# M_G_T.net
KiCad netlist of a schematic drawn in Altium Designer
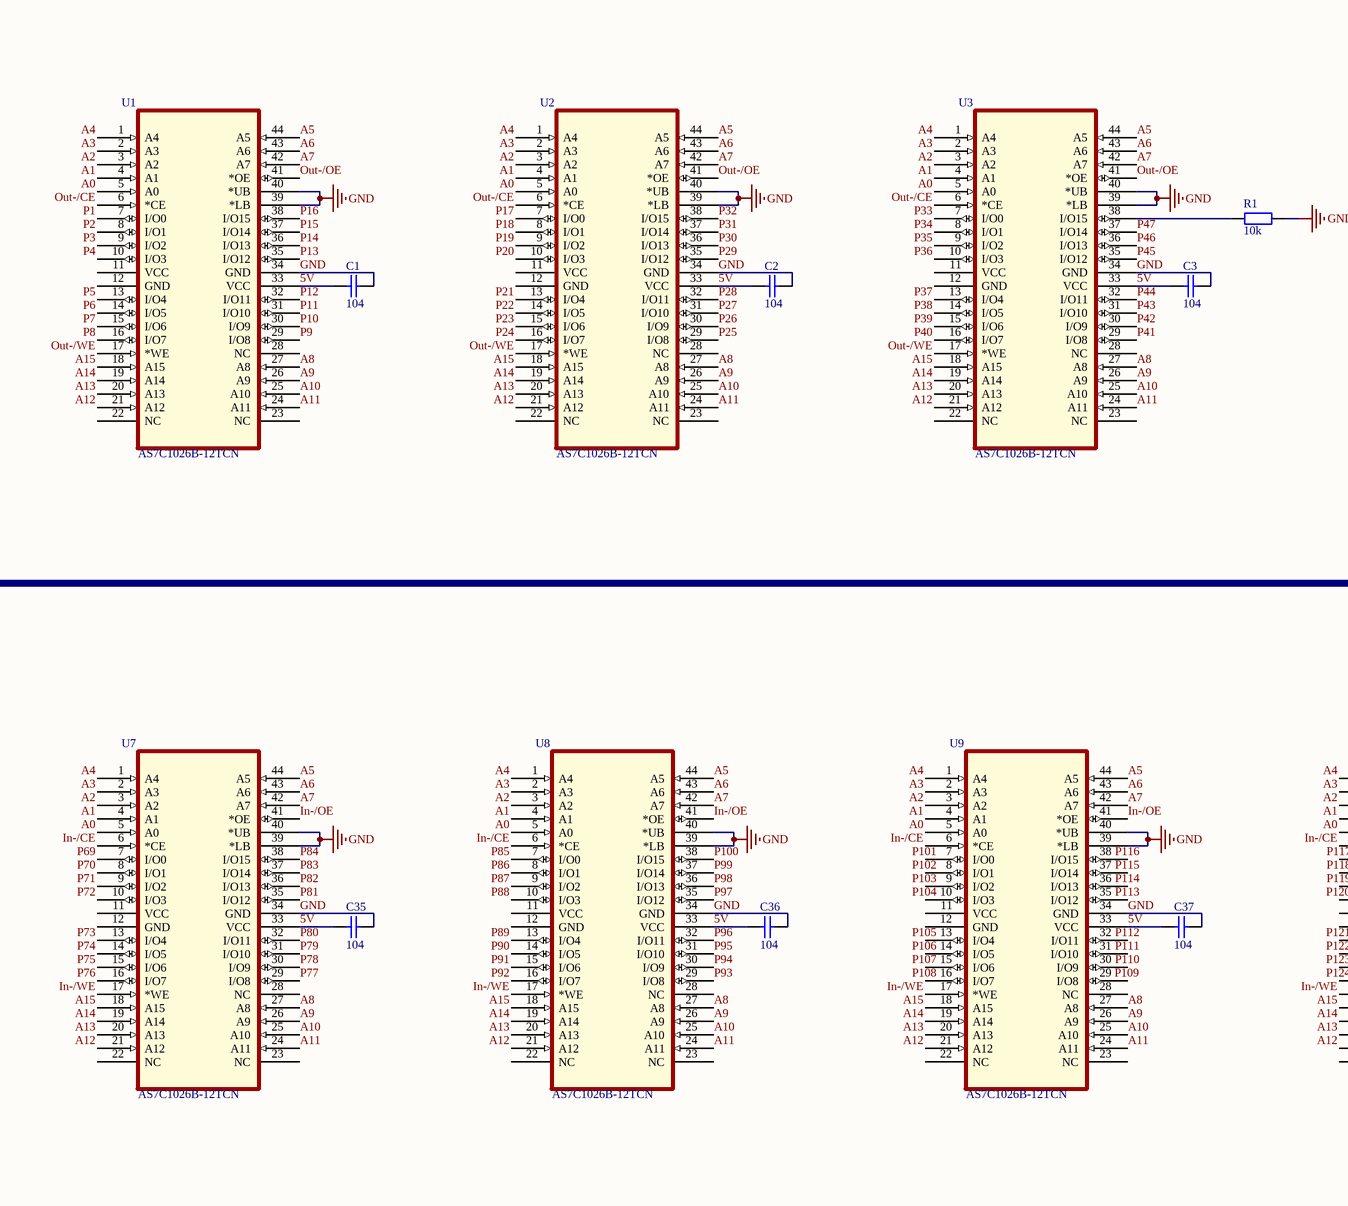
[diagram p0: M_G_T.SchDoc, top left]
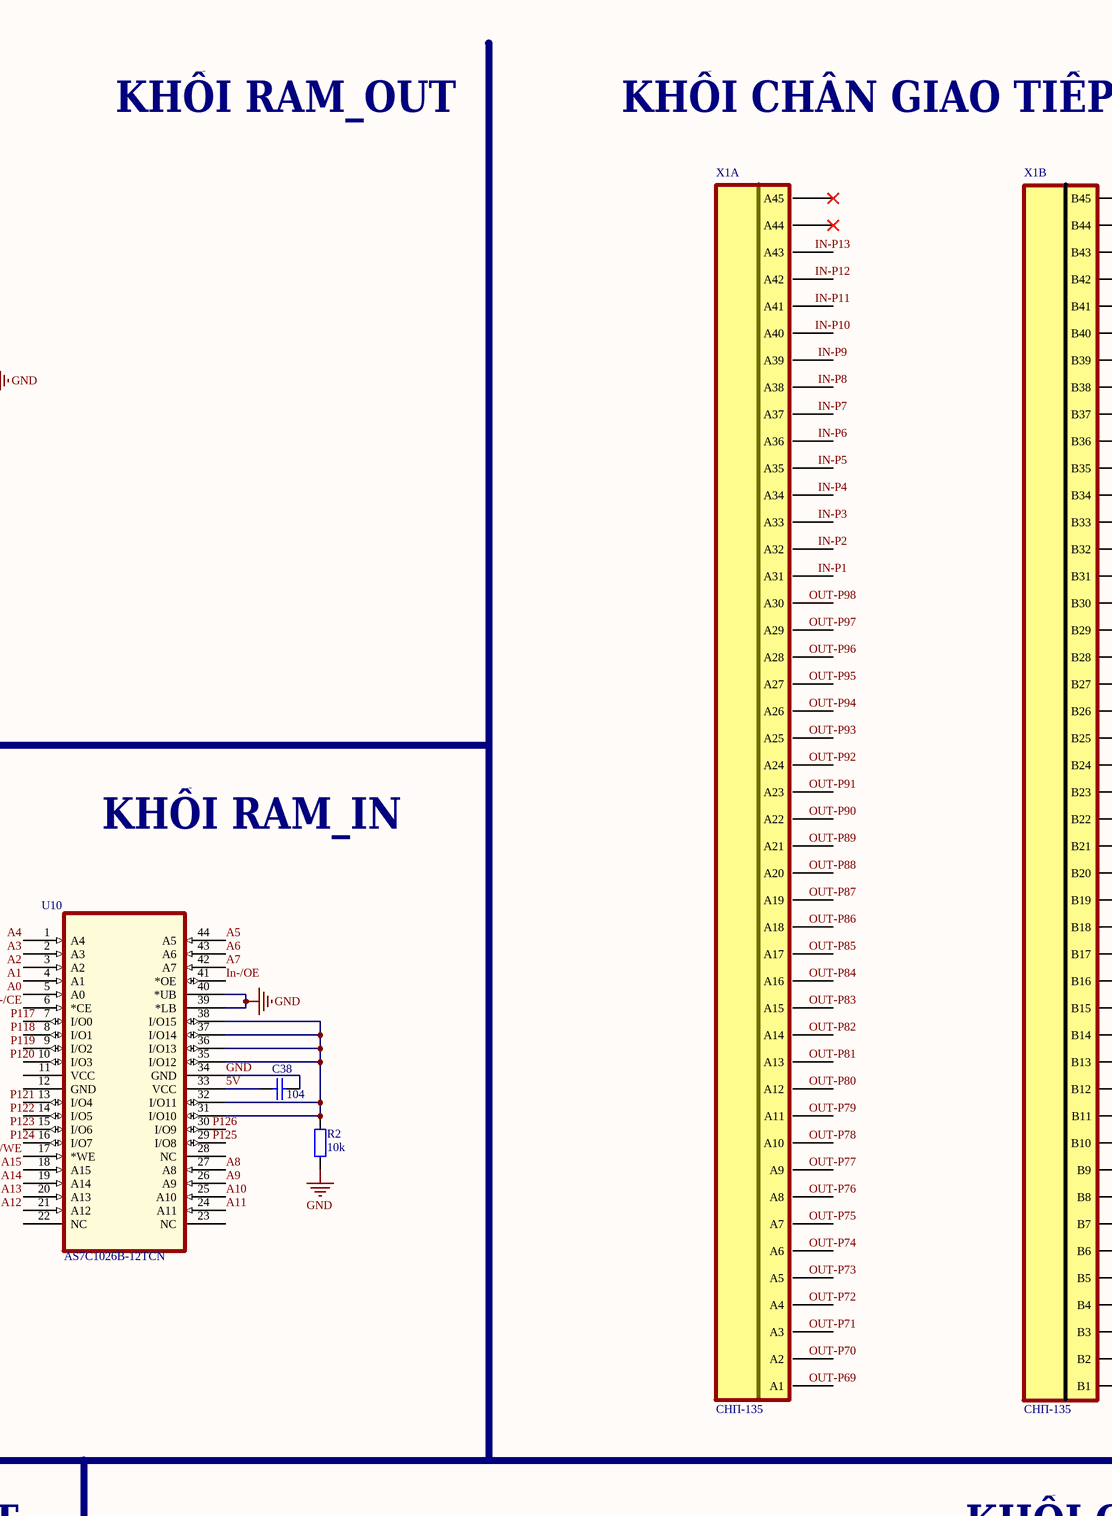
[diagram p1: M_G_T.SchDoc, top middle]
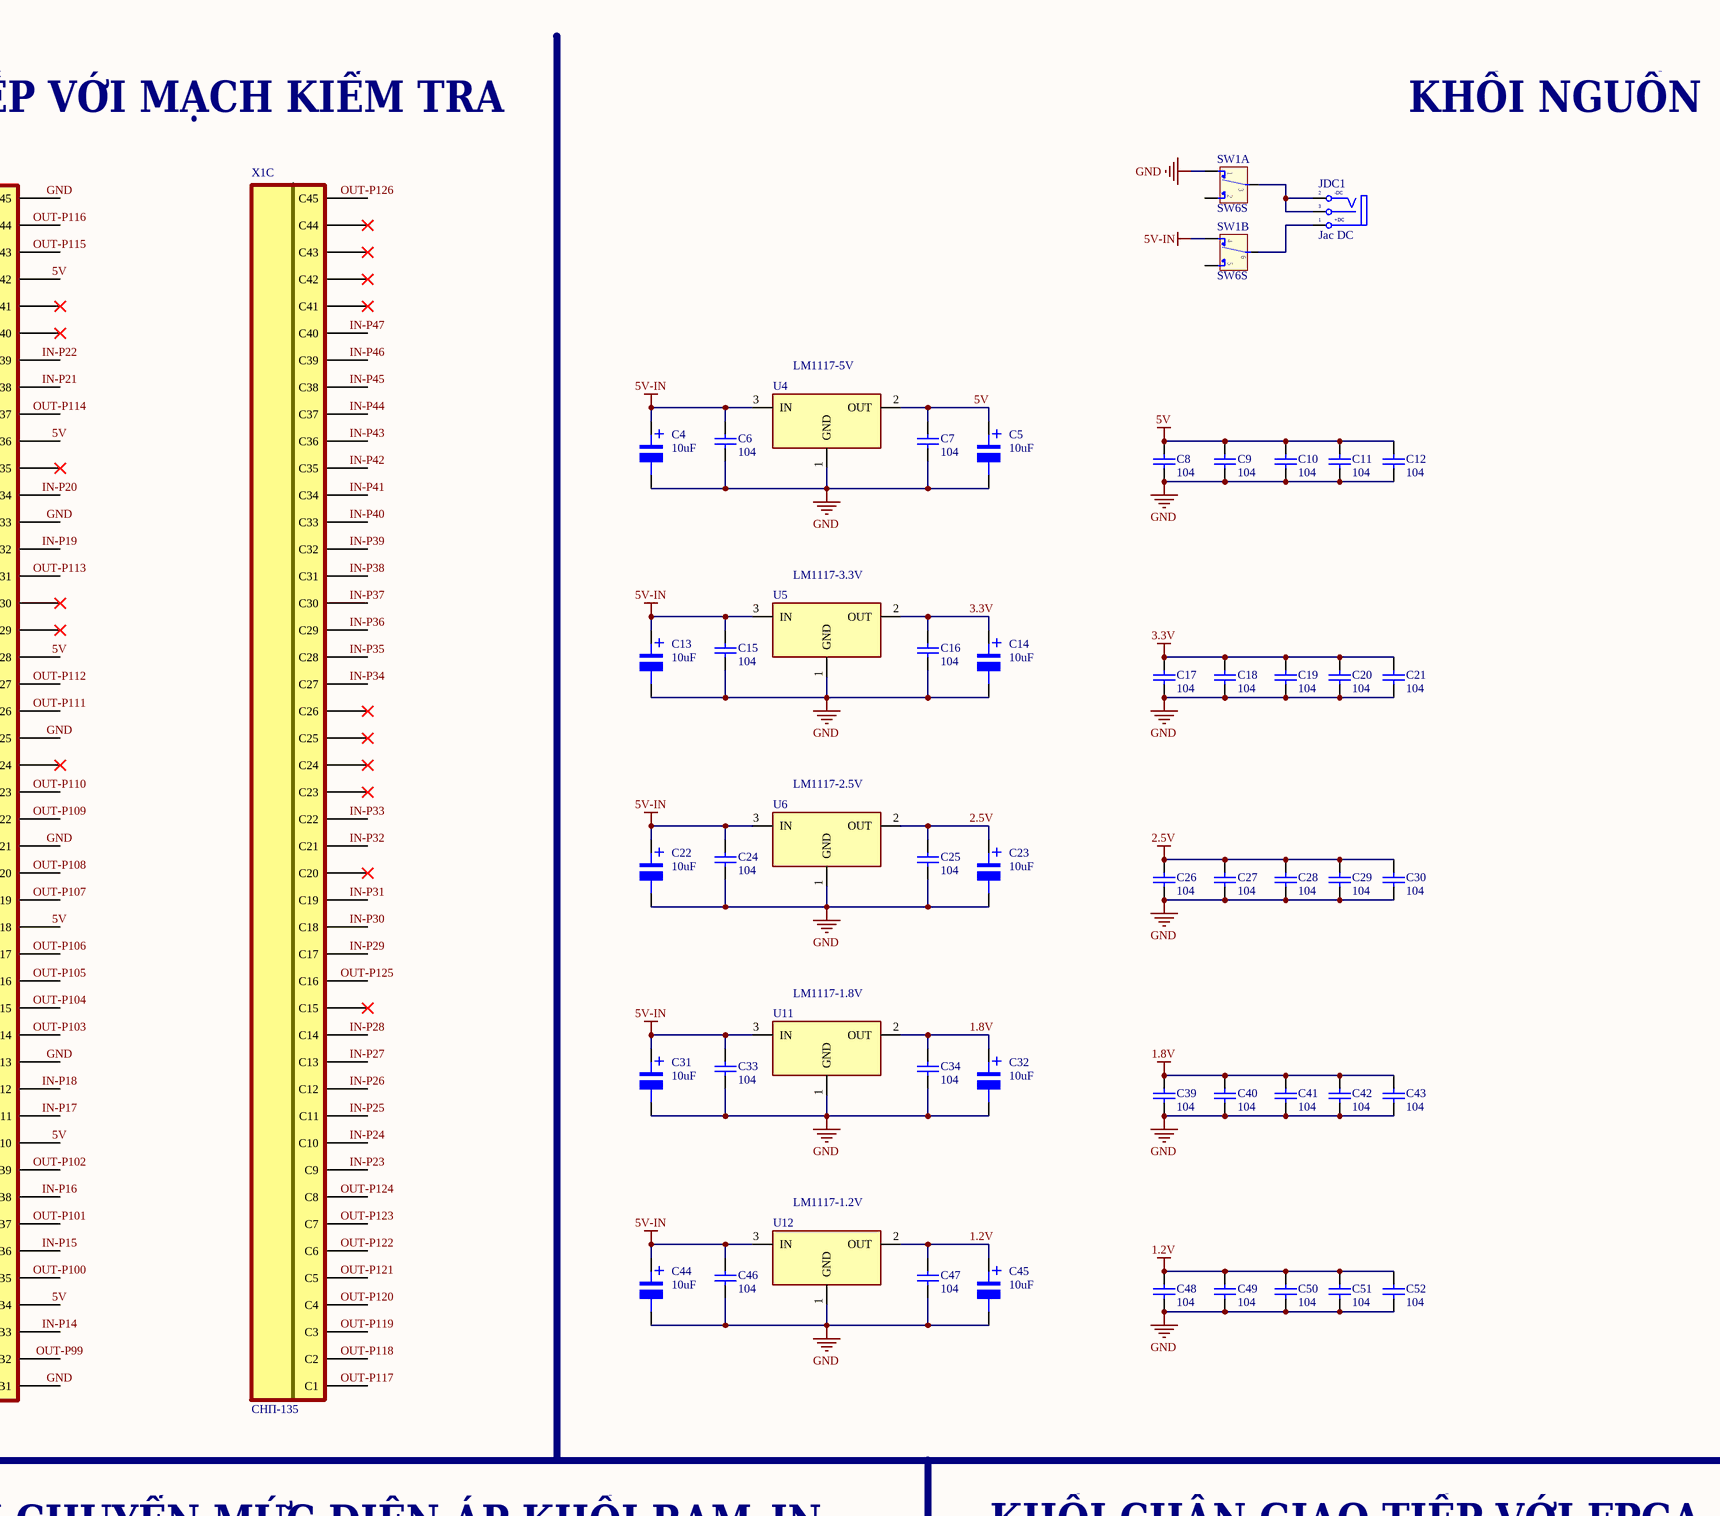
[diagram p2: M_G_T.SchDoc, top right]
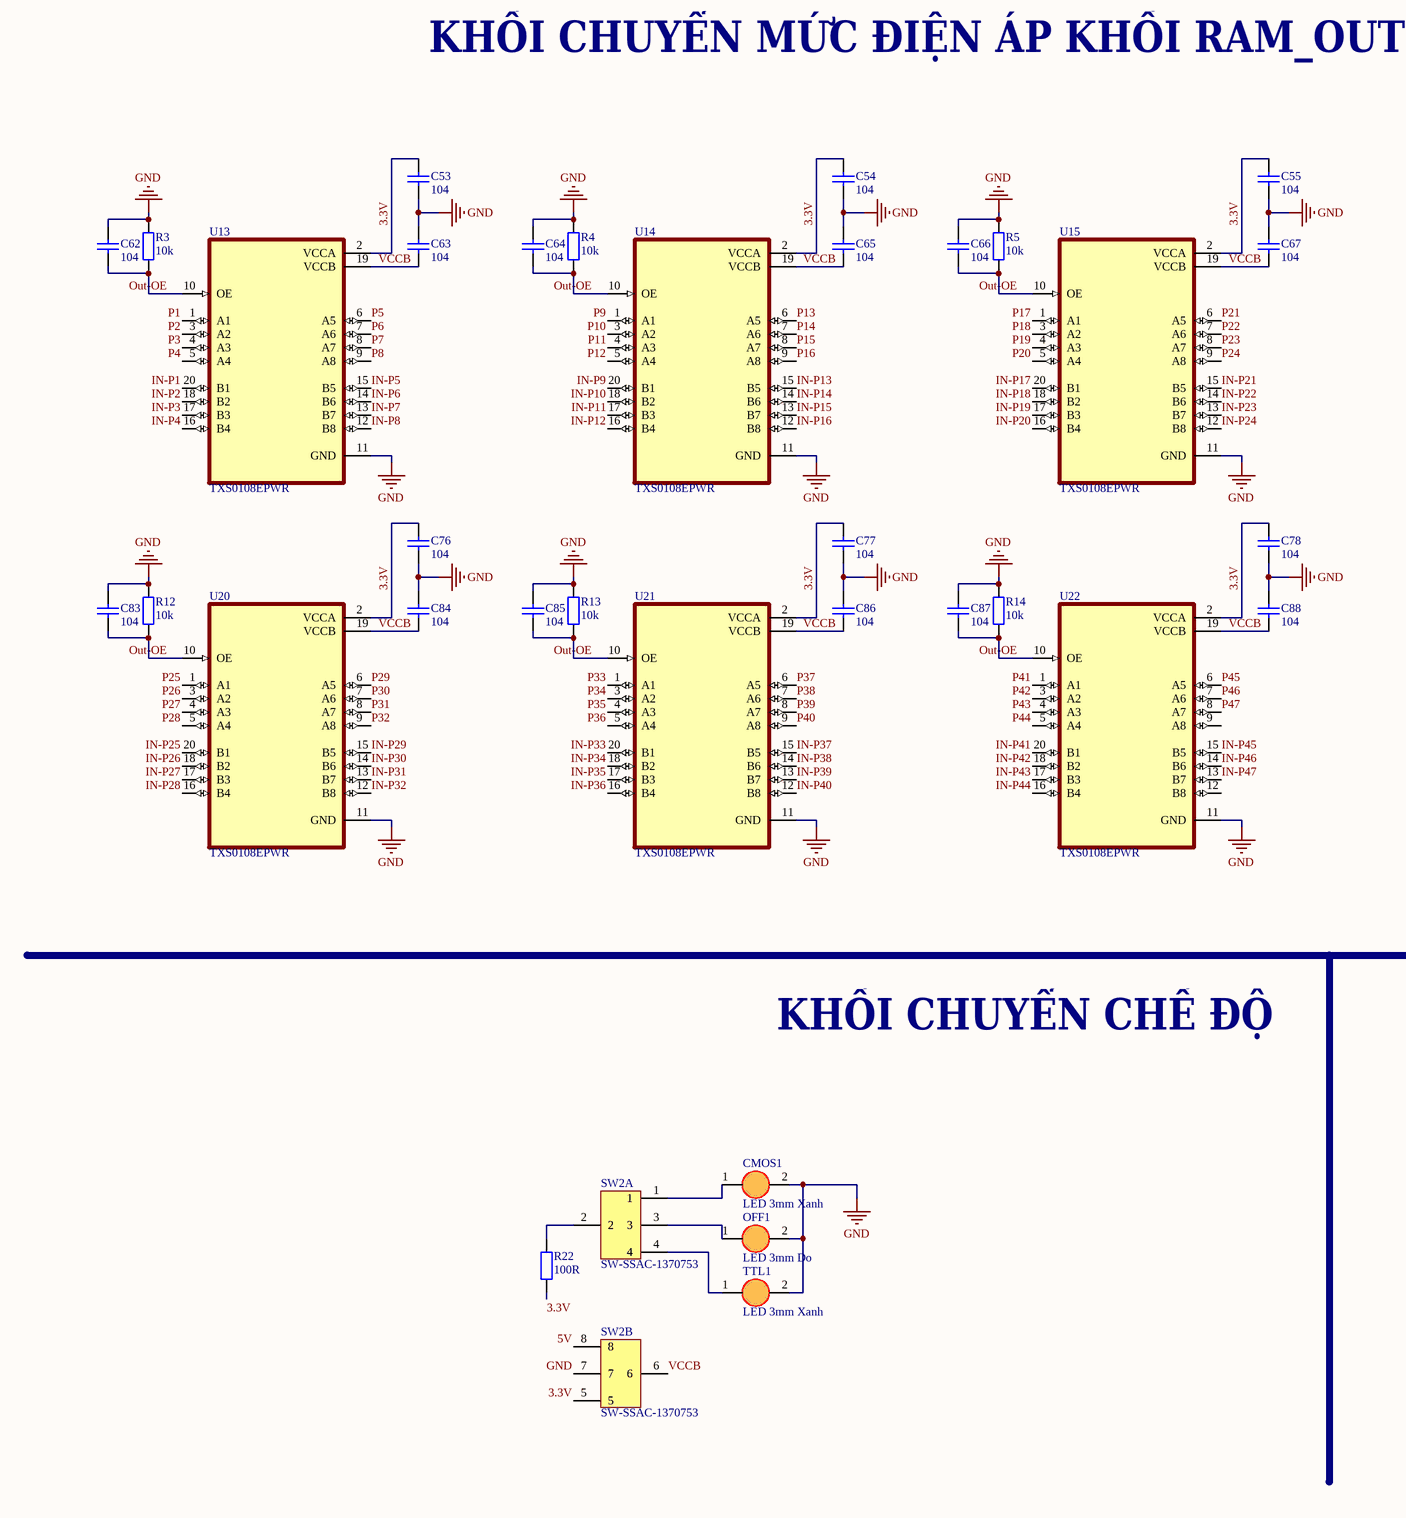
[diagram p3: M_G_T.SchDoc, bottom left]
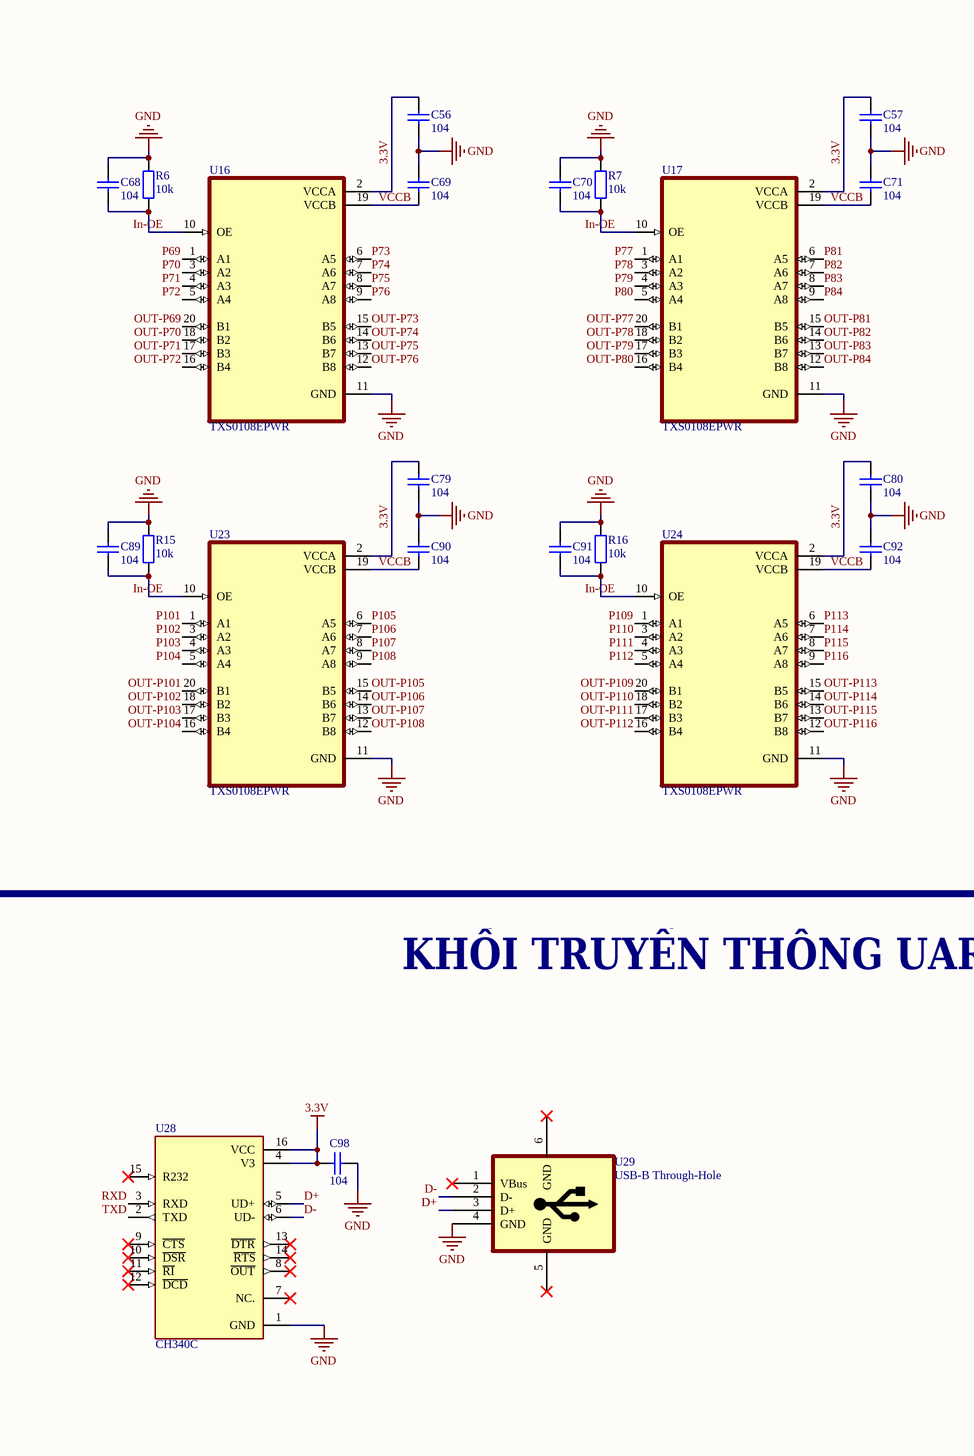
[diagram p4: M_G_T.SchDoc, bottom middle]
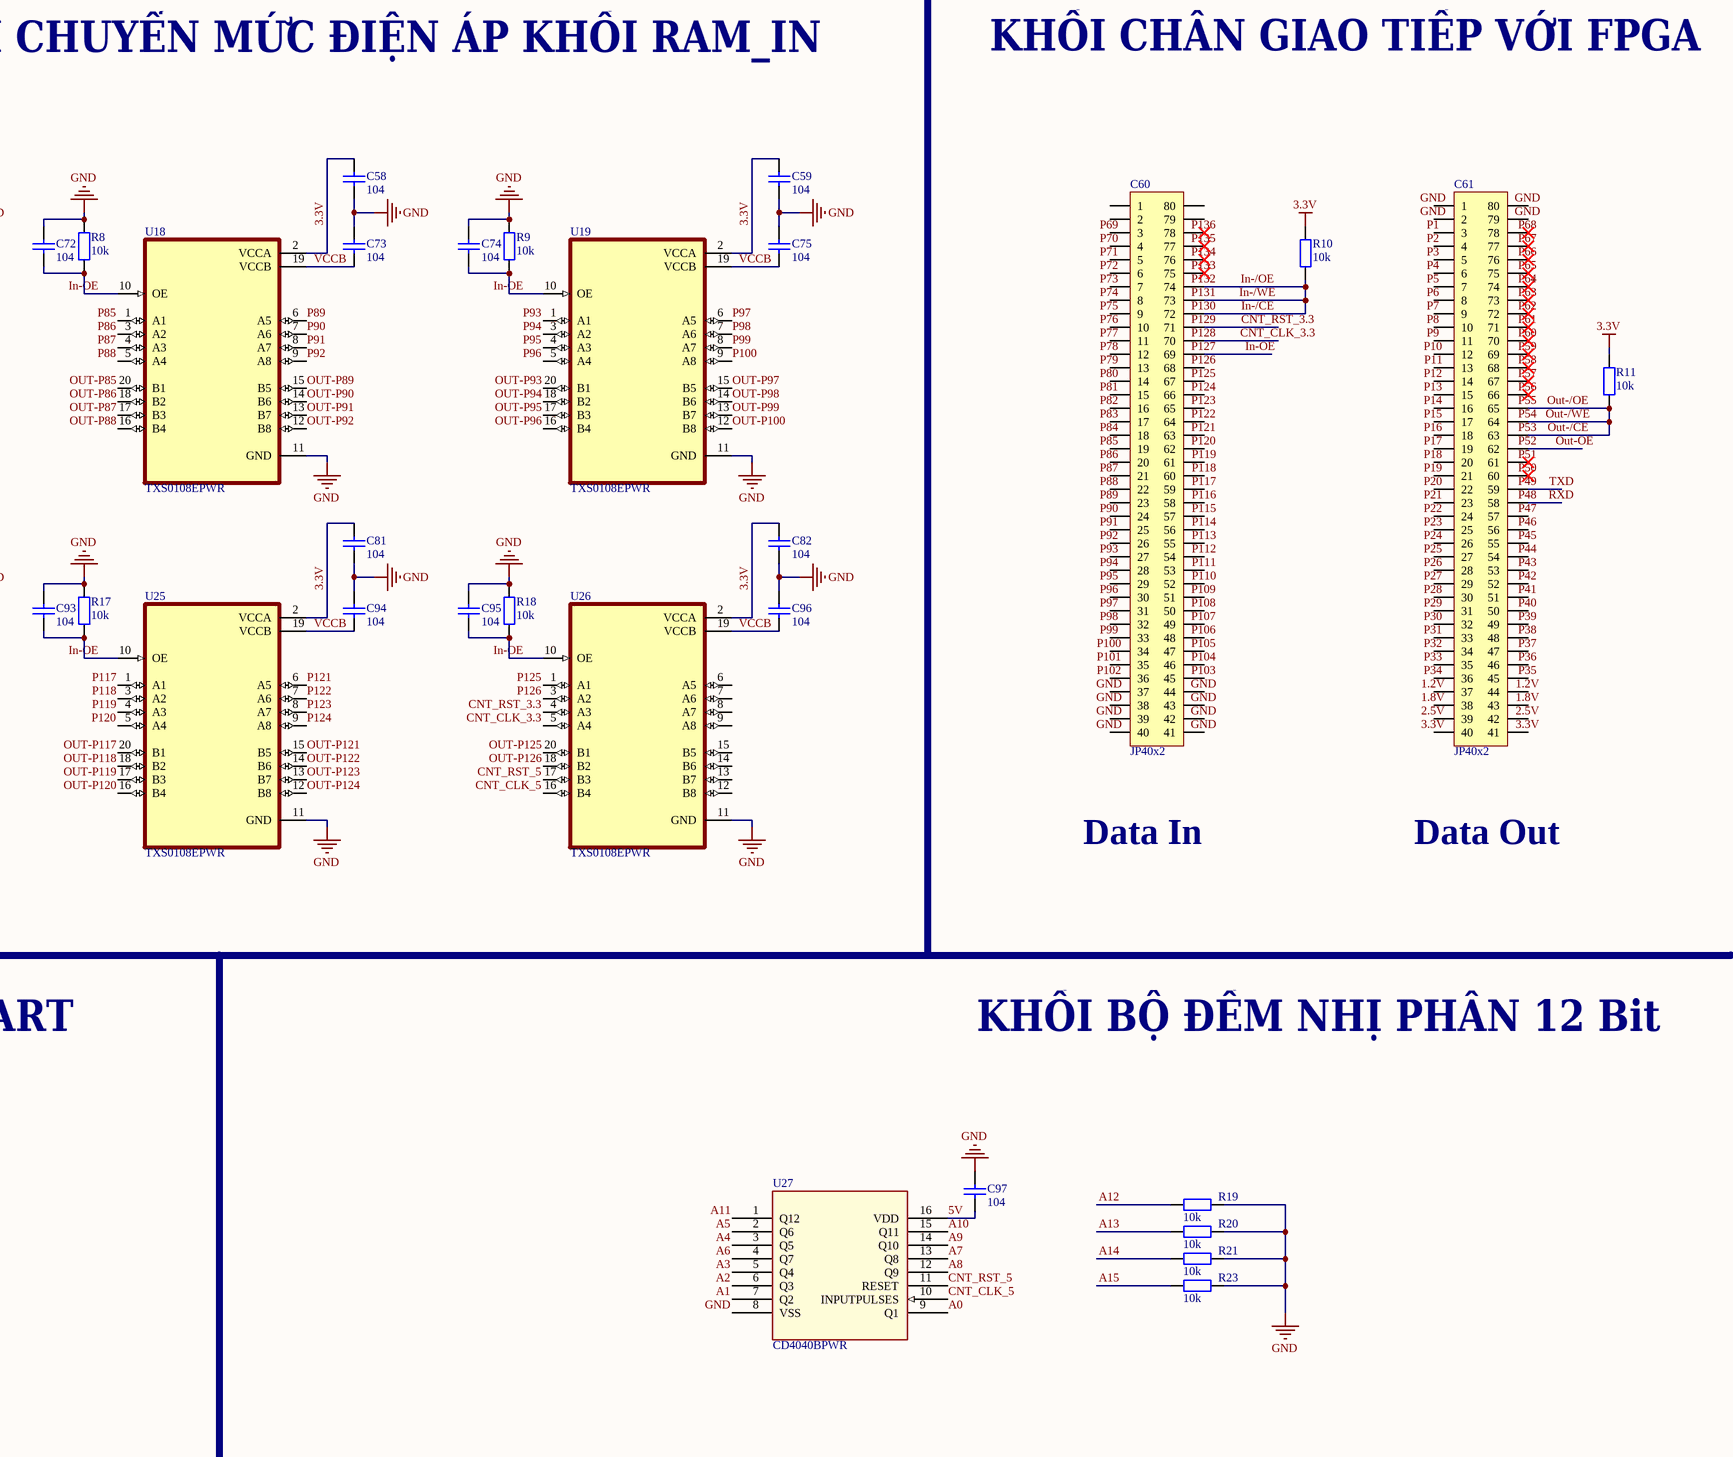
[diagram p5: M_G_T.SchDoc, bottom right]

(export (version "E")
  (design (tool "Eeschema 10.0.6"))
  (components
    (comp (ref "C1")
      (value "104")
      (footprint "Tu 0805")
      (description "Dán")
      (libsource (lib "THU VIEN SCH") (part "Tu 104"))
    )
    (comp (ref "C2")
      (value "104")
      (footprint "Tu 0805")
      (description "Dán")
      (libsource (lib "THU VIEN SCH") (part "Tu 104"))
    )
    (comp (ref "C3")
      (value "104")
      (footprint "Tu 0805")
      (description "Dán")
      (libsource (lib "THU VIEN SCH") (part "Tu 104"))
    )
    (comp (ref "C4")
      (value "10uF")
      (footprint "tu nhom 4 (b)")
      (description "Dán")
      (libsource (lib "THU VIEN SCH") (part "Tu Nhom 10uF 16V"))
    )
    (comp (ref "C5")
      (value "10uF")
      (footprint "tu nhom 4 (b)")
      (description "Dán")
      (libsource (lib "THU VIEN SCH") (part "Tu Nhom 10uF 16V"))
    )
    (comp (ref "C6")
      (value "104")
      (footprint "Tu 0805")
      (description "Dán")
      (libsource (lib "THU VIEN SCH") (part "Tu 104"))
    )
    (comp (ref "C7")
      (value "104")
      (footprint "Tu 0805")
      (description "Dán")
      (libsource (lib "THU VIEN SCH") (part "Tu 104"))
    )
    (comp (ref "C8")
      (value "104")
      (footprint "Tu 0805")
      (description "Dán")
      (libsource (lib "THU VIEN SCH") (part "Tu 104"))
    )
    (comp (ref "C9")
      (value "104")
      (footprint "Tu 0805")
      (description "Dán")
      (libsource (lib "THU VIEN SCH") (part "Tu 104"))
    )
    (comp (ref "C10")
      (value "104")
      (footprint "Tu 0805")
      (description "Dán")
      (libsource (lib "THU VIEN SCH") (part "Tu 104"))
    )
    (comp (ref "C11")
      (value "104")
      (footprint "Tu 0805")
      (description "Dán")
      (libsource (lib "THU VIEN SCH") (part "Tu 104"))
    )
    (comp (ref "C12")
      (value "104")
      (footprint "Tu 0805")
      (description "Dán")
      (libsource (lib "THU VIEN SCH") (part "Tu 104"))
    )
    (comp (ref "C13")
      (value "10uF")
      (footprint "tu nhom 4 (b)")
      (description "Dán")
      (libsource (lib "THU VIEN SCH") (part "Tu Nhom 10uF 16V"))
    )
    (comp (ref "C14")
      (value "10uF")
      (footprint "tu nhom 4 (b)")
      (description "Dán")
      (libsource (lib "THU VIEN SCH") (part "Tu Nhom 10uF 16V"))
    )
    (comp (ref "C15")
      (value "104")
      (footprint "Tu 0805")
      (description "Dán")
      (libsource (lib "THU VIEN SCH") (part "Tu 104"))
    )
    (comp (ref "C16")
      (value "104")
      (footprint "Tu 0805")
      (description "Dán")
      (libsource (lib "THU VIEN SCH") (part "Tu 104"))
    )
    (comp (ref "C17")
      (value "104")
      (footprint "Tu 0805")
      (description "Dán")
      (libsource (lib "THU VIEN SCH") (part "Tu 104"))
    )
    (comp (ref "C18")
      (value "104")
      (footprint "Tu 0805")
      (description "Dán")
      (libsource (lib "THU VIEN SCH") (part "Tu 104"))
    )
    (comp (ref "C19")
      (value "104")
      (footprint "Tu 0805")
      (description "Dán")
      (libsource (lib "THU VIEN SCH") (part "Tu 104"))
    )
    (comp (ref "C20")
      (value "104")
      (footprint "Tu 0805")
      (description "Dán")
      (libsource (lib "THU VIEN SCH") (part "Tu 104"))
    )
    (comp (ref "C21")
      (value "104")
      (footprint "Tu 0805")
      (description "Dán")
      (libsource (lib "THU VIEN SCH") (part "Tu 104"))
    )
    (comp (ref "C22")
      (value "10uF")
      (footprint "tu nhom 4 (b)")
      (description "Dán")
      (libsource (lib "THU VIEN SCH") (part "Tu Nhom 10uF 16V"))
    )
    (comp (ref "C23")
      (value "10uF")
      (footprint "tu nhom 4 (b)")
      (description "Dán")
      (libsource (lib "THU VIEN SCH") (part "Tu Nhom 10uF 16V"))
    )
    (comp (ref "C24")
      (value "104")
      (footprint "Tu 0805")
      (description "Dán")
      (libsource (lib "THU VIEN SCH") (part "Tu 104"))
    )
    (comp (ref "C25")
      (value "104")
      (footprint "Tu 0805")
      (description "Dán")
      (libsource (lib "THU VIEN SCH") (part "Tu 104"))
    )
    (comp (ref "C26")
      (value "104")
      (footprint "Tu 0805")
      (description "Dán")
      (libsource (lib "THU VIEN SCH") (part "Tu 104"))
    )
    (comp (ref "C27")
      (value "104")
      (footprint "Tu 0805")
      (description "Dán")
      (libsource (lib "THU VIEN SCH") (part "Tu 104"))
    )
    (comp (ref "C28")
      (value "104")
      (footprint "Tu 0805")
      (description "Dán")
      (libsource (lib "THU VIEN SCH") (part "Tu 104"))
    )
    (comp (ref "C29")
      (value "104")
      (footprint "Tu 0805")
      (description "Dán")
      (libsource (lib "THU VIEN SCH") (part "Tu 104"))
    )
    (comp (ref "C30")
      (value "104")
      (footprint "Tu 0805")
      (description "Dán")
      (libsource (lib "THU VIEN SCH") (part "Tu 104"))
    )
    (comp (ref "C31")
      (value "10uF")
      (footprint "tu nhom 4 (b)")
      (description "Dán")
      (libsource (lib "THU VIEN SCH") (part "Tu Nhom 10uF 16V"))
    )
    (comp (ref "C32")
      (value "10uF")
      (footprint "tu nhom 4 (b)")
      (description "Dán")
      (libsource (lib "THU VIEN SCH") (part "Tu Nhom 10uF 16V"))
    )
    (comp (ref "C33")
      (value "104")
      (footprint "Tu 0805")
      (description "Dán")
      (libsource (lib "THU VIEN SCH") (part "Tu 104"))
    )
    (comp (ref "C34")
      (value "104")
      (footprint "Tu 0805")
      (description "Dán")
      (libsource (lib "THU VIEN SCH") (part "Tu 104"))
    )
    (comp (ref "C35")
      (value "104")
      (footprint "Tu 0805")
      (description "Dán")
      (libsource (lib "THU VIEN SCH") (part "Tu 104"))
    )
    (comp (ref "C36")
      (value "104")
      (footprint "Tu 0805")
      (description "Dán")
      (libsource (lib "THU VIEN SCH") (part "Tu 104"))
    )
    (comp (ref "C37")
      (value "104")
      (footprint "Tu 0805")
      (description "Dán")
      (libsource (lib "THU VIEN SCH") (part "Tu 104"))
    )
    (comp (ref "C38")
      (value "104")
      (footprint "Tu 0805")
      (description "Dán")
      (libsource (lib "THU VIEN SCH") (part "Tu 104"))
    )
    (comp (ref "C39")
      (value "104")
      (footprint "Tu 0805")
      (description "Dán")
      (libsource (lib "THU VIEN SCH") (part "Tu 104"))
    )
    (comp (ref "C40")
      (value "104")
      (footprint "Tu 0805")
      (description "Dán")
      (libsource (lib "THU VIEN SCH") (part "Tu 104"))
    )
    (comp (ref "C41")
      (value "104")
      (footprint "Tu 0805")
      (description "Dán")
      (libsource (lib "THU VIEN SCH") (part "Tu 104"))
    )
    (comp (ref "C42")
      (value "104")
      (footprint "Tu 0805")
      (description "Dán")
      (libsource (lib "THU VIEN SCH") (part "Tu 104"))
    )
    (comp (ref "C43")
      (value "104")
      (footprint "Tu 0805")
      (description "Dán")
      (libsource (lib "THU VIEN SCH") (part "Tu 104"))
    )
    (comp (ref "C44")
      (value "10uF")
      (footprint "tu nhom 4 (b)")
      (description "Dán")
      (libsource (lib "THU VIEN SCH") (part "Tu Nhom 10uF 16V"))
    )
    (comp (ref "C45")
      (value "10uF")
      (footprint "tu nhom 4 (b)")
      (description "Dán")
      (libsource (lib "THU VIEN SCH") (part "Tu Nhom 10uF 16V"))
    )
    (comp (ref "C46")
      (value "104")
      (footprint "Tu 0805")
      (description "Dán")
      (libsource (lib "THU VIEN SCH") (part "Tu 104"))
    )
    (comp (ref "C47")
      (value "104")
      (footprint "Tu 0805")
      (description "Dán")
      (libsource (lib "THU VIEN SCH") (part "Tu 104"))
    )
    (comp (ref "C48")
      (value "104")
      (footprint "Tu 0805")
      (description "Dán")
      (libsource (lib "THU VIEN SCH") (part "Tu 104"))
    )
    (comp (ref "C49")
      (value "104")
      (footprint "Tu 0805")
      (description "Dán")
      (libsource (lib "THU VIEN SCH") (part "Tu 104"))
    )
    (comp (ref "C50")
      (value "104")
      (footprint "Tu 0805")
      (description "Dán")
      (libsource (lib "THU VIEN SCH") (part "Tu 104"))
    )
    (comp (ref "C51")
      (value "104")
      (footprint "Tu 0805")
      (description "Dán")
      (libsource (lib "THU VIEN SCH") (part "Tu 104"))
    )
    (comp (ref "C52")
      (value "104")
      (footprint "Tu 0805")
      (description "Dán")
      (libsource (lib "THU VIEN SCH") (part "Tu 104"))
    )
    (comp (ref "C53")
      (value "104")
      (footprint "Tu 0805")
      (description "Dán")
      (libsource (lib "THU VIEN SCH") (part "Tu 104"))
    )
    (comp (ref "C54")
      (value "104")
      (footprint "Tu 0805")
      (description "Dán")
      (libsource (lib "THU VIEN SCH") (part "Tu 104"))
    )
    (comp (ref "C55")
      (value "104")
      (footprint "Tu 0805")
      (description "Dán")
      (libsource (lib "THU VIEN SCH") (part "Tu 104"))
    )
    (comp (ref "C56")
      (value "104")
      (footprint "Tu 0805")
      (description "Dán")
      (libsource (lib "THU VIEN SCH") (part "Tu 104"))
    )
    (comp (ref "C57")
      (value "104")
      (footprint "Tu 0805")
      (description "Dán")
      (libsource (lib "THU VIEN SCH") (part "Tu 104"))
    )
    (comp (ref "C58")
      (value "104")
      (footprint "Tu 0805")
      (description "Dán")
      (libsource (lib "THU VIEN SCH") (part "Tu 104"))
    )
    (comp (ref "C59")
      (value "104")
      (footprint "Tu 0805")
      (description "Dán")
      (libsource (lib "THU VIEN SCH") (part "Tu 104"))
    )
    (comp (ref "C60")
      (value "JP40x2")
      (footprint "JP40-D2T")
      (description "WR-PHD 2.54 mm Dual Socket Header")
      (fields
        (field (name "MANUFACTURER") "Würth Elektronik eiSos GmbH")
        (field (name "PARTNO") "61307221821")
        (field (name "CREATED BY") "Karrer Zheng")
      )
      (libsource (lib "LIBRARY") (part "JP40x2"))
    )
    (comp (ref "C61")
      (value "JP40x2")
      (footprint "JP40-D2T")
      (description "WR-PHD 2.54 mm Dual Socket Header")
      (fields
        (field (name "MANUFACTURER") "Würth Elektronik eiSos GmbH")
        (field (name "PARTNO") "61307221821")
        (field (name "CREATED BY") "Karrer Zheng")
      )
      (libsource (lib "LIBRARY") (part "JP40x2"))
    )
    (comp (ref "C62")
      (value "104")
      (footprint "Tu 0805")
      (description "Dán")
      (libsource (lib "THU VIEN SCH") (part "Tu 104"))
    )
    (comp (ref "C63")
      (value "104")
      (footprint "Tu 0805")
      (description "Dán")
      (libsource (lib "THU VIEN SCH") (part "Tu 104"))
    )
    (comp (ref "C64")
      (value "104")
      (footprint "Tu 0805")
      (description "Dán")
      (libsource (lib "THU VIEN SCH") (part "Tu 104"))
    )
    (comp (ref "C65")
      (value "104")
      (footprint "Tu 0805")
      (description "Dán")
      (libsource (lib "THU VIEN SCH") (part "Tu 104"))
    )
    (comp (ref "C66")
      (value "104")
      (footprint "Tu 0805")
      (description "Dán")
      (libsource (lib "THU VIEN SCH") (part "Tu 104"))
    )
    (comp (ref "C67")
      (value "104")
      (footprint "Tu 0805")
      (description "Dán")
      (libsource (lib "THU VIEN SCH") (part "Tu 104"))
    )
    (comp (ref "C68")
      (value "104")
      (footprint "Tu 0805")
      (description "Dán")
      (libsource (lib "THU VIEN SCH") (part "Tu 104"))
    )
    (comp (ref "C69")
      (value "104")
      (footprint "Tu 0805")
      (description "Dán")
      (libsource (lib "THU VIEN SCH") (part "Tu 104"))
    )
    (comp (ref "C70")
      (value "104")
      (footprint "Tu 0805")
      (description "Dán")
      (libsource (lib "THU VIEN SCH") (part "Tu 104"))
    )
    (comp (ref "C71")
      (value "104")
      (footprint "Tu 0805")
      (description "Dán")
      (libsource (lib "THU VIEN SCH") (part "Tu 104"))
    )
    (comp (ref "C72")
      (value "104")
      (footprint "Tu 0805")
      (description "Dán")
      (libsource (lib "THU VIEN SCH") (part "Tu 104"))
    )
    (comp (ref "C73")
      (value "104")
      (footprint "Tu 0805")
      (description "Dán")
      (libsource (lib "THU VIEN SCH") (part "Tu 104"))
    )
    (comp (ref "C74")
      (value "104")
      (footprint "Tu 0805")
      (description "Dán")
      (libsource (lib "THU VIEN SCH") (part "Tu 104"))
    )
    (comp (ref "C75")
      (value "104")
      (footprint "Tu 0805")
      (description "Dán")
      (libsource (lib "THU VIEN SCH") (part "Tu 104"))
    )
    (comp (ref "C76")
      (value "104")
      (footprint "Tu 0805")
      (description "Dán")
      (libsource (lib "THU VIEN SCH") (part "Tu 104"))
    )
    (comp (ref "C77")
      (value "104")
      (footprint "Tu 0805")
      (description "Dán")
      (libsource (lib "THU VIEN SCH") (part "Tu 104"))
    )
    (comp (ref "C78")
      (value "104")
      (footprint "Tu 0805")
      (description "Dán")
      (libsource (lib "THU VIEN SCH") (part "Tu 104"))
    )
    (comp (ref "C79")
      (value "104")
      (footprint "Tu 0805")
      (description "Dán")
      (libsource (lib "THU VIEN SCH") (part "Tu 104"))
    )
    (comp (ref "C80")
      (value "104")
      (footprint "Tu 0805")
      (description "Dán")
      (libsource (lib "THU VIEN SCH") (part "Tu 104"))
    )
    (comp (ref "C81")
      (value "104")
      (footprint "Tu 0805")
      (description "Dán")
      (libsource (lib "THU VIEN SCH") (part "Tu 104"))
    )
    (comp (ref "C82")
      (value "104")
      (footprint "Tu 0805")
      (description "Dán")
      (libsource (lib "THU VIEN SCH") (part "Tu 104"))
    )
    (comp (ref "C83")
      (value "104")
      (footprint "Tu 0805")
      (description "Dán")
      (libsource (lib "THU VIEN SCH") (part "Tu 104"))
    )
    (comp (ref "C84")
      (value "104")
      (footprint "Tu 0805")
      (description "Dán")
      (libsource (lib "THU VIEN SCH") (part "Tu 104"))
    )
    (comp (ref "C85")
      (value "104")
      (footprint "Tu 0805")
      (description "Dán")
      (libsource (lib "THU VIEN SCH") (part "Tu 104"))
    )
    (comp (ref "C86")
      (value "104")
      (footprint "Tu 0805")
      (description "Dán")
      (libsource (lib "THU VIEN SCH") (part "Tu 104"))
    )
    (comp (ref "C87")
      (value "104")
      (footprint "Tu 0805")
      (description "Dán")
      (libsource (lib "THU VIEN SCH") (part "Tu 104"))
    )
    (comp (ref "C88")
      (value "104")
      (footprint "Tu 0805")
      (description "Dán")
      (libsource (lib "THU VIEN SCH") (part "Tu 104"))
    )
    (comp (ref "C89")
      (value "104")
      (footprint "Tu 0805")
      (description "Dán")
      (libsource (lib "THU VIEN SCH") (part "Tu 104"))
    )
    (comp (ref "C90")
      (value "104")
      (footprint "Tu 0805")
      (description "Dán")
      (libsource (lib "THU VIEN SCH") (part "Tu 104"))
    )
    (comp (ref "C91")
      (value "104")
      (footprint "Tu 0805")
      (description "Dán")
      (libsource (lib "THU VIEN SCH") (part "Tu 104"))
    )
    (comp (ref "C92")
      (value "104")
      (footprint "Tu 0805")
      (description "Dán")
      (libsource (lib "THU VIEN SCH") (part "Tu 104"))
    )
    (comp (ref "C93")
      (value "104")
      (footprint "Tu 0805")
      (description "Dán")
      (libsource (lib "THU VIEN SCH") (part "Tu 104"))
    )
    (comp (ref "C94")
      (value "104")
      (footprint "Tu 0805")
      (description "Dán")
      (libsource (lib "THU VIEN SCH") (part "Tu 104"))
    )
    (comp (ref "C95")
      (value "104")
      (footprint "Tu 0805")
      (description "Dán")
      (libsource (lib "THU VIEN SCH") (part "Tu 104"))
    )
    (comp (ref "C96")
      (value "104")
      (footprint "Tu 0805")
      (description "Dán")
      (libsource (lib "THU VIEN SCH") (part "Tu 104"))
    )
    (comp (ref "C97")
      (value "104")
      (footprint "Tu 0805")
      (description "Dán")
      (libsource (lib "THU VIEN SCH") (part "Tu 104"))
    )
    (comp (ref "C98")
      (value "104")
      (footprint "Tu 0805")
      (description "Dán")
      (libsource (lib "THU VIEN SCH") (part "Tu 104"))
    )
    (comp (ref "CMOS1")
      (value "LED 3mm Xanh")
      (footprint "LED 3MM XANH")
      (description "Cắm")
      (libsource (lib "THU VIEN SCH") (part "LED 3mm Xanh"))
    )
    (comp (ref "JDC1")
      (value "Jac DC")
      (footprint "DC-IN")
      (description "Jac DC input")
      (libsource (lib "ThuVien") (part "DCIN"))
    )
    (comp (ref "OFF1")
      (value "LED 3mm Do")
      (footprint "LED 3mm Do")
      (description "Cắm")
      (libsource (lib "THU VIEN SCH") (part "LED 3mm Do"))
    )
    (comp (ref "R1")
      (value "10k")
      (footprint "tro smd 0805")
      (description "Dán")
      (libsource (lib "THU VIEN SCH") (part "Tro 0805 5% 10k"))
    )
    (comp (ref "R2")
      (value "10k")
      (footprint "tro smd 0805")
      (description "Dán")
      (libsource (lib "THU VIEN SCH") (part "Tro 0805 5% 10k"))
    )
    (comp (ref "R3")
      (value "10k")
      (footprint "tro smd 0805")
      (description "Dán")
      (libsource (lib "THU VIEN SCH") (part "Tro 0805 5% 10k"))
    )
    (comp (ref "R4")
      (value "10k")
      (footprint "tro smd 0805")
      (description "Dán")
      (libsource (lib "THU VIEN SCH") (part "Tro 0805 5% 10k"))
    )
    (comp (ref "R5")
      (value "10k")
      (footprint "tro smd 0805")
      (description "Dán")
      (libsource (lib "THU VIEN SCH") (part "Tro 0805 5% 10k"))
    )
    (comp (ref "R6")
      (value "10k")
      (footprint "tro smd 0805")
      (description "Dán")
      (libsource (lib "THU VIEN SCH") (part "Tro 0805 5% 10k"))
    )
    (comp (ref "R7")
      (value "10k")
      (footprint "tro smd 0805")
      (description "Dán")
      (libsource (lib "THU VIEN SCH") (part "Tro 0805 5% 10k"))
    )
    (comp (ref "R8")
      (value "10k")
      (footprint "tro smd 0805")
      (description "Dán")
      (libsource (lib "THU VIEN SCH") (part "Tro 0805 5% 10k"))
    )
    (comp (ref "R9")
      (value "10k")
      (footprint "tro smd 0805")
      (description "Dán")
      (libsource (lib "THU VIEN SCH") (part "Tro 0805 5% 10k"))
    )
    (comp (ref "R10")
      (value "10k")
      (footprint "tro smd 0805")
      (description "Dán")
      (libsource (lib "THU VIEN SCH") (part "Tro 0805 5% 10k"))
    )
    (comp (ref "R11")
      (value "10k")
      (footprint "tro smd 0805")
      (description "Dán")
      (libsource (lib "THU VIEN SCH") (part "Tro 0805 5% 10k"))
    )
    (comp (ref "R12")
      (value "10k")
      (footprint "tro smd 0805")
      (description "Dán")
      (libsource (lib "THU VIEN SCH") (part "Tro 0805 5% 10k"))
    )
    (comp (ref "R13")
      (value "10k")
      (footprint "tro smd 0805")
      (description "Dán")
      (libsource (lib "THU VIEN SCH") (part "Tro 0805 5% 10k"))
    )
    (comp (ref "R14")
      (value "10k")
      (footprint "tro smd 0805")
      (description "Dán")
      (libsource (lib "THU VIEN SCH") (part "Tro 0805 5% 10k"))
    )
    (comp (ref "R15")
      (value "10k")
      (footprint "tro smd 0805")
      (description "Dán")
      (libsource (lib "THU VIEN SCH") (part "Tro 0805 5% 10k"))
    )
    (comp (ref "R16")
      (value "10k")
      (footprint "tro smd 0805")
      (description "Dán")
      (libsource (lib "THU VIEN SCH") (part "Tro 0805 5% 10k"))
    )
    (comp (ref "R17")
      (value "10k")
      (footprint "tro smd 0805")
      (description "Dán")
      (libsource (lib "THU VIEN SCH") (part "Tro 0805 5% 10k"))
    )
    (comp (ref "R18")
      (value "10k")
      (footprint "tro smd 0805")
      (description "Dán")
      (libsource (lib "THU VIEN SCH") (part "Tro 0805 5% 10k"))
    )
    (comp (ref "R19")
      (value "10k")
      (footprint "tro smd 0805")
      (description "Dán")
      (libsource (lib "THU VIEN SCH") (part "Tro 0805 5% 10k"))
    )
    (comp (ref "R20")
      (value "10k")
      (footprint "tro smd 0805")
      (description "Dán")
      (libsource (lib "THU VIEN SCH") (part "Tro 0805 5% 10k"))
    )
    (comp (ref "R21")
      (value "10k")
      (footprint "tro smd 0805")
      (description "Dán")
      (libsource (lib "THU VIEN SCH") (part "Tro 0805 5% 10k"))
    )
    (comp (ref "R22")
      (value "100R")
      (footprint "tro smd 0805")
      (description "Dán")
      (libsource (lib "THU VIEN SCH") (part "Tro 0805 5% 100R"))
    )
    (comp (ref "R23")
      (value "10k")
      (footprint "tro smd 0805")
      (description "Dán")
      (libsource (lib "THU VIEN SCH") (part "Tro 0805 5% 10k"))
    )
    (comp (ref "SW1")
      (value "SW6S")
      (footprint "SW6")
      (description "SW-DTDP - 6 Pin")
      (libsource (lib "syhaunguyen") (part "SW6S"))
    )
    (comp (ref "SW2")
      (value "SW-SSAC-1370753")
      (footprint "SW-SSAC-1370753")
      (libsource (lib "ThuVien") (part "SW-SSAC-1370753"))
    )
    (comp (ref "TTL1")
      (value "LED 3mm Xanh")
      (footprint "LED 3MM XANH")
      (description "Cắm")
      (libsource (lib "THU VIEN SCH") (part "LED 3mm Xanh"))
    )
    (comp (ref "U1")
      (value "AS7C1026B-12TCN")
      (footprint "TSOP-44_MIL400_ALL-M")
      (description "RAM 16data, 16address")
      (fields (field (name "COPYRIGHT") "Copyright (C) 2023 Ultra Librarian. All rights reserved."))
      (libsource (lib "ThuVien") (part "AS7C1026B-12TCN"))
    )
    (comp (ref "U2")
      (value "AS7C1026B-12TCN")
      (footprint "TSOP-44_MIL400_ALL-M")
      (description "RAM 16data, 16address")
      (fields (field (name "COPYRIGHT") "Copyright (C) 2023 Ultra Librarian. All rights reserved."))
      (libsource (lib "ThuVien") (part "AS7C1026B-12TCN"))
    )
    (comp (ref "U3")
      (value "AS7C1026B-12TCN")
      (footprint "TSOP-44_MIL400_ALL-M")
      (description "RAM 16data, 16address")
      (fields (field (name "COPYRIGHT") "Copyright (C) 2023 Ultra Librarian. All rights reserved."))
      (libsource (lib "ThuVien") (part "AS7C1026B-12TCN"))
    )
    (comp (ref "U4")
      (value "LM1117-5V")
      (footprint "LM1117-SOP")
      (description "800mA Low-Dropout Linear Regulator")
      (fields (field (name "CREATOR") "Nguyen Ba Bien"))
      (libsource (lib "ThuVien") (part "LM1117"))
    )
    (comp (ref "U5")
      (value "LM1117-3.3V")
      (footprint "LM1117-SOP")
      (description "800mA Low-Dropout Linear Regulator")
      (fields (field (name "CREATOR") "Nguyen Ba Bien"))
      (libsource (lib "ThuVien") (part "LM1117"))
    )
    (comp (ref "U6")
      (value "LM1117-2.5V")
      (footprint "LM1117-SOP")
      (description "800mA Low-Dropout Linear Regulator")
      (fields (field (name "CREATOR") "Nguyen Ba Bien"))
      (libsource (lib "ThuVien") (part "LM1117"))
    )
    (comp (ref "U7")
      (value "AS7C1026B-12TCN")
      (footprint "TSOP-44_MIL400_ALL-M")
      (description "RAM 16data, 16address")
      (fields (field (name "COPYRIGHT") "Copyright (C) 2023 Ultra Librarian. All rights reserved."))
      (libsource (lib "ThuVien") (part "AS7C1026B-12TCN"))
    )
    (comp (ref "U8")
      (value "AS7C1026B-12TCN")
      (footprint "TSOP-44_MIL400_ALL-M")
      (description "RAM 16data, 16address")
      (fields (field (name "COPYRIGHT") "Copyright (C) 2023 Ultra Librarian. All rights reserved."))
      (libsource (lib "ThuVien") (part "AS7C1026B-12TCN"))
    )
    (comp (ref "U9")
      (value "AS7C1026B-12TCN")
      (footprint "TSOP-44_MIL400_ALL-M")
      (description "RAM 16data, 16address")
      (fields (field (name "COPYRIGHT") "Copyright (C) 2023 Ultra Librarian. All rights reserved."))
      (libsource (lib "ThuVien") (part "AS7C1026B-12TCN"))
    )
    (comp (ref "U10")
      (value "AS7C1026B-12TCN")
      (footprint "TSOP-44_MIL400_ALL-M")
      (description "RAM 16data, 16address")
      (fields (field (name "COPYRIGHT") "Copyright (C) 2023 Ultra Librarian. All rights reserved."))
      (libsource (lib "ThuVien") (part "AS7C1026B-12TCN"))
    )
    (comp (ref "U11")
      (value "LM1117-1.8V")
      (footprint "LM1117-SOP")
      (description "800mA Low-Dropout Linear Regulator")
      (fields (field (name "CREATOR") "Nguyen Ba Bien"))
      (libsource (lib "ThuVien") (part "LM1117"))
    )
    (comp (ref "U12")
      (value "LM1117-1.2V")
      (footprint "LM1117-SOP")
      (description "800mA Low-Dropout Linear Regulator")
      (fields (field (name "CREATOR") "Nguyen Ba Bien"))
      (libsource (lib "ThuVien") (part "LM1117"))
    )
    (comp (ref "U13")
      (value "TXS0108EPWR")
      (footprint "SOP65P640X120-20N")
      (description "Chuyển đổi điệp áp 3.3V-5V")
      (libsource (lib "ThuVien") (part "TXS0108EPWR"))
    )
    (comp (ref "U14")
      (value "TXS0108EPWR")
      (footprint "SOP65P640X120-20N")
      (description "Chuyển đổi điệp áp 3.3V-5V")
      (libsource (lib "ThuVien") (part "TXS0108EPWR"))
    )
    (comp (ref "U15")
      (value "TXS0108EPWR")
      (footprint "SOP65P640X120-20N")
      (description "Chuyển đổi điệp áp 3.3V-5V")
      (libsource (lib "ThuVien") (part "TXS0108EPWR"))
    )
    (comp (ref "U16")
      (value "TXS0108EPWR")
      (footprint "SOP65P640X120-20N")
      (description "Chuyển đổi điệp áp 3.3V-5V")
      (libsource (lib "ThuVien") (part "TXS0108EPWR"))
    )
    (comp (ref "U17")
      (value "TXS0108EPWR")
      (footprint "SOP65P640X120-20N")
      (description "Chuyển đổi điệp áp 3.3V-5V")
      (libsource (lib "ThuVien") (part "TXS0108EPWR"))
    )
    (comp (ref "U18")
      (value "TXS0108EPWR")
      (footprint "SOP65P640X120-20N")
      (description "Chuyển đổi điệp áp 3.3V-5V")
      (libsource (lib "ThuVien") (part "TXS0108EPWR"))
    )
    (comp (ref "U19")
      (value "TXS0108EPWR")
      (footprint "SOP65P640X120-20N")
      (description "Chuyển đổi điệp áp 3.3V-5V")
      (libsource (lib "ThuVien") (part "TXS0108EPWR"))
    )
    (comp (ref "U20")
      (value "TXS0108EPWR")
      (footprint "SOP65P640X120-20N")
      (description "Chuyển đổi điệp áp 3.3V-5V")
      (libsource (lib "ThuVien") (part "TXS0108EPWR"))
    )
    (comp (ref "U21")
      (value "TXS0108EPWR")
      (footprint "SOP65P640X120-20N")
      (description "Chuyển đổi điệp áp 3.3V-5V")
      (libsource (lib "ThuVien") (part "TXS0108EPWR"))
    )
    (comp (ref "U22")
      (value "TXS0108EPWR")
      (footprint "SOP65P640X120-20N")
      (description "Chuyển đổi điệp áp 3.3V-5V")
      (libsource (lib "ThuVien") (part "TXS0108EPWR"))
    )
    (comp (ref "U23")
      (value "TXS0108EPWR")
      (footprint "SOP65P640X120-20N")
      (description "Chuyển đổi điệp áp 3.3V-5V")
      (libsource (lib "ThuVien") (part "TXS0108EPWR"))
    )
    (comp (ref "U24")
      (value "TXS0108EPWR")
      (footprint "SOP65P640X120-20N")
      (description "Chuyển đổi điệp áp 3.3V-5V")
      (libsource (lib "ThuVien") (part "TXS0108EPWR"))
    )
    (comp (ref "U25")
      (value "TXS0108EPWR")
      (footprint "SOP65P640X120-20N")
      (description "Chuyển đổi điệp áp 3.3V-5V")
      (libsource (lib "ThuVien") (part "TXS0108EPWR"))
    )
    (comp (ref "U26")
      (value "TXS0108EPWR")
      (footprint "SOP65P640X120-20N")
      (description "Chuyển đổi điệp áp 3.3V-5V")
      (libsource (lib "ThuVien") (part "TXS0108EPWR"))
    )
    (comp (ref "U27")
      (value "CD4040BPWR")
      (footprint "PW16-M")
      (description "Bộ đếm 12bit nhị phân")
      (fields (field (name "COPYRIGHT") "Copyright (C) 2023 Ultra Librarian. All rights reserved."))
      (libsource (lib "ThuVien") (part "CD4040BPWR"))
    )
    (comp (ref "U28")
      (value "CH340C")
      (footprint "CH340C:SOIC127P600X180-16N")
      (description "USB to TTL (thạch anh nội)")
      (fields (field (name "MF") "{'manufacturer': u'WCH'}"))
      (libsource (lib "ThuVien") (part "CH340C"))
    )
    (comp (ref "U29")
      (value "USB-B Through-Hole")
      (footprint "USB2.5-2H4D")
      (libsource (lib "ThuVien") (part "USB-B TH"))
    )
    (comp (ref "X1") (value "СНП-135") (footprint "X2N") (libsource (lib "") (part "X2_1")))
  )
  (nets
    (net (code "1") (name "/A0") (class "Default")
      (node (ref "U1") (pin "5") (pinfunction "A0_5") (pintype "input"))
      (node (ref "U10") (pin "5") (pinfunction "A0_5") (pintype "input"))
      (node (ref "U2") (pin "5") (pinfunction "A0_5") (pintype "input"))
      (node (ref "U27") (pin "9") (pinfunction "Q1_9") (pintype "passive"))
      (node (ref "U3") (pin "5") (pinfunction "A0_5") (pintype "input"))
      (node (ref "U7") (pin "5") (pinfunction "A0_5") (pintype "input"))
      (node (ref "U8") (pin "5") (pinfunction "A0_5") (pintype "input"))
      (node (ref "U9") (pin "5") (pinfunction "A0_5") (pintype "input"))
    )
    (net (code "2") (name "/A1") (class "Default")
      (node (ref "U1") (pin "4") (pinfunction "A1_4") (pintype "input"))
      (node (ref "U10") (pin "4") (pinfunction "A1_4") (pintype "input"))
      (node (ref "U2") (pin "4") (pinfunction "A1_4") (pintype "input"))
      (node (ref "U27") (pin "7") (pinfunction "Q2_7") (pintype "passive"))
      (node (ref "U3") (pin "4") (pinfunction "A1_4") (pintype "input"))
      (node (ref "U7") (pin "4") (pinfunction "A1_4") (pintype "input"))
      (node (ref "U8") (pin "4") (pinfunction "A1_4") (pintype "input"))
      (node (ref "U9") (pin "4") (pinfunction "A1_4") (pintype "input"))
    )
    (net (code "3") (name "/A2") (class "Default")
      (node (ref "U1") (pin "3") (pinfunction "A2_3") (pintype "input"))
      (node (ref "U10") (pin "3") (pinfunction "A2_3") (pintype "input"))
      (node (ref "U2") (pin "3") (pinfunction "A2_3") (pintype "input"))
      (node (ref "U27") (pin "6") (pinfunction "Q3_6") (pintype "passive"))
      (node (ref "U3") (pin "3") (pinfunction "A2_3") (pintype "input"))
      (node (ref "U7") (pin "3") (pinfunction "A2_3") (pintype "input"))
      (node (ref "U8") (pin "3") (pinfunction "A2_3") (pintype "input"))
      (node (ref "U9") (pin "3") (pinfunction "A2_3") (pintype "input"))
    )
    (net (code "4") (name "/A3") (class "Default")
      (node (ref "U1") (pin "2") (pinfunction "A3_2") (pintype "input"))
      (node (ref "U10") (pin "2") (pinfunction "A3_2") (pintype "input"))
      (node (ref "U2") (pin "2") (pinfunction "A3_2") (pintype "input"))
      (node (ref "U27") (pin "5") (pinfunction "Q4_5") (pintype "passive"))
      (node (ref "U3") (pin "2") (pinfunction "A3_2") (pintype "input"))
      (node (ref "U7") (pin "2") (pinfunction "A3_2") (pintype "input"))
      (node (ref "U8") (pin "2") (pinfunction "A3_2") (pintype "input"))
      (node (ref "U9") (pin "2") (pinfunction "A3_2") (pintype "input"))
    )
    (net (code "5") (name "/A4") (class "Default")
      (node (ref "U1") (pin "1") (pinfunction "A4_1") (pintype "input"))
      (node (ref "U10") (pin "1") (pinfunction "A4_1") (pintype "input"))
      (node (ref "U2") (pin "1") (pinfunction "A4_1") (pintype "input"))
      (node (ref "U27") (pin "3") (pinfunction "Q5_3") (pintype "passive"))
      (node (ref "U3") (pin "1") (pinfunction "A4_1") (pintype "input"))
      (node (ref "U7") (pin "1") (pinfunction "A4_1") (pintype "input"))
      (node (ref "U8") (pin "1") (pinfunction "A4_1") (pintype "input"))
      (node (ref "U9") (pin "1") (pinfunction "A4_1") (pintype "input"))
    )
    (net (code "6") (name "/A5") (class "Default")
      (node (ref "U1") (pin "44") (pinfunction "A5_44") (pintype "input"))
      (node (ref "U10") (pin "44") (pinfunction "A5_44") (pintype "input"))
      (node (ref "U2") (pin "44") (pinfunction "A5_44") (pintype "input"))
      (node (ref "U27") (pin "2") (pinfunction "Q6_2") (pintype "passive"))
      (node (ref "U3") (pin "44") (pinfunction "A5_44") (pintype "input"))
      (node (ref "U7") (pin "44") (pinfunction "A5_44") (pintype "input"))
      (node (ref "U8") (pin "44") (pinfunction "A5_44") (pintype "input"))
      (node (ref "U9") (pin "44") (pinfunction "A5_44") (pintype "input"))
    )
    (net (code "7") (name "/A6") (class "Default")
      (node (ref "U1") (pin "43") (pinfunction "A6_43") (pintype "input"))
      (node (ref "U10") (pin "43") (pinfunction "A6_43") (pintype "input"))
      (node (ref "U2") (pin "43") (pinfunction "A6_43") (pintype "input"))
      (node (ref "U27") (pin "4") (pinfunction "Q7_4") (pintype "passive"))
      (node (ref "U3") (pin "43") (pinfunction "A6_43") (pintype "input"))
      (node (ref "U7") (pin "43") (pinfunction "A6_43") (pintype "input"))
      (node (ref "U8") (pin "43") (pinfunction "A6_43") (pintype "input"))
      (node (ref "U9") (pin "43") (pinfunction "A6_43") (pintype "input"))
    )
    (net (code "8") (name "/A7") (class "Default")
      (node (ref "U1") (pin "42") (pinfunction "A7_42") (pintype "input"))
      (node (ref "U10") (pin "42") (pinfunction "A7_42") (pintype "input"))
      (node (ref "U2") (pin "42") (pinfunction "A7_42") (pintype "input"))
      (node (ref "U27") (pin "13") (pinfunction "Q8_13") (pintype "passive"))
      (node (ref "U3") (pin "42") (pinfunction "A7_42") (pintype "input"))
      (node (ref "U7") (pin "42") (pinfunction "A7_42") (pintype "input"))
      (node (ref "U8") (pin "42") (pinfunction "A7_42") (pintype "input"))
      (node (ref "U9") (pin "42") (pinfunction "A7_42") (pintype "input"))
    )
    (net (code "9") (name "/A8") (class "Default")
      (node (ref "U1") (pin "27") (pinfunction "A8_27") (pintype "input"))
      (node (ref "U10") (pin "27") (pinfunction "A8_27") (pintype "input"))
      (node (ref "U2") (pin "27") (pinfunction "A8_27") (pintype "input"))
      (node (ref "U27") (pin "12") (pinfunction "Q9_12") (pintype "passive"))
      (node (ref "U3") (pin "27") (pinfunction "A8_27") (pintype "input"))
      (node (ref "U7") (pin "27") (pinfunction "A8_27") (pintype "input"))
      (node (ref "U8") (pin "27") (pinfunction "A8_27") (pintype "input"))
      (node (ref "U9") (pin "27") (pinfunction "A8_27") (pintype "input"))
    )
    (net (code "10") (name "/A9") (class "Default")
      (node (ref "U1") (pin "26") (pinfunction "A9_26") (pintype "input"))
      (node (ref "U10") (pin "26") (pinfunction "A9_26") (pintype "input"))
      (node (ref "U2") (pin "26") (pinfunction "A9_26") (pintype "input"))
      (node (ref "U27") (pin "14") (pinfunction "Q10_14") (pintype "passive"))
      (node (ref "U3") (pin "26") (pinfunction "A9_26") (pintype "input"))
      (node (ref "U7") (pin "26") (pinfunction "A9_26") (pintype "input"))
      (node (ref "U8") (pin "26") (pinfunction "A9_26") (pintype "input"))
      (node (ref "U9") (pin "26") (pinfunction "A9_26") (pintype "input"))
    )
    (net (code "11") (name "/A10") (class "Default")
      (node (ref "U1") (pin "25") (pinfunction "A10_25") (pintype "input"))
      (node (ref "U10") (pin "25") (pinfunction "A10_25") (pintype "input"))
      (node (ref "U2") (pin "25") (pinfunction "A10_25") (pintype "input"))
      (node (ref "U27") (pin "15") (pinfunction "Q11_15") (pintype "passive"))
      (node (ref "U3") (pin "25") (pinfunction "A10_25") (pintype "input"))
      (node (ref "U7") (pin "25") (pinfunction "A10_25") (pintype "input"))
      (node (ref "U8") (pin "25") (pinfunction "A10_25") (pintype "input"))
      (node (ref "U9") (pin "25") (pinfunction "A10_25") (pintype "input"))
    )
    (net (code "12") (name "/A11") (class "Default")
      (node (ref "U1") (pin "24") (pinfunction "A11_24") (pintype "input"))
      (node (ref "U10") (pin "24") (pinfunction "A11_24") (pintype "input"))
      (node (ref "U2") (pin "24") (pinfunction "A11_24") (pintype "input"))
      (node (ref "U27") (pin "1") (pinfunction "Q12_1") (pintype "passive"))
      (node (ref "U3") (pin "24") (pinfunction "A11_24") (pintype "input"))
      (node (ref "U7") (pin "24") (pinfunction "A11_24") (pintype "input"))
      (node (ref "U8") (pin "24") (pinfunction "A11_24") (pintype "input"))
      (node (ref "U9") (pin "24") (pinfunction "A11_24") (pintype "input"))
    )
    (net (code "13") (name "/A12") (class "Default")
      (node (ref "R19") (pin "2") (pinfunction "2_2") (pintype "passive"))
      (node (ref "U1") (pin "21") (pinfunction "A12_21") (pintype "input"))
      (node (ref "U10") (pin "21") (pinfunction "A12_21") (pintype "input"))
      (node (ref "U2") (pin "21") (pinfunction "A12_21") (pintype "input"))
      (node (ref "U3") (pin "21") (pinfunction "A12_21") (pintype "input"))
      (node (ref "U7") (pin "21") (pinfunction "A12_21") (pintype "input"))
      (node (ref "U8") (pin "21") (pinfunction "A12_21") (pintype "input"))
      (node (ref "U9") (pin "21") (pinfunction "A12_21") (pintype "input"))
    )
    (net (code "14") (name "/A13") (class "Default")
      (node (ref "R20") (pin "2") (pinfunction "2_2") (pintype "passive"))
      (node (ref "U1") (pin "20") (pinfunction "A13_20") (pintype "input"))
      (node (ref "U10") (pin "20") (pinfunction "A13_20") (pintype "input"))
      (node (ref "U2") (pin "20") (pinfunction "A13_20") (pintype "input"))
      (node (ref "U3") (pin "20") (pinfunction "A13_20") (pintype "input"))
      (node (ref "U7") (pin "20") (pinfunction "A13_20") (pintype "input"))
      (node (ref "U8") (pin "20") (pinfunction "A13_20") (pintype "input"))
      (node (ref "U9") (pin "20") (pinfunction "A13_20") (pintype "input"))
    )
    (net (code "15") (name "/A14") (class "Default")
      (node (ref "R21") (pin "2") (pinfunction "2_2") (pintype "passive"))
      (node (ref "U1") (pin "19") (pinfunction "A14_19") (pintype "input"))
      (node (ref "U10") (pin "19") (pinfunction "A14_19") (pintype "input"))
      (node (ref "U2") (pin "19") (pinfunction "A14_19") (pintype "input"))
      (node (ref "U3") (pin "19") (pinfunction "A14_19") (pintype "input"))
      (node (ref "U7") (pin "19") (pinfunction "A14_19") (pintype "input"))
      (node (ref "U8") (pin "19") (pinfunction "A14_19") (pintype "input"))
      (node (ref "U9") (pin "19") (pinfunction "A14_19") (pintype "input"))
    )
    (net (code "16") (name "/A15") (class "Default")
      (node (ref "R23") (pin "2") (pinfunction "2_2") (pintype "passive"))
      (node (ref "U1") (pin "18") (pinfunction "A15_18") (pintype "input"))
      (node (ref "U10") (pin "18") (pinfunction "A15_18") (pintype "input"))
      (node (ref "U2") (pin "18") (pinfunction "A15_18") (pintype "input"))
      (node (ref "U3") (pin "18") (pinfunction "A15_18") (pintype "input"))
      (node (ref "U7") (pin "18") (pinfunction "A15_18") (pintype "input"))
      (node (ref "U8") (pin "18") (pinfunction "A15_18") (pintype "input"))
      (node (ref "U9") (pin "18") (pinfunction "A15_18") (pintype "input"))
    )
    (net (code "17") (name "/CNT_CLK_3.3") (class "Default")
      (node (ref "C60") (pin "70") (pinfunction "70_70") (pintype "passive"))
      (node (ref "U26") (pin "5") (pinfunction "A4_5") (pintype "bidirectional"))
    )
    (net (code "18") (name "/CNT_CLK_5") (class "Default")
      (node (ref "U26") (pin "16") (pinfunction "B4_16") (pintype "bidirectional"))
      (node (ref "U27") (pin "10") (pinfunction "INPUTPULSES_10") (pintype "input"))
    )
    (net (code "19") (name "/CNT_RST_3.3") (class "Default")
      (node (ref "C60") (pin "71") (pinfunction "71_71") (pintype "passive"))
      (node (ref "U26") (pin "4") (pinfunction "A3_4") (pintype "bidirectional"))
    )
    (net (code "20") (name "/CNT_RST_5") (class "Default")
      (node (ref "U26") (pin "17") (pinfunction "B3_17") (pintype "bidirectional"))
      (node (ref "U27") (pin "11") (pinfunction "RESET_11") (pintype "passive"))
    )
    (net (code "21") (name "/D+") (class "Default")
      (node (ref "U28") (pin "5") (pinfunction "UD+_5") (pintype "bidirectional"))
      (node (ref "U29") (pin "3") (pinfunction "D+_3") (pintype "passive"))
    )
    (net (code "22") (name "/D-") (class "Default")
      (node (ref "U28") (pin "6") (pinfunction "UD-_6") (pintype "bidirectional"))
      (node (ref "U29") (pin "2") (pinfunction "D-_2") (pintype "passive"))
    )
    (net (code "23") (name "/IN-P1") (class "Default")
      (node (ref "U13") (pin "20") (pinfunction "B1_20") (pintype "bidirectional"))
      (node (ref "X1") (pin "31") (pinfunction "A31_31") (pintype "passive"))
    )
    (net (code "24") (name "/IN-P2") (class "Default")
      (node (ref "U13") (pin "18") (pinfunction "B2_18") (pintype "bidirectional"))
      (node (ref "X1") (pin "32") (pinfunction "A32_32") (pintype "passive"))
    )
    (net (code "25") (name "/IN-P3") (class "Default")
      (node (ref "U13") (pin "17") (pinfunction "B3_17") (pintype "bidirectional"))
      (node (ref "X1") (pin "33") (pinfunction "A33_33") (pintype "passive"))
    )
    (net (code "26") (name "/IN-P4") (class "Default")
      (node (ref "U13") (pin "16") (pinfunction "B4_16") (pintype "bidirectional"))
      (node (ref "X1") (pin "34") (pinfunction "A34_34") (pintype "passive"))
    )
    (net (code "27") (name "/IN-P5") (class "Default")
      (node (ref "U13") (pin "15") (pinfunction "B5_15") (pintype "bidirectional"))
      (node (ref "X1") (pin "35") (pinfunction "A35_35") (pintype "passive"))
    )
    (net (code "28") (name "/IN-P6") (class "Default")
      (node (ref "U13") (pin "14") (pinfunction "B6_14") (pintype "bidirectional"))
      (node (ref "X1") (pin "36") (pinfunction "A36_36") (pintype "passive"))
    )
    (net (code "29") (name "/IN-P7") (class "Default")
      (node (ref "U13") (pin "13") (pinfunction "B7_13") (pintype "bidirectional"))
      (node (ref "X1") (pin "37") (pinfunction "A37_37") (pintype "passive"))
    )
    (net (code "30") (name "/IN-P8") (class "Default")
      (node (ref "U13") (pin "12") (pinfunction "B8_12") (pintype "bidirectional"))
      (node (ref "X1") (pin "38") (pinfunction "A38_38") (pintype "passive"))
    )
    (net (code "31") (name "/IN-P9") (class "Default")
      (node (ref "U14") (pin "20") (pinfunction "B1_20") (pintype "bidirectional"))
      (node (ref "X1") (pin "39") (pinfunction "A39_39") (pintype "passive"))
    )
    (net (code "32") (name "/IN-P10") (class "Default")
      (node (ref "U14") (pin "18") (pinfunction "B2_18") (pintype "bidirectional"))
      (node (ref "X1") (pin "40") (pinfunction "A40_40") (pintype "passive"))
    )
    (net (code "33") (name "/IN-P11") (class "Default")
      (node (ref "U14") (pin "17") (pinfunction "B3_17") (pintype "bidirectional"))
      (node (ref "X1") (pin "41") (pinfunction "A41_41") (pintype "passive"))
    )
    (net (code "34") (name "/IN-P12") (class "Default")
      (node (ref "U14") (pin "16") (pinfunction "B4_16") (pintype "bidirectional"))
      (node (ref "X1") (pin "42") (pinfunction "A42_42") (pintype "passive"))
    )
    (net (code "35") (name "/IN-P13") (class "Default")
      (node (ref "U14") (pin "15") (pinfunction "B5_15") (pintype "bidirectional"))
      (node (ref "X1") (pin "43") (pinfunction "A43_43") (pintype "passive"))
    )
    (net (code "36") (name "/IN-P14") (class "Default")
      (node (ref "U14") (pin "14") (pinfunction "B6_14") (pintype "bidirectional"))
      (node (ref "X1") (pin "48") (pinfunction "B3_48") (pintype "passive"))
    )
    (net (code "37") (name "/IN-P15") (class "Default")
      (node (ref "U14") (pin "13") (pinfunction "B7_13") (pintype "bidirectional"))
      (node (ref "X1") (pin "51") (pinfunction "B6_51") (pintype "passive"))
    )
    (net (code "38") (name "/IN-P16") (class "Default")
      (node (ref "U14") (pin "12") (pinfunction "B8_12") (pintype "bidirectional"))
      (node (ref "X1") (pin "53") (pinfunction "B8_53") (pintype "passive"))
    )
    (net (code "39") (name "/IN-P17") (class "Default")
      (node (ref "U15") (pin "20") (pinfunction "B1_20") (pintype "bidirectional"))
      (node (ref "X1") (pin "56") (pinfunction "B11_56") (pintype "passive"))
    )
    (net (code "40") (name "/IN-P18") (class "Default")
      (node (ref "U15") (pin "18") (pinfunction "B2_18") (pintype "bidirectional"))
      (node (ref "X1") (pin "57") (pinfunction "B12_57") (pintype "passive"))
    )
    (net (code "41") (name "/IN-P19") (class "Default")
      (node (ref "U15") (pin "17") (pinfunction "B3_17") (pintype "bidirectional"))
      (node (ref "X1") (pin "77") (pinfunction "B32_77") (pintype "passive"))
    )
    (net (code "42") (name "/IN-P20") (class "Default")
      (node (ref "U15") (pin "16") (pinfunction "B4_16") (pintype "bidirectional"))
      (node (ref "X1") (pin "79") (pinfunction "B34_79") (pintype "passive"))
    )
    (net (code "43") (name "/IN-P21") (class "Default")
      (node (ref "U15") (pin "15") (pinfunction "B5_15") (pintype "bidirectional"))
      (node (ref "X1") (pin "83") (pinfunction "B38_83") (pintype "passive"))
    )
    (net (code "44") (name "/IN-P22") (class "Default")
      (node (ref "U15") (pin "14") (pinfunction "B6_14") (pintype "bidirectional"))
      (node (ref "X1") (pin "84") (pinfunction "B39_84") (pintype "passive"))
    )
    (net (code "45") (name "/IN-P23") (class "Default")
      (node (ref "U15") (pin "13") (pinfunction "B7_13") (pintype "bidirectional"))
      (node (ref "X1") (pin "99") (pinfunction "C9_99") (pintype "passive"))
    )
    (net (code "46") (name "/IN-P24") (class "Default")
      (node (ref "U15") (pin "12") (pinfunction "B8_12") (pintype "bidirectional"))
      (node (ref "X1") (pin "100") (pinfunction "C10_100") (pintype "passive"))
    )
    (net (code "47") (name "/IN-P25") (class "Default")
      (node (ref "U20") (pin "20") (pinfunction "B1_20") (pintype "bidirectional"))
      (node (ref "X1") (pin "101") (pinfunction "C11_101") (pintype "passive"))
    )
    (net (code "48") (name "/IN-P26") (class "Default")
      (node (ref "U20") (pin "18") (pinfunction "B2_18") (pintype "bidirectional"))
      (node (ref "X1") (pin "102") (pinfunction "C12_102") (pintype "passive"))
    )
    (net (code "49") (name "/IN-P27") (class "Default")
      (node (ref "U20") (pin "17") (pinfunction "B3_17") (pintype "bidirectional"))
      (node (ref "X1") (pin "103") (pinfunction "C13_103") (pintype "passive"))
    )
    (net (code "50") (name "/IN-P28") (class "Default")
      (node (ref "U20") (pin "16") (pinfunction "B4_16") (pintype "bidirectional"))
      (node (ref "X1") (pin "104") (pinfunction "C14_104") (pintype "passive"))
    )
    (net (code "51") (name "/IN-P29") (class "Default")
      (node (ref "U20") (pin "15") (pinfunction "B5_15") (pintype "bidirectional"))
      (node (ref "X1") (pin "107") (pinfunction "C17_107") (pintype "passive"))
    )
    (net (code "52") (name "/IN-P30") (class "Default")
      (node (ref "U20") (pin "14") (pinfunction "B6_14") (pintype "bidirectional"))
      (node (ref "X1") (pin "108") (pinfunction "C18_108") (pintype "passive"))
    )
    (net (code "53") (name "/IN-P31") (class "Default")
      (node (ref "U20") (pin "13") (pinfunction "B7_13") (pintype "bidirectional"))
      (node (ref "X1") (pin "109") (pinfunction "C19_109") (pintype "passive"))
    )
    (net (code "54") (name "/IN-P32") (class "Default")
      (node (ref "U20") (pin "12") (pinfunction "B8_12") (pintype "bidirectional"))
      (node (ref "X1") (pin "111") (pinfunction "C21_111") (pintype "passive"))
    )
    (net (code "55") (name "/IN-P33") (class "Default")
      (node (ref "U21") (pin "20") (pinfunction "B1_20") (pintype "bidirectional"))
      (node (ref "X1") (pin "112") (pinfunction "C22_112") (pintype "passive"))
    )
    (net (code "56") (name "/IN-P34") (class "Default")
      (node (ref "U21") (pin "18") (pinfunction "B2_18") (pintype "bidirectional"))
      (node (ref "X1") (pin "117") (pinfunction "C27_117") (pintype "passive"))
    )
    (net (code "57") (name "/IN-P35") (class "Default")
      (node (ref "U21") (pin "17") (pinfunction "B3_17") (pintype "bidirectional"))
      (node (ref "X1") (pin "118") (pinfunction "C28_118") (pintype "passive"))
    )
    (net (code "58") (name "/IN-P36") (class "Default")
      (node (ref "U21") (pin "16") (pinfunction "B4_16") (pintype "bidirectional"))
      (node (ref "X1") (pin "119") (pinfunction "C29_119") (pintype "passive"))
    )
    (net (code "59") (name "/IN-P37") (class "Default")
      (node (ref "U21") (pin "15") (pinfunction "B5_15") (pintype "bidirectional"))
      (node (ref "X1") (pin "120") (pinfunction "C30_120") (pintype "passive"))
    )
    (net (code "60") (name "/IN-P38") (class "Default")
      (node (ref "U21") (pin "14") (pinfunction "B6_14") (pintype "bidirectional"))
      (node (ref "X1") (pin "121") (pinfunction "C31_121") (pintype "passive"))
    )
    (net (code "61") (name "/IN-P39") (class "Default")
      (node (ref "U21") (pin "13") (pinfunction "B7_13") (pintype "bidirectional"))
      (node (ref "X1") (pin "122") (pinfunction "C32_122") (pintype "passive"))
    )
    (net (code "62") (name "/IN-P40") (class "Default")
      (node (ref "U21") (pin "12") (pinfunction "B8_12") (pintype "bidirectional"))
      (node (ref "X1") (pin "123") (pinfunction "C33_123") (pintype "passive"))
    )
    (net (code "63") (name "/IN-P41") (class "Default")
      (node (ref "U22") (pin "20") (pinfunction "B1_20") (pintype "bidirectional"))
      (node (ref "X1") (pin "124") (pinfunction "C34_124") (pintype "passive"))
    )
    (net (code "64") (name "/IN-P42") (class "Default")
      (node (ref "U22") (pin "18") (pinfunction "B2_18") (pintype "bidirectional"))
      (node (ref "X1") (pin "125") (pinfunction "C35_125") (pintype "passive"))
    )
    (net (code "65") (name "/IN-P43") (class "Default")
      (node (ref "U22") (pin "17") (pinfunction "B3_17") (pintype "bidirectional"))
      (node (ref "X1") (pin "126") (pinfunction "C36_126") (pintype "passive"))
    )
    (net (code "66") (name "/IN-P44") (class "Default")
      (node (ref "U22") (pin "16") (pinfunction "B4_16") (pintype "bidirectional"))
      (node (ref "X1") (pin "127") (pinfunction "C37_127") (pintype "passive"))
    )
    (net (code "67") (name "/IN-P45") (class "Default")
      (node (ref "U22") (pin "15") (pinfunction "B5_15") (pintype "bidirectional"))
      (node (ref "X1") (pin "128") (pinfunction "C38_128") (pintype "passive"))
    )
    (net (code "68") (name "/IN-P46") (class "Default")
      (node (ref "U22") (pin "14") (pinfunction "B6_14") (pintype "bidirectional"))
      (node (ref "X1") (pin "129") (pinfunction "C39_129") (pintype "passive"))
    )
    (net (code "69") (name "/IN-P47") (class "Default")
      (node (ref "U22") (pin "13") (pinfunction "B7_13") (pintype "bidirectional"))
      (node (ref "X1") (pin "130") (pinfunction "C40_130") (pintype "passive"))
    )
    (net (code "70") (name "/In-OE") (class "Default")
      (node (ref "C60") (pin "69") (pinfunction "69_69") (pintype "passive"))
      (node (ref "C68") (pin "2") (pinfunction "2_2") (pintype "passive"))
      (node (ref "C70") (pin "2") (pinfunction "2_2") (pintype "passive"))
      (node (ref "C72") (pin "2") (pinfunction "2_2") (pintype "passive"))
      (node (ref "C74") (pin "2") (pinfunction "2_2") (pintype "passive"))
      (node (ref "C89") (pin "2") (pinfunction "2_2") (pintype "passive"))
      (node (ref "C91") (pin "2") (pinfunction "2_2") (pintype "passive"))
      (node (ref "C93") (pin "2") (pinfunction "2_2") (pintype "passive"))
      (node (ref "C95") (pin "2") (pinfunction "2_2") (pintype "passive"))
      (node (ref "R15") (pin "1") (pinfunction "1_1") (pintype "passive"))
      (node (ref "R16") (pin "1") (pinfunction "1_1") (pintype "passive"))
      (node (ref "R17") (pin "1") (pinfunction "1_1") (pintype "passive"))
      (node (ref "R18") (pin "1") (pinfunction "1_1") (pintype "passive"))
      (node (ref "R6") (pin "1") (pinfunction "1_1") (pintype "passive"))
      (node (ref "R7") (pin "1") (pinfunction "1_1") (pintype "passive"))
      (node (ref "R8") (pin "1") (pinfunction "1_1") (pintype "passive"))
      (node (ref "R9") (pin "1") (pinfunction "1_1") (pintype "passive"))
      (node (ref "U16") (pin "10") (pinfunction "OE_10") (pintype "input"))
      (node (ref "U17") (pin "10") (pinfunction "OE_10") (pintype "input"))
      (node (ref "U18") (pin "10") (pinfunction "OE_10") (pintype "input"))
      (node (ref "U19") (pin "10") (pinfunction "OE_10") (pintype "input"))
      (node (ref "U23") (pin "10") (pinfunction "OE_10") (pintype "input"))
      (node (ref "U24") (pin "10") (pinfunction "OE_10") (pintype "input"))
      (node (ref "U25") (pin "10") (pinfunction "OE_10") (pintype "input"))
      (node (ref "U26") (pin "10") (pinfunction "OE_10") (pintype "input"))
    )
    (net (code "71") (name "/In-{slash}CE") (class "Default")
      (node (ref "C60") (pin "72") (pinfunction "72_72") (pintype "passive"))
      (node (ref "C60") (pin "73") (pinfunction "73_73") (pintype "passive"))
      (node (ref "C60") (pin "74") (pinfunction "74_74") (pintype "passive"))
      (node (ref "R10") (pin "2") (pinfunction "2_2") (pintype "passive"))
      (node (ref "U10") (pin "17") (pinfunction "*WE_17") (pintype "input"))
      (node (ref "U10") (pin "41") (pinfunction "*OE_41") (pintype "bidirectional"))
      (node (ref "U10") (pin "6") (pinfunction "*CE_6") (pintype "input"))
      (node (ref "U7") (pin "17") (pinfunction "*WE_17") (pintype "input"))
      (node (ref "U7") (pin "41") (pinfunction "*OE_41") (pintype "bidirectional"))
      (node (ref "U7") (pin "6") (pinfunction "*CE_6") (pintype "input"))
      (node (ref "U8") (pin "17") (pinfunction "*WE_17") (pintype "input"))
      (node (ref "U8") (pin "41") (pinfunction "*OE_41") (pintype "bidirectional"))
      (node (ref "U8") (pin "6") (pinfunction "*CE_6") (pintype "input"))
      (node (ref "U9") (pin "17") (pinfunction "*WE_17") (pintype "input"))
      (node (ref "U9") (pin "41") (pinfunction "*OE_41") (pintype "bidirectional"))
      (node (ref "U9") (pin "6") (pinfunction "*CE_6") (pintype "input"))
    )
    (net (code "72") (name "/OUT-P69") (class "Default")
      (node (ref "U16") (pin "20") (pinfunction "B1_20") (pintype "bidirectional"))
      (node (ref "X1") (pin "1") (pinfunction "A1_1") (pintype "passive"))
    )
    (net (code "73") (name "/OUT-P70") (class "Default")
      (node (ref "U16") (pin "18") (pinfunction "B2_18") (pintype "bidirectional"))
      (node (ref "X1") (pin "2") (pinfunction "A2_2") (pintype "passive"))
    )
    (net (code "74") (name "/OUT-P71") (class "Default")
      (node (ref "U16") (pin "17") (pinfunction "B3_17") (pintype "bidirectional"))
      (node (ref "X1") (pin "3") (pinfunction "A3_3") (pintype "passive"))
    )
    (net (code "75") (name "/OUT-P72") (class "Default")
      (node (ref "U16") (pin "16") (pinfunction "B4_16") (pintype "bidirectional"))
      (node (ref "X1") (pin "4") (pinfunction "A4_4") (pintype "passive"))
    )
    (net (code "76") (name "/OUT-P73") (class "Default")
      (node (ref "U16") (pin "15") (pinfunction "B5_15") (pintype "bidirectional"))
      (node (ref "X1") (pin "5") (pinfunction "A5_5") (pintype "passive"))
    )
    (net (code "77") (name "/OUT-P74") (class "Default")
      (node (ref "U16") (pin "14") (pinfunction "B6_14") (pintype "bidirectional"))
      (node (ref "X1") (pin "6") (pinfunction "A6_6") (pintype "passive"))
    )
    (net (code "78") (name "/OUT-P75") (class "Default")
      (node (ref "U16") (pin "13") (pinfunction "B7_13") (pintype "bidirectional"))
      (node (ref "X1") (pin "7") (pinfunction "A7_7") (pintype "passive"))
    )
    (net (code "79") (name "/OUT-P76") (class "Default")
      (node (ref "U16") (pin "12") (pinfunction "B8_12") (pintype "bidirectional"))
      (node (ref "X1") (pin "8") (pinfunction "A8_8") (pintype "passive"))
    )
    (net (code "80") (name "/OUT-P77") (class "Default")
      (node (ref "U17") (pin "20") (pinfunction "B1_20") (pintype "bidirectional"))
      (node (ref "X1") (pin "9") (pinfunction "A9_9") (pintype "passive"))
    )
    (net (code "81") (name "/OUT-P78") (class "Default")
      (node (ref "U17") (pin "18") (pinfunction "B2_18") (pintype "bidirectional"))
      (node (ref "X1") (pin "10") (pinfunction "A10_10") (pintype "passive"))
    )
    (net (code "82") (name "/OUT-P79") (class "Default")
      (node (ref "U17") (pin "17") (pinfunction "B3_17") (pintype "bidirectional"))
      (node (ref "X1") (pin "11") (pinfunction "A11_11") (pintype "passive"))
    )
    (net (code "83") (name "/OUT-P80") (class "Default")
      (node (ref "U17") (pin "16") (pinfunction "B4_16") (pintype "bidirectional"))
      (node (ref "X1") (pin "12") (pinfunction "A12_12") (pintype "passive"))
    )
    (net (code "84") (name "/OUT-P81") (class "Default")
      (node (ref "U17") (pin "15") (pinfunction "B5_15") (pintype "bidirectional"))
      (node (ref "X1") (pin "13") (pinfunction "A13_13") (pintype "passive"))
    )
    (net (code "85") (name "/OUT-P82") (class "Default")
      (node (ref "U17") (pin "14") (pinfunction "B6_14") (pintype "bidirectional"))
      (node (ref "X1") (pin "14") (pinfunction "A14_14") (pintype "passive"))
    )
    (net (code "86") (name "/OUT-P83") (class "Default")
      (node (ref "U17") (pin "13") (pinfunction "B7_13") (pintype "bidirectional"))
      (node (ref "X1") (pin "15") (pinfunction "A15_15") (pintype "passive"))
    )
    (net (code "87") (name "/OUT-P84") (class "Default")
      (node (ref "U17") (pin "12") (pinfunction "B8_12") (pintype "bidirectional"))
      (node (ref "X1") (pin "16") (pinfunction "A16_16") (pintype "passive"))
    )
    (net (code "88") (name "/OUT-P85") (class "Default")
      (node (ref "U18") (pin "20") (pinfunction "B1_20") (pintype "bidirectional"))
      (node (ref "X1") (pin "17") (pinfunction "A17_17") (pintype "passive"))
    )
    (net (code "89") (name "/OUT-P86") (class "Default")
      (node (ref "U18") (pin "18") (pinfunction "B2_18") (pintype "bidirectional"))
      (node (ref "X1") (pin "18") (pinfunction "A18_18") (pintype "passive"))
    )
    (net (code "90") (name "/OUT-P87") (class "Default")
      (node (ref "U18") (pin "17") (pinfunction "B3_17") (pintype "bidirectional"))
      (node (ref "X1") (pin "19") (pinfunction "A19_19") (pintype "passive"))
    )
    (net (code "91") (name "/OUT-P88") (class "Default")
      (node (ref "U18") (pin "16") (pinfunction "B4_16") (pintype "bidirectional"))
      (node (ref "X1") (pin "20") (pinfunction "A20_20") (pintype "passive"))
    )
    (net (code "92") (name "/OUT-P89") (class "Default")
      (node (ref "U18") (pin "15") (pinfunction "B5_15") (pintype "bidirectional"))
      (node (ref "X1") (pin "21") (pinfunction "A21_21") (pintype "passive"))
    )
    (net (code "93") (name "/OUT-P90") (class "Default")
      (node (ref "U18") (pin "14") (pinfunction "B6_14") (pintype "bidirectional"))
      (node (ref "X1") (pin "22") (pinfunction "A22_22") (pintype "passive"))
    )
    (net (code "94") (name "/OUT-P91") (class "Default")
      (node (ref "U18") (pin "13") (pinfunction "B7_13") (pintype "bidirectional"))
      (node (ref "X1") (pin "23") (pinfunction "A23_23") (pintype "passive"))
    )
    (net (code "95") (name "/OUT-P92") (class "Default")
      (node (ref "U18") (pin "12") (pinfunction "B8_12") (pintype "bidirectional"))
      (node (ref "X1") (pin "24") (pinfunction "A24_24") (pintype "passive"))
    )
    (net (code "96") (name "/OUT-P93") (class "Default")
      (node (ref "U19") (pin "20") (pinfunction "B1_20") (pintype "bidirectional"))
      (node (ref "X1") (pin "25") (pinfunction "A25_25") (pintype "passive"))
    )
    (net (code "97") (name "/OUT-P94") (class "Default")
      (node (ref "U19") (pin "18") (pinfunction "B2_18") (pintype "bidirectional"))
      (node (ref "X1") (pin "26") (pinfunction "A26_26") (pintype "passive"))
    )
    (net (code "98") (name "/OUT-P95") (class "Default")
      (node (ref "U19") (pin "17") (pinfunction "B3_17") (pintype "bidirectional"))
      (node (ref "X1") (pin "27") (pinfunction "A27_27") (pintype "passive"))
    )
    (net (code "99") (name "/OUT-P96") (class "Default")
      (node (ref "U19") (pin "16") (pinfunction "B4_16") (pintype "bidirectional"))
      (node (ref "X1") (pin "28") (pinfunction "A28_28") (pintype "passive"))
    )
    (net (code "100") (name "/OUT-P97") (class "Default")
      (node (ref "U19") (pin "15") (pinfunction "B5_15") (pintype "bidirectional"))
      (node (ref "X1") (pin "29") (pinfunction "A29_29") (pintype "passive"))
    )
    (net (code "101") (name "/OUT-P98") (class "Default")
      (node (ref "U19") (pin "14") (pinfunction "B6_14") (pintype "bidirectional"))
      (node (ref "X1") (pin "30") (pinfunction "A30_30") (pintype "passive"))
    )
    (net (code "102") (name "/OUT-P99") (class "Default")
      (node (ref "U19") (pin "13") (pinfunction "B7_13") (pintype "bidirectional"))
      (node (ref "X1") (pin "47") (pinfunction "B2_47") (pintype "passive"))
    )
    (net (code "103") (name "/OUT-P100") (class "Default")
      (node (ref "U19") (pin "12") (pinfunction "B8_12") (pintype "bidirectional"))
      (node (ref "X1") (pin "50") (pinfunction "B5_50") (pintype "passive"))
    )
    (net (code "104") (name "/OUT-P101") (class "Default")
      (node (ref "U23") (pin "20") (pinfunction "B1_20") (pintype "bidirectional"))
      (node (ref "X1") (pin "52") (pinfunction "B7_52") (pintype "passive"))
    )
    (net (code "105") (name "/OUT-P102") (class "Default")
      (node (ref "U23") (pin "18") (pinfunction "B2_18") (pintype "bidirectional"))
      (node (ref "X1") (pin "54") (pinfunction "B9_54") (pintype "passive"))
    )
    (net (code "106") (name "/OUT-P103") (class "Default")
      (node (ref "U23") (pin "17") (pinfunction "B3_17") (pintype "bidirectional"))
      (node (ref "X1") (pin "59") (pinfunction "B14_59") (pintype "passive"))
    )
    (net (code "107") (name "/OUT-P104") (class "Default")
      (node (ref "U23") (pin "16") (pinfunction "B4_16") (pintype "bidirectional"))
      (node (ref "X1") (pin "60") (pinfunction "B15_60") (pintype "passive"))
    )
    (net (code "108") (name "/OUT-P105") (class "Default")
      (node (ref "U23") (pin "15") (pinfunction "B5_15") (pintype "bidirectional"))
      (node (ref "X1") (pin "61") (pinfunction "B16_61") (pintype "passive"))
    )
    (net (code "109") (name "/OUT-P106") (class "Default")
      (node (ref "U23") (pin "14") (pinfunction "B6_14") (pintype "bidirectional"))
      (node (ref "X1") (pin "62") (pinfunction "B17_62") (pintype "passive"))
    )
    (net (code "110") (name "/OUT-P107") (class "Default")
      (node (ref "U23") (pin "13") (pinfunction "B7_13") (pintype "bidirectional"))
      (node (ref "X1") (pin "64") (pinfunction "B19_64") (pintype "passive"))
    )
    (net (code "111") (name "/OUT-P108") (class "Default")
      (node (ref "U23") (pin "12") (pinfunction "B8_12") (pintype "bidirectional"))
      (node (ref "X1") (pin "65") (pinfunction "B20_65") (pintype "passive"))
    )
    (net (code "112") (name "/OUT-P109") (class "Default")
      (node (ref "U24") (pin "20") (pinfunction "B1_20") (pintype "bidirectional"))
      (node (ref "X1") (pin "67") (pinfunction "B22_67") (pintype "passive"))
    )
    (net (code "113") (name "/OUT-P110") (class "Default")
      (node (ref "U24") (pin "18") (pinfunction "B2_18") (pintype "bidirectional"))
      (node (ref "X1") (pin "68") (pinfunction "B23_68") (pintype "passive"))
    )
    (net (code "114") (name "/OUT-P111") (class "Default")
      (node (ref "U24") (pin "17") (pinfunction "B3_17") (pintype "bidirectional"))
      (node (ref "X1") (pin "71") (pinfunction "B26_71") (pintype "passive"))
    )
    (net (code "115") (name "/OUT-P112") (class "Default")
      (node (ref "U24") (pin "16") (pinfunction "B4_16") (pintype "bidirectional"))
      (node (ref "X1") (pin "72") (pinfunction "B27_72") (pintype "passive"))
    )
    (net (code "116") (name "/OUT-P113") (class "Default")
      (node (ref "U24") (pin "15") (pinfunction "B5_15") (pintype "bidirectional"))
      (node (ref "X1") (pin "76") (pinfunction "B31_76") (pintype "passive"))
    )
    (net (code "117") (name "/OUT-P114") (class "Default")
      (node (ref "U24") (pin "14") (pinfunction "B6_14") (pintype "bidirectional"))
      (node (ref "X1") (pin "82") (pinfunction "B37_82") (pintype "passive"))
    )
    (net (code "118") (name "/OUT-P115") (class "Default")
      (node (ref "U24") (pin "13") (pinfunction "B7_13") (pintype "bidirectional"))
      (node (ref "X1") (pin "88") (pinfunction "B43_88") (pintype "passive"))
    )
    (net (code "119") (name "/OUT-P116") (class "Default")
      (node (ref "U24") (pin "12") (pinfunction "B8_12") (pintype "bidirectional"))
      (node (ref "X1") (pin "89") (pinfunction "B44_89") (pintype "passive"))
    )
    (net (code "120") (name "/OUT-P117") (class "Default")
      (node (ref "U25") (pin "20") (pinfunction "B1_20") (pintype "bidirectional"))
      (node (ref "X1") (pin "91") (pinfunction "C1_91") (pintype "passive"))
    )
    (net (code "121") (name "/OUT-P118") (class "Default")
      (node (ref "U25") (pin "18") (pinfunction "B2_18") (pintype "bidirectional"))
      (node (ref "X1") (pin "92") (pinfunction "C2_92") (pintype "passive"))
    )
    (net (code "122") (name "/OUT-P119") (class "Default")
      (node (ref "U25") (pin "17") (pinfunction "B3_17") (pintype "bidirectional"))
      (node (ref "X1") (pin "93") (pinfunction "C3_93") (pintype "passive"))
    )
    (net (code "123") (name "/OUT-P120") (class "Default")
      (node (ref "U25") (pin "16") (pinfunction "B4_16") (pintype "bidirectional"))
      (node (ref "X1") (pin "94") (pinfunction "C4_94") (pintype "passive"))
    )
    (net (code "124") (name "/OUT-P121") (class "Default")
      (node (ref "U25") (pin "15") (pinfunction "B5_15") (pintype "bidirectional"))
      (node (ref "X1") (pin "95") (pinfunction "C5_95") (pintype "passive"))
    )
    (net (code "125") (name "/OUT-P122") (class "Default")
      (node (ref "U25") (pin "14") (pinfunction "B6_14") (pintype "bidirectional"))
      (node (ref "X1") (pin "96") (pinfunction "C6_96") (pintype "passive"))
    )
    (net (code "126") (name "/OUT-P123") (class "Default")
      (node (ref "U25") (pin "13") (pinfunction "B7_13") (pintype "bidirectional"))
      (node (ref "X1") (pin "97") (pinfunction "C7_97") (pintype "passive"))
    )
    (net (code "127") (name "/OUT-P124") (class "Default")
      (node (ref "U25") (pin "12") (pinfunction "B8_12") (pintype "bidirectional"))
      (node (ref "X1") (pin "98") (pinfunction "C8_98") (pintype "passive"))
    )
    (net (code "128") (name "/OUT-P125") (class "Default")
      (node (ref "U26") (pin "20") (pinfunction "B1_20") (pintype "bidirectional"))
      (node (ref "X1") (pin "106") (pinfunction "C16_106") (pintype "passive"))
    )
    (net (code "129") (name "/OUT-P126") (class "Default")
      (node (ref "U26") (pin "18") (pinfunction "B2_18") (pintype "bidirectional"))
      (node (ref "X1") (pin "135") (pinfunction "C45_135") (pintype "passive"))
    )
    (net (code "130") (name "/Out-OE") (class "Default")
      (node (ref "C61") (pin "62") (pinfunction "62_62") (pintype "passive"))
      (node (ref "C62") (pin "2") (pinfunction "2_2") (pintype "passive"))
      (node (ref "C64") (pin "2") (pinfunction "2_2") (pintype "passive"))
      (node (ref "C66") (pin "2") (pinfunction "2_2") (pintype "passive"))
      (node (ref "C83") (pin "2") (pinfunction "2_2") (pintype "passive"))
      (node (ref "C85") (pin "2") (pinfunction "2_2") (pintype "passive"))
      (node (ref "C87") (pin "2") (pinfunction "2_2") (pintype "passive"))
      (node (ref "R12") (pin "1") (pinfunction "1_1") (pintype "passive"))
      (node (ref "R13") (pin "1") (pinfunction "1_1") (pintype "passive"))
      (node (ref "R14") (pin "1") (pinfunction "1_1") (pintype "passive"))
      (node (ref "R3") (pin "1") (pinfunction "1_1") (pintype "passive"))
      (node (ref "R4") (pin "1") (pinfunction "1_1") (pintype "passive"))
      (node (ref "R5") (pin "1") (pinfunction "1_1") (pintype "passive"))
      (node (ref "U13") (pin "10") (pinfunction "OE_10") (pintype "input"))
      (node (ref "U14") (pin "10") (pinfunction "OE_10") (pintype "input"))
      (node (ref "U15") (pin "10") (pinfunction "OE_10") (pintype "input"))
      (node (ref "U20") (pin "10") (pinfunction "OE_10") (pintype "input"))
      (node (ref "U21") (pin "10") (pinfunction "OE_10") (pintype "input"))
      (node (ref "U22") (pin "10") (pinfunction "OE_10") (pintype "input"))
    )
    (net (code "131") (name "/Out-{slash}CE") (class "Default")
      (node (ref "C61") (pin "63") (pinfunction "63_63") (pintype "passive"))
      (node (ref "C61") (pin "64") (pinfunction "64_64") (pintype "passive"))
      (node (ref "C61") (pin "65") (pinfunction "65_65") (pintype "passive"))
      (node (ref "R11") (pin "2") (pinfunction "2_2") (pintype "passive"))
      (node (ref "U1") (pin "17") (pinfunction "*WE_17") (pintype "input"))
      (node (ref "U1") (pin "41") (pinfunction "*OE_41") (pintype "bidirectional"))
      (node (ref "U1") (pin "6") (pinfunction "*CE_6") (pintype "input"))
      (node (ref "U2") (pin "17") (pinfunction "*WE_17") (pintype "input"))
      (node (ref "U2") (pin "41") (pinfunction "*OE_41") (pintype "bidirectional"))
      (node (ref "U2") (pin "6") (pinfunction "*CE_6") (pintype "input"))
      (node (ref "U3") (pin "17") (pinfunction "*WE_17") (pintype "input"))
      (node (ref "U3") (pin "41") (pinfunction "*OE_41") (pintype "bidirectional"))
      (node (ref "U3") (pin "6") (pinfunction "*CE_6") (pintype "input"))
    )
    (net (code "132") (name "/P1") (class "Default")
      (node (ref "C61") (pin "3") (pinfunction "3_3") (pintype "passive"))
      (node (ref "U1") (pin "7") (pinfunction "I/O0_7") (pintype "bidirectional"))
      (node (ref "U13") (pin "1") (pinfunction "A1_1") (pintype "bidirectional"))
    )
    (net (code "133") (name "/P2") (class "Default")
      (node (ref "C61") (pin "4") (pinfunction "4_4") (pintype "passive"))
      (node (ref "U1") (pin "8") (pinfunction "I/O1_8") (pintype "bidirectional"))
      (node (ref "U13") (pin "3") (pinfunction "A2_3") (pintype "bidirectional"))
    )
    (net (code "134") (name "/P3") (class "Default")
      (node (ref "C61") (pin "5") (pinfunction "5_5") (pintype "passive"))
      (node (ref "U1") (pin "9") (pinfunction "I/O2_9") (pintype "bidirectional"))
      (node (ref "U13") (pin "4") (pinfunction "A3_4") (pintype "bidirectional"))
    )
    (net (code "135") (name "/P4") (class "Default")
      (node (ref "C61") (pin "6") (pinfunction "6_6") (pintype "passive"))
      (node (ref "U1") (pin "10") (pinfunction "I/O3_10") (pintype "bidirectional"))
      (node (ref "U13") (pin "5") (pinfunction "A4_5") (pintype "bidirectional"))
    )
    (net (code "136") (name "/P5") (class "Default")
      (node (ref "C61") (pin "7") (pinfunction "7_7") (pintype "passive"))
      (node (ref "U1") (pin "13") (pinfunction "I/O4_13") (pintype "bidirectional"))
      (node (ref "U13") (pin "6") (pinfunction "A5_6") (pintype "bidirectional"))
    )
    (net (code "137") (name "/P6") (class "Default")
      (node (ref "C61") (pin "8") (pinfunction "8_8") (pintype "passive"))
      (node (ref "U1") (pin "14") (pinfunction "I/O5_14") (pintype "bidirectional"))
      (node (ref "U13") (pin "7") (pinfunction "A6_7") (pintype "bidirectional"))
    )
    (net (code "138") (name "/P7") (class "Default")
      (node (ref "C61") (pin "9") (pinfunction "9_9") (pintype "passive"))
      (node (ref "U1") (pin "15") (pinfunction "I/O6_15") (pintype "bidirectional"))
      (node (ref "U13") (pin "8") (pinfunction "A7_8") (pintype "bidirectional"))
    )
    (net (code "139") (name "/P8") (class "Default")
      (node (ref "C61") (pin "10") (pinfunction "10_10") (pintype "passive"))
      (node (ref "U1") (pin "16") (pinfunction "I/O7_16") (pintype "bidirectional"))
      (node (ref "U13") (pin "9") (pinfunction "A8_9") (pintype "bidirectional"))
    )
    (net (code "140") (name "/P9") (class "Default")
      (node (ref "C61") (pin "11") (pinfunction "11_11") (pintype "passive"))
      (node (ref "U1") (pin "29") (pinfunction "I/O8_29") (pintype "bidirectional"))
      (node (ref "U14") (pin "1") (pinfunction "A1_1") (pintype "bidirectional"))
    )
    (net (code "141") (name "/P10") (class "Default")
      (node (ref "C61") (pin "12") (pinfunction "12_12") (pintype "passive"))
      (node (ref "U1") (pin "30") (pinfunction "I/O9_30") (pintype "bidirectional"))
      (node (ref "U14") (pin "3") (pinfunction "A2_3") (pintype "bidirectional"))
    )
    (net (code "142") (name "/P11") (class "Default")
      (node (ref "C61") (pin "13") (pinfunction "13_13") (pintype "passive"))
      (node (ref "U1") (pin "31") (pinfunction "I/O10_31") (pintype "bidirectional"))
      (node (ref "U14") (pin "4") (pinfunction "A3_4") (pintype "bidirectional"))
    )
    (net (code "143") (name "/P12") (class "Default")
      (node (ref "C61") (pin "14") (pinfunction "14_14") (pintype "passive"))
      (node (ref "U1") (pin "32") (pinfunction "I/O11_32") (pintype "bidirectional"))
      (node (ref "U14") (pin "5") (pinfunction "A4_5") (pintype "bidirectional"))
    )
    (net (code "144") (name "/P13") (class "Default")
      (node (ref "C61") (pin "15") (pinfunction "15_15") (pintype "passive"))
      (node (ref "U1") (pin "35") (pinfunction "I/O12_35") (pintype "bidirectional"))
      (node (ref "U14") (pin "6") (pinfunction "A5_6") (pintype "bidirectional"))
    )
    (net (code "145") (name "/P14") (class "Default")
      (node (ref "C61") (pin "16") (pinfunction "16_16") (pintype "passive"))
      (node (ref "U1") (pin "36") (pinfunction "I/O13_36") (pintype "bidirectional"))
      (node (ref "U14") (pin "7") (pinfunction "A6_7") (pintype "bidirectional"))
    )
    (net (code "146") (name "/P15") (class "Default")
      (node (ref "C61") (pin "17") (pinfunction "17_17") (pintype "passive"))
      (node (ref "U1") (pin "37") (pinfunction "I/O14_37") (pintype "bidirectional"))
      (node (ref "U14") (pin "8") (pinfunction "A7_8") (pintype "bidirectional"))
    )
    (net (code "147") (name "/P16") (class "Default")
      (node (ref "C61") (pin "18") (pinfunction "18_18") (pintype "passive"))
      (node (ref "U1") (pin "38") (pinfunction "I/O15_38") (pintype "bidirectional"))
      (node (ref "U14") (pin "9") (pinfunction "A8_9") (pintype "bidirectional"))
    )
    (net (code "148") (name "/P17") (class "Default")
      (node (ref "C61") (pin "19") (pinfunction "19_19") (pintype "passive"))
      (node (ref "U15") (pin "1") (pinfunction "A1_1") (pintype "bidirectional"))
      (node (ref "U2") (pin "7") (pinfunction "I/O0_7") (pintype "bidirectional"))
    )
    (net (code "149") (name "/P18") (class "Default")
      (node (ref "C61") (pin "20") (pinfunction "20_20") (pintype "passive"))
      (node (ref "U15") (pin "3") (pinfunction "A2_3") (pintype "bidirectional"))
      (node (ref "U2") (pin "8") (pinfunction "I/O1_8") (pintype "bidirectional"))
    )
    (net (code "150") (name "/P19") (class "Default")
      (node (ref "C61") (pin "21") (pinfunction "21_21") (pintype "passive"))
      (node (ref "U15") (pin "4") (pinfunction "A3_4") (pintype "bidirectional"))
      (node (ref "U2") (pin "9") (pinfunction "I/O2_9") (pintype "bidirectional"))
    )
    (net (code "151") (name "/P20") (class "Default")
      (node (ref "C61") (pin "22") (pinfunction "22_22") (pintype "passive"))
      (node (ref "U15") (pin "5") (pinfunction "A4_5") (pintype "bidirectional"))
      (node (ref "U2") (pin "10") (pinfunction "I/O3_10") (pintype "bidirectional"))
    )
    (net (code "152") (name "/P21") (class "Default")
      (node (ref "C61") (pin "23") (pinfunction "23_23") (pintype "passive"))
      (node (ref "U15") (pin "6") (pinfunction "A5_6") (pintype "bidirectional"))
      (node (ref "U2") (pin "13") (pinfunction "I/O4_13") (pintype "bidirectional"))
    )
    (net (code "153") (name "/P22") (class "Default")
      (node (ref "C61") (pin "24") (pinfunction "24_24") (pintype "passive"))
      (node (ref "U15") (pin "7") (pinfunction "A6_7") (pintype "bidirectional"))
      (node (ref "U2") (pin "14") (pinfunction "I/O5_14") (pintype "bidirectional"))
    )
    (net (code "154") (name "/P23") (class "Default")
      (node (ref "C61") (pin "25") (pinfunction "25_25") (pintype "passive"))
      (node (ref "U15") (pin "8") (pinfunction "A7_8") (pintype "bidirectional"))
      (node (ref "U2") (pin "15") (pinfunction "I/O6_15") (pintype "bidirectional"))
    )
    (net (code "155") (name "/P24") (class "Default")
      (node (ref "C61") (pin "26") (pinfunction "26_26") (pintype "passive"))
      (node (ref "U15") (pin "9") (pinfunction "A8_9") (pintype "bidirectional"))
      (node (ref "U2") (pin "16") (pinfunction "I/O7_16") (pintype "bidirectional"))
    )
    (net (code "156") (name "/P25") (class "Default")
      (node (ref "C61") (pin "27") (pinfunction "27_27") (pintype "passive"))
      (node (ref "U2") (pin "29") (pinfunction "I/O8_29") (pintype "bidirectional"))
      (node (ref "U20") (pin "1") (pinfunction "A1_1") (pintype "bidirectional"))
    )
    (net (code "157") (name "/P26") (class "Default")
      (node (ref "C61") (pin "28") (pinfunction "28_28") (pintype "passive"))
      (node (ref "U2") (pin "30") (pinfunction "I/O9_30") (pintype "bidirectional"))
      (node (ref "U20") (pin "3") (pinfunction "A2_3") (pintype "bidirectional"))
    )
    (net (code "158") (name "/P27") (class "Default")
      (node (ref "C61") (pin "29") (pinfunction "29_29") (pintype "passive"))
      (node (ref "U2") (pin "31") (pinfunction "I/O10_31") (pintype "bidirectional"))
      (node (ref "U20") (pin "4") (pinfunction "A3_4") (pintype "bidirectional"))
    )
    (net (code "159") (name "/P28") (class "Default")
      (node (ref "C61") (pin "30") (pinfunction "30_30") (pintype "passive"))
      (node (ref "U2") (pin "32") (pinfunction "I/O11_32") (pintype "bidirectional"))
      (node (ref "U20") (pin "5") (pinfunction "A4_5") (pintype "bidirectional"))
    )
    (net (code "160") (name "/P29") (class "Default")
      (node (ref "C61") (pin "31") (pinfunction "31_31") (pintype "passive"))
      (node (ref "U2") (pin "35") (pinfunction "I/O12_35") (pintype "bidirectional"))
      (node (ref "U20") (pin "6") (pinfunction "A5_6") (pintype "bidirectional"))
    )
    (net (code "161") (name "/P30") (class "Default")
      (node (ref "C61") (pin "32") (pinfunction "32_32") (pintype "passive"))
      (node (ref "U2") (pin "36") (pinfunction "I/O13_36") (pintype "bidirectional"))
      (node (ref "U20") (pin "7") (pinfunction "A6_7") (pintype "bidirectional"))
    )
    (net (code "162") (name "/P31") (class "Default")
      (node (ref "C61") (pin "33") (pinfunction "33_33") (pintype "passive"))
      (node (ref "U2") (pin "37") (pinfunction "I/O14_37") (pintype "bidirectional"))
      (node (ref "U20") (pin "8") (pinfunction "A7_8") (pintype "bidirectional"))
    )
    (net (code "163") (name "/P32") (class "Default")
      (node (ref "C61") (pin "34") (pinfunction "34_34") (pintype "passive"))
      (node (ref "U2") (pin "38") (pinfunction "I/O15_38") (pintype "bidirectional"))
      (node (ref "U20") (pin "9") (pinfunction "A8_9") (pintype "bidirectional"))
    )
    (net (code "164") (name "/P33") (class "Default")
      (node (ref "C61") (pin "35") (pinfunction "35_35") (pintype "passive"))
      (node (ref "U21") (pin "1") (pinfunction "A1_1") (pintype "bidirectional"))
      (node (ref "U3") (pin "7") (pinfunction "I/O0_7") (pintype "bidirectional"))
    )
    (net (code "165") (name "/P34") (class "Default")
      (node (ref "C61") (pin "36") (pinfunction "36_36") (pintype "passive"))
      (node (ref "U21") (pin "3") (pinfunction "A2_3") (pintype "bidirectional"))
      (node (ref "U3") (pin "8") (pinfunction "I/O1_8") (pintype "bidirectional"))
    )
    (net (code "166") (name "/P35") (class "Default")
      (node (ref "C61") (pin "45") (pinfunction "45_45") (pintype "passive"))
      (node (ref "U21") (pin "4") (pinfunction "A3_4") (pintype "bidirectional"))
      (node (ref "U3") (pin "9") (pinfunction "I/O2_9") (pintype "bidirectional"))
    )
    (net (code "167") (name "/P36") (class "Default")
      (node (ref "C61") (pin "46") (pinfunction "46_46") (pintype "passive"))
      (node (ref "U21") (pin "5") (pinfunction "A4_5") (pintype "bidirectional"))
      (node (ref "U3") (pin "10") (pinfunction "I/O3_10") (pintype "bidirectional"))
    )
    (net (code "168") (name "/P37") (class "Default")
      (node (ref "C61") (pin "47") (pinfunction "47_47") (pintype "passive"))
      (node (ref "U21") (pin "6") (pinfunction "A5_6") (pintype "bidirectional"))
      (node (ref "U3") (pin "13") (pinfunction "I/O4_13") (pintype "bidirectional"))
    )
    (net (code "169") (name "/P38") (class "Default")
      (node (ref "C61") (pin "48") (pinfunction "48_48") (pintype "passive"))
      (node (ref "U21") (pin "7") (pinfunction "A6_7") (pintype "bidirectional"))
      (node (ref "U3") (pin "14") (pinfunction "I/O5_14") (pintype "bidirectional"))
    )
    (net (code "170") (name "/P39") (class "Default")
      (node (ref "C61") (pin "49") (pinfunction "49_49") (pintype "passive"))
      (node (ref "U21") (pin "8") (pinfunction "A7_8") (pintype "bidirectional"))
      (node (ref "U3") (pin "15") (pinfunction "I/O6_15") (pintype "bidirectional"))
    )
    (net (code "171") (name "/P40") (class "Default")
      (node (ref "C61") (pin "50") (pinfunction "50_50") (pintype "passive"))
      (node (ref "U21") (pin "9") (pinfunction "A8_9") (pintype "bidirectional"))
      (node (ref "U3") (pin "16") (pinfunction "I/O7_16") (pintype "bidirectional"))
    )
    (net (code "172") (name "/P41") (class "Default")
      (node (ref "C61") (pin "51") (pinfunction "51_51") (pintype "passive"))
      (node (ref "U22") (pin "1") (pinfunction "A1_1") (pintype "bidirectional"))
      (node (ref "U3") (pin "29") (pinfunction "I/O8_29") (pintype "bidirectional"))
    )
    (net (code "173") (name "/P42") (class "Default")
      (node (ref "C61") (pin "52") (pinfunction "52_52") (pintype "passive"))
      (node (ref "U22") (pin "3") (pinfunction "A2_3") (pintype "bidirectional"))
      (node (ref "U3") (pin "30") (pinfunction "I/O9_30") (pintype "bidirectional"))
    )
    (net (code "174") (name "/P43") (class "Default")
      (node (ref "C61") (pin "53") (pinfunction "53_53") (pintype "passive"))
      (node (ref "U22") (pin "4") (pinfunction "A3_4") (pintype "bidirectional"))
      (node (ref "U3") (pin "31") (pinfunction "I/O10_31") (pintype "bidirectional"))
    )
    (net (code "175") (name "/P44") (class "Default")
      (node (ref "C61") (pin "54") (pinfunction "54_54") (pintype "passive"))
      (node (ref "U22") (pin "5") (pinfunction "A4_5") (pintype "bidirectional"))
      (node (ref "U3") (pin "32") (pinfunction "I/O11_32") (pintype "bidirectional"))
    )
    (net (code "176") (name "/P45") (class "Default")
      (node (ref "C61") (pin "55") (pinfunction "55_55") (pintype "passive"))
      (node (ref "U22") (pin "6") (pinfunction "A5_6") (pintype "bidirectional"))
      (node (ref "U3") (pin "35") (pinfunction "I/O12_35") (pintype "bidirectional"))
    )
    (net (code "177") (name "/P46") (class "Default")
      (node (ref "C61") (pin "56") (pinfunction "56_56") (pintype "passive"))
      (node (ref "U22") (pin "7") (pinfunction "A6_7") (pintype "bidirectional"))
      (node (ref "U3") (pin "36") (pinfunction "I/O13_36") (pintype "bidirectional"))
    )
    (net (code "178") (name "/P47") (class "Default")
      (node (ref "C61") (pin "57") (pinfunction "57_57") (pintype "passive"))
      (node (ref "U22") (pin "8") (pinfunction "A7_8") (pintype "bidirectional"))
      (node (ref "U3") (pin "37") (pinfunction "I/O14_37") (pintype "bidirectional"))
    )
    (net (code "179") (name "/P48") (class "Default")
      (node (ref "C61") (pin "58") (pinfunction "58_58") (pintype "passive"))
      (node (ref "U28") (pin "3") (pinfunction "RXD_3") (pintype "input"))
    )
    (net (code "180") (name "/P49") (class "Default")
      (node (ref "C61") (pin "59") (pinfunction "59_59") (pintype "passive"))
      (node (ref "U28") (pin "2") (pinfunction "TXD_2") (pintype "output"))
    )
    (net (code "181") (name "/P50") (class "Default")
      (node (ref "C61") (pin "60") (pinfunction "60_60") (pintype "passive+no_connect"))
    )
    (net (code "182") (name "/P51") (class "Default")
      (node (ref "C61") (pin "61") (pinfunction "61_61") (pintype "passive+no_connect"))
    )
    (net (code "183") (name "/P56") (class "Default")
      (node (ref "C61") (pin "66") (pinfunction "66_66") (pintype "passive+no_connect"))
    )
    (net (code "184") (name "/P57") (class "Default")
      (node (ref "C61") (pin "67") (pinfunction "67_67") (pintype "passive+no_connect"))
    )
    (net (code "185") (name "/P58") (class "Default")
      (node (ref "C61") (pin "68") (pinfunction "68_68") (pintype "passive+no_connect"))
    )
    (net (code "186") (name "/P59") (class "Default")
      (node (ref "C61") (pin "69") (pinfunction "69_69") (pintype "passive+no_connect"))
    )
    (net (code "187") (name "/P60") (class "Default")
      (node (ref "C61") (pin "70") (pinfunction "70_70") (pintype "passive+no_connect"))
    )
    (net (code "188") (name "/P61") (class "Default")
      (node (ref "C61") (pin "71") (pinfunction "71_71") (pintype "passive+no_connect"))
    )
    (net (code "189") (name "/P62") (class "Default")
      (node (ref "C61") (pin "72") (pinfunction "72_72") (pintype "passive+no_connect"))
    )
    (net (code "190") (name "/P63") (class "Default")
      (node (ref "C61") (pin "73") (pinfunction "73_73") (pintype "passive+no_connect"))
    )
    (net (code "191") (name "/P64") (class "Default")
      (node (ref "C61") (pin "74") (pinfunction "74_74") (pintype "passive+no_connect"))
    )
    (net (code "192") (name "/P65") (class "Default")
      (node (ref "C61") (pin "75") (pinfunction "75_75") (pintype "passive+no_connect"))
    )
    (net (code "193") (name "/P66") (class "Default")
      (node (ref "C61") (pin "76") (pinfunction "76_76") (pintype "passive+no_connect"))
    )
    (net (code "194") (name "/P67") (class "Default")
      (node (ref "C61") (pin "77") (pinfunction "77_77") (pintype "passive+no_connect"))
    )
    (net (code "195") (name "/P68") (class "Default")
      (node (ref "C61") (pin "78") (pinfunction "78_78") (pintype "passive+no_connect"))
    )
    (net (code "196") (name "/P69") (class "Default")
      (node (ref "C60") (pin "3") (pinfunction "3_3") (pintype "passive"))
      (node (ref "U16") (pin "1") (pinfunction "A1_1") (pintype "bidirectional"))
      (node (ref "U7") (pin "7") (pinfunction "I/O0_7") (pintype "bidirectional"))
    )
    (net (code "197") (name "/P70") (class "Default")
      (node (ref "C60") (pin "4") (pinfunction "4_4") (pintype "passive"))
      (node (ref "U16") (pin "3") (pinfunction "A2_3") (pintype "bidirectional"))
      (node (ref "U7") (pin "8") (pinfunction "I/O1_8") (pintype "bidirectional"))
    )
    (net (code "198") (name "/P71") (class "Default")
      (node (ref "C60") (pin "5") (pinfunction "5_5") (pintype "passive"))
      (node (ref "U16") (pin "4") (pinfunction "A3_4") (pintype "bidirectional"))
      (node (ref "U7") (pin "9") (pinfunction "I/O2_9") (pintype "bidirectional"))
    )
    (net (code "199") (name "/P72") (class "Default")
      (node (ref "C60") (pin "6") (pinfunction "6_6") (pintype "passive"))
      (node (ref "U16") (pin "5") (pinfunction "A4_5") (pintype "bidirectional"))
      (node (ref "U7") (pin "10") (pinfunction "I/O3_10") (pintype "bidirectional"))
    )
    (net (code "200") (name "/P73") (class "Default")
      (node (ref "C60") (pin "7") (pinfunction "7_7") (pintype "passive"))
      (node (ref "U16") (pin "6") (pinfunction "A5_6") (pintype "bidirectional"))
      (node (ref "U7") (pin "13") (pinfunction "I/O4_13") (pintype "bidirectional"))
    )
    (net (code "201") (name "/P74") (class "Default")
      (node (ref "C60") (pin "8") (pinfunction "8_8") (pintype "passive"))
      (node (ref "U16") (pin "7") (pinfunction "A6_7") (pintype "bidirectional"))
      (node (ref "U7") (pin "14") (pinfunction "I/O5_14") (pintype "bidirectional"))
    )
    (net (code "202") (name "/P75") (class "Default")
      (node (ref "C60") (pin "9") (pinfunction "9_9") (pintype "passive"))
      (node (ref "U16") (pin "8") (pinfunction "A7_8") (pintype "bidirectional"))
      (node (ref "U7") (pin "15") (pinfunction "I/O6_15") (pintype "bidirectional"))
    )
    (net (code "203") (name "/P76") (class "Default")
      (node (ref "C60") (pin "10") (pinfunction "10_10") (pintype "passive"))
      (node (ref "U16") (pin "9") (pinfunction "A8_9") (pintype "bidirectional"))
      (node (ref "U7") (pin "16") (pinfunction "I/O7_16") (pintype "bidirectional"))
    )
    (net (code "204") (name "/P77") (class "Default")
      (node (ref "C60") (pin "11") (pinfunction "11_11") (pintype "passive"))
      (node (ref "U17") (pin "1") (pinfunction "A1_1") (pintype "bidirectional"))
      (node (ref "U7") (pin "29") (pinfunction "I/O8_29") (pintype "bidirectional"))
    )
    (net (code "205") (name "/P78") (class "Default")
      (node (ref "C60") (pin "12") (pinfunction "12_12") (pintype "passive"))
      (node (ref "U17") (pin "3") (pinfunction "A2_3") (pintype "bidirectional"))
      (node (ref "U7") (pin "30") (pinfunction "I/O9_30") (pintype "bidirectional"))
    )
    (net (code "206") (name "/P79") (class "Default")
      (node (ref "C60") (pin "13") (pinfunction "13_13") (pintype "passive"))
      (node (ref "U17") (pin "4") (pinfunction "A3_4") (pintype "bidirectional"))
      (node (ref "U7") (pin "31") (pinfunction "I/O10_31") (pintype "bidirectional"))
    )
    (net (code "207") (name "/P80") (class "Default")
      (node (ref "C60") (pin "14") (pinfunction "14_14") (pintype "passive"))
      (node (ref "U17") (pin "5") (pinfunction "A4_5") (pintype "bidirectional"))
      (node (ref "U7") (pin "32") (pinfunction "I/O11_32") (pintype "bidirectional"))
    )
    (net (code "208") (name "/P81") (class "Default")
      (node (ref "C60") (pin "15") (pinfunction "15_15") (pintype "passive"))
      (node (ref "U17") (pin "6") (pinfunction "A5_6") (pintype "bidirectional"))
      (node (ref "U7") (pin "35") (pinfunction "I/O12_35") (pintype "bidirectional"))
    )
    (net (code "209") (name "/P82") (class "Default")
      (node (ref "C60") (pin "16") (pinfunction "16_16") (pintype "passive"))
      (node (ref "U17") (pin "7") (pinfunction "A6_7") (pintype "bidirectional"))
      (node (ref "U7") (pin "36") (pinfunction "I/O13_36") (pintype "bidirectional"))
    )
    (net (code "210") (name "/P83") (class "Default")
      (node (ref "C60") (pin "17") (pinfunction "17_17") (pintype "passive"))
      (node (ref "U17") (pin "8") (pinfunction "A7_8") (pintype "bidirectional"))
      (node (ref "U7") (pin "37") (pinfunction "I/O14_37") (pintype "bidirectional"))
    )
    (net (code "211") (name "/P84") (class "Default")
      (node (ref "C60") (pin "18") (pinfunction "18_18") (pintype "passive"))
      (node (ref "U17") (pin "9") (pinfunction "A8_9") (pintype "bidirectional"))
      (node (ref "U7") (pin "38") (pinfunction "I/O15_38") (pintype "bidirectional"))
    )
    (net (code "212") (name "/P85") (class "Default")
      (node (ref "C60") (pin "19") (pinfunction "19_19") (pintype "passive"))
      (node (ref "U18") (pin "1") (pinfunction "A1_1") (pintype "bidirectional"))
      (node (ref "U8") (pin "7") (pinfunction "I/O0_7") (pintype "bidirectional"))
    )
    (net (code "213") (name "/P86") (class "Default")
      (node (ref "C60") (pin "20") (pinfunction "20_20") (pintype "passive"))
      (node (ref "U18") (pin "3") (pinfunction "A2_3") (pintype "bidirectional"))
      (node (ref "U8") (pin "8") (pinfunction "I/O1_8") (pintype "bidirectional"))
    )
    (net (code "214") (name "/P87") (class "Default")
      (node (ref "C60") (pin "21") (pinfunction "21_21") (pintype "passive"))
      (node (ref "U18") (pin "4") (pinfunction "A3_4") (pintype "bidirectional"))
      (node (ref "U8") (pin "9") (pinfunction "I/O2_9") (pintype "bidirectional"))
    )
    (net (code "215") (name "/P88") (class "Default")
      (node (ref "C60") (pin "22") (pinfunction "22_22") (pintype "passive"))
      (node (ref "U18") (pin "5") (pinfunction "A4_5") (pintype "bidirectional"))
      (node (ref "U8") (pin "10") (pinfunction "I/O3_10") (pintype "bidirectional"))
    )
    (net (code "216") (name "/P89") (class "Default")
      (node (ref "C60") (pin "23") (pinfunction "23_23") (pintype "passive"))
      (node (ref "U18") (pin "6") (pinfunction "A5_6") (pintype "bidirectional"))
      (node (ref "U8") (pin "13") (pinfunction "I/O4_13") (pintype "bidirectional"))
    )
    (net (code "217") (name "/P90") (class "Default")
      (node (ref "C60") (pin "24") (pinfunction "24_24") (pintype "passive"))
      (node (ref "U18") (pin "7") (pinfunction "A6_7") (pintype "bidirectional"))
      (node (ref "U8") (pin "14") (pinfunction "I/O5_14") (pintype "bidirectional"))
    )
    (net (code "218") (name "/P91") (class "Default")
      (node (ref "C60") (pin "25") (pinfunction "25_25") (pintype "passive"))
      (node (ref "U18") (pin "8") (pinfunction "A7_8") (pintype "bidirectional"))
      (node (ref "U8") (pin "15") (pinfunction "I/O6_15") (pintype "bidirectional"))
    )
    (net (code "219") (name "/P92") (class "Default")
      (node (ref "C60") (pin "26") (pinfunction "26_26") (pintype "passive"))
      (node (ref "U18") (pin "9") (pinfunction "A8_9") (pintype "bidirectional"))
      (node (ref "U8") (pin "16") (pinfunction "I/O7_16") (pintype "bidirectional"))
    )
    (net (code "220") (name "/P93") (class "Default")
      (node (ref "C60") (pin "27") (pinfunction "27_27") (pintype "passive"))
      (node (ref "U19") (pin "1") (pinfunction "A1_1") (pintype "bidirectional"))
      (node (ref "U8") (pin "29") (pinfunction "I/O8_29") (pintype "bidirectional"))
    )
    (net (code "221") (name "/P94") (class "Default")
      (node (ref "C60") (pin "28") (pinfunction "28_28") (pintype "passive"))
      (node (ref "U19") (pin "3") (pinfunction "A2_3") (pintype "bidirectional"))
      (node (ref "U8") (pin "30") (pinfunction "I/O9_30") (pintype "bidirectional"))
    )
    (net (code "222") (name "/P95") (class "Default")
      (node (ref "C60") (pin "29") (pinfunction "29_29") (pintype "passive"))
      (node (ref "U19") (pin "4") (pinfunction "A3_4") (pintype "bidirectional"))
      (node (ref "U8") (pin "31") (pinfunction "I/O10_31") (pintype "bidirectional"))
    )
    (net (code "223") (name "/P96") (class "Default")
      (node (ref "C60") (pin "30") (pinfunction "30_30") (pintype "passive"))
      (node (ref "U19") (pin "5") (pinfunction "A4_5") (pintype "bidirectional"))
      (node (ref "U8") (pin "32") (pinfunction "I/O11_32") (pintype "bidirectional"))
    )
    (net (code "224") (name "/P97") (class "Default")
      (node (ref "C60") (pin "31") (pinfunction "31_31") (pintype "passive"))
      (node (ref "U19") (pin "6") (pinfunction "A5_6") (pintype "bidirectional"))
      (node (ref "U8") (pin "35") (pinfunction "I/O12_35") (pintype "bidirectional"))
    )
    (net (code "225") (name "/P98") (class "Default")
      (node (ref "C60") (pin "32") (pinfunction "32_32") (pintype "passive"))
      (node (ref "U19") (pin "7") (pinfunction "A6_7") (pintype "bidirectional"))
      (node (ref "U8") (pin "36") (pinfunction "I/O13_36") (pintype "bidirectional"))
    )
    (net (code "226") (name "/P99") (class "Default")
      (node (ref "C60") (pin "33") (pinfunction "33_33") (pintype "passive"))
      (node (ref "U19") (pin "8") (pinfunction "A7_8") (pintype "bidirectional"))
      (node (ref "U8") (pin "37") (pinfunction "I/O14_37") (pintype "bidirectional"))
    )
    (net (code "227") (name "/P100") (class "Default")
      (node (ref "C60") (pin "34") (pinfunction "34_34") (pintype "passive"))
      (node (ref "U19") (pin "9") (pinfunction "A8_9") (pintype "bidirectional"))
      (node (ref "U8") (pin "38") (pinfunction "I/O15_38") (pintype "bidirectional"))
    )
    (net (code "228") (name "/P101") (class "Default")
      (node (ref "C60") (pin "35") (pinfunction "35_35") (pintype "passive"))
      (node (ref "U23") (pin "1") (pinfunction "A1_1") (pintype "bidirectional"))
      (node (ref "U9") (pin "7") (pinfunction "I/O0_7") (pintype "bidirectional"))
    )
    (net (code "229") (name "/P102") (class "Default")
      (node (ref "C60") (pin "36") (pinfunction "36_36") (pintype "passive"))
      (node (ref "U23") (pin "3") (pinfunction "A2_3") (pintype "bidirectional"))
      (node (ref "U9") (pin "8") (pinfunction "I/O1_8") (pintype "bidirectional"))
    )
    (net (code "230") (name "/P103") (class "Default")
      (node (ref "C60") (pin "45") (pinfunction "45_45") (pintype "passive"))
      (node (ref "U23") (pin "4") (pinfunction "A3_4") (pintype "bidirectional"))
      (node (ref "U9") (pin "9") (pinfunction "I/O2_9") (pintype "bidirectional"))
    )
    (net (code "231") (name "/P104") (class "Default")
      (node (ref "C60") (pin "46") (pinfunction "46_46") (pintype "passive"))
      (node (ref "U23") (pin "5") (pinfunction "A4_5") (pintype "bidirectional"))
      (node (ref "U9") (pin "10") (pinfunction "I/O3_10") (pintype "bidirectional"))
    )
    (net (code "232") (name "/P105") (class "Default")
      (node (ref "C60") (pin "47") (pinfunction "47_47") (pintype "passive"))
      (node (ref "U23") (pin "6") (pinfunction "A5_6") (pintype "bidirectional"))
      (node (ref "U9") (pin "13") (pinfunction "I/O4_13") (pintype "bidirectional"))
    )
    (net (code "233") (name "/P106") (class "Default")
      (node (ref "C60") (pin "48") (pinfunction "48_48") (pintype "passive"))
      (node (ref "U23") (pin "7") (pinfunction "A6_7") (pintype "bidirectional"))
      (node (ref "U9") (pin "14") (pinfunction "I/O5_14") (pintype "bidirectional"))
    )
    (net (code "234") (name "/P107") (class "Default")
      (node (ref "C60") (pin "49") (pinfunction "49_49") (pintype "passive"))
      (node (ref "U23") (pin "8") (pinfunction "A7_8") (pintype "bidirectional"))
      (node (ref "U9") (pin "15") (pinfunction "I/O6_15") (pintype "bidirectional"))
    )
    (net (code "235") (name "/P108") (class "Default")
      (node (ref "C60") (pin "50") (pinfunction "50_50") (pintype "passive"))
      (node (ref "U23") (pin "9") (pinfunction "A8_9") (pintype "bidirectional"))
      (node (ref "U9") (pin "16") (pinfunction "I/O7_16") (pintype "bidirectional"))
    )
    (net (code "236") (name "/P109") (class "Default")
      (node (ref "C60") (pin "51") (pinfunction "51_51") (pintype "passive"))
      (node (ref "U24") (pin "1") (pinfunction "A1_1") (pintype "bidirectional"))
      (node (ref "U9") (pin "29") (pinfunction "I/O8_29") (pintype "bidirectional"))
    )
    (net (code "237") (name "/P110") (class "Default")
      (node (ref "C60") (pin "52") (pinfunction "52_52") (pintype "passive"))
      (node (ref "U24") (pin "3") (pinfunction "A2_3") (pintype "bidirectional"))
      (node (ref "U9") (pin "30") (pinfunction "I/O9_30") (pintype "bidirectional"))
    )
    (net (code "238") (name "/P111") (class "Default")
      (node (ref "C60") (pin "53") (pinfunction "53_53") (pintype "passive"))
      (node (ref "U24") (pin "4") (pinfunction "A3_4") (pintype "bidirectional"))
      (node (ref "U9") (pin "31") (pinfunction "I/O10_31") (pintype "bidirectional"))
    )
    (net (code "239") (name "/P112") (class "Default")
      (node (ref "C60") (pin "54") (pinfunction "54_54") (pintype "passive"))
      (node (ref "U24") (pin "5") (pinfunction "A4_5") (pintype "bidirectional"))
      (node (ref "U9") (pin "32") (pinfunction "I/O11_32") (pintype "bidirectional"))
    )
    (net (code "240") (name "/P113") (class "Default")
      (node (ref "C60") (pin "55") (pinfunction "55_55") (pintype "passive"))
      (node (ref "U24") (pin "6") (pinfunction "A5_6") (pintype "bidirectional"))
      (node (ref "U9") (pin "35") (pinfunction "I/O12_35") (pintype "bidirectional"))
    )
    (net (code "241") (name "/P114") (class "Default")
      (node (ref "C60") (pin "56") (pinfunction "56_56") (pintype "passive"))
      (node (ref "U24") (pin "7") (pinfunction "A6_7") (pintype "bidirectional"))
      (node (ref "U9") (pin "36") (pinfunction "I/O13_36") (pintype "bidirectional"))
    )
    (net (code "242") (name "/P115") (class "Default")
      (node (ref "C60") (pin "57") (pinfunction "57_57") (pintype "passive"))
      (node (ref "U24") (pin "8") (pinfunction "A7_8") (pintype "bidirectional"))
      (node (ref "U9") (pin "37") (pinfunction "I/O14_37") (pintype "bidirectional"))
    )
    (net (code "243") (name "/P116") (class "Default")
      (node (ref "C60") (pin "58") (pinfunction "58_58") (pintype "passive"))
      (node (ref "U24") (pin "9") (pinfunction "A8_9") (pintype "bidirectional"))
      (node (ref "U9") (pin "38") (pinfunction "I/O15_38") (pintype "bidirectional"))
    )
    (net (code "244") (name "/P117") (class "Default")
      (node (ref "C60") (pin "59") (pinfunction "59_59") (pintype "passive"))
      (node (ref "U10") (pin "7") (pinfunction "I/O0_7") (pintype "bidirectional"))
      (node (ref "U25") (pin "1") (pinfunction "A1_1") (pintype "bidirectional"))
    )
    (net (code "245") (name "/P118") (class "Default")
      (node (ref "C60") (pin "60") (pinfunction "60_60") (pintype "passive"))
      (node (ref "U10") (pin "8") (pinfunction "I/O1_8") (pintype "bidirectional"))
      (node (ref "U25") (pin "3") (pinfunction "A2_3") (pintype "bidirectional"))
    )
    (net (code "246") (name "/P119") (class "Default")
      (node (ref "C60") (pin "61") (pinfunction "61_61") (pintype "passive"))
      (node (ref "U10") (pin "9") (pinfunction "I/O2_9") (pintype "bidirectional"))
      (node (ref "U25") (pin "4") (pinfunction "A3_4") (pintype "bidirectional"))
    )
    (net (code "247") (name "/P120") (class "Default")
      (node (ref "C60") (pin "62") (pinfunction "62_62") (pintype "passive"))
      (node (ref "U10") (pin "10") (pinfunction "I/O3_10") (pintype "bidirectional"))
      (node (ref "U25") (pin "5") (pinfunction "A4_5") (pintype "bidirectional"))
    )
    (net (code "248") (name "/P121") (class "Default")
      (node (ref "C60") (pin "63") (pinfunction "63_63") (pintype "passive"))
      (node (ref "U10") (pin "13") (pinfunction "I/O4_13") (pintype "bidirectional"))
      (node (ref "U25") (pin "6") (pinfunction "A5_6") (pintype "bidirectional"))
    )
    (net (code "249") (name "/P122") (class "Default")
      (node (ref "C60") (pin "64") (pinfunction "64_64") (pintype "passive"))
      (node (ref "U10") (pin "14") (pinfunction "I/O5_14") (pintype "bidirectional"))
      (node (ref "U25") (pin "7") (pinfunction "A6_7") (pintype "bidirectional"))
    )
    (net (code "250") (name "/P123") (class "Default")
      (node (ref "C60") (pin "65") (pinfunction "65_65") (pintype "passive"))
      (node (ref "U10") (pin "15") (pinfunction "I/O6_15") (pintype "bidirectional"))
      (node (ref "U25") (pin "8") (pinfunction "A7_8") (pintype "bidirectional"))
    )
    (net (code "251") (name "/P124") (class "Default")
      (node (ref "C60") (pin "66") (pinfunction "66_66") (pintype "passive"))
      (node (ref "U10") (pin "16") (pinfunction "I/O7_16") (pintype "bidirectional"))
      (node (ref "U25") (pin "9") (pinfunction "A8_9") (pintype "bidirectional"))
    )
    (net (code "252") (name "/P125") (class "Default")
      (node (ref "C60") (pin "67") (pinfunction "67_67") (pintype "passive"))
      (node (ref "U10") (pin "29") (pinfunction "I/O8_29") (pintype "bidirectional"))
      (node (ref "U26") (pin "1") (pinfunction "A1_1") (pintype "bidirectional"))
    )
    (net (code "253") (name "/P126") (class "Default")
      (node (ref "C60") (pin "68") (pinfunction "68_68") (pintype "passive"))
      (node (ref "U10") (pin "30") (pinfunction "I/O9_30") (pintype "bidirectional"))
      (node (ref "U26") (pin "3") (pinfunction "A2_3") (pintype "bidirectional"))
    )
    (net (code "254") (name "/P133") (class "Default")
      (node (ref "C60") (pin "75") (pinfunction "75_75") (pintype "passive+no_connect"))
    )
    (net (code "255") (name "/P134") (class "Default")
      (node (ref "C60") (pin "76") (pinfunction "76_76") (pintype "passive+no_connect"))
    )
    (net (code "256") (name "/P135") (class "Default")
      (node (ref "C60") (pin "77") (pinfunction "77_77") (pintype "passive+no_connect"))
    )
    (net (code "257") (name "/P136") (class "Default")
      (node (ref "C60") (pin "78") (pinfunction "78_78") (pintype "passive+no_connect"))
    )
    (net (code "258") (name "/VCCB") (class "Default")
      (node (ref "C63") (pin "2") (pinfunction "2_2") (pintype "passive"))
      (node (ref "C65") (pin "2") (pinfunction "2_2") (pintype "passive"))
      (node (ref "C67") (pin "2") (pinfunction "2_2") (pintype "passive"))
      (node (ref "C69") (pin "2") (pinfunction "2_2") (pintype "passive"))
      (node (ref "C71") (pin "2") (pinfunction "2_2") (pintype "passive"))
      (node (ref "C73") (pin "2") (pinfunction "2_2") (pintype "passive"))
      (node (ref "C75") (pin "2") (pinfunction "2_2") (pintype "passive"))
      (node (ref "C84") (pin "2") (pinfunction "2_2") (pintype "passive"))
      (node (ref "C86") (pin "2") (pinfunction "2_2") (pintype "passive"))
      (node (ref "C88") (pin "2") (pinfunction "2_2") (pintype "passive"))
      (node (ref "C90") (pin "2") (pinfunction "2_2") (pintype "passive"))
      (node (ref "C92") (pin "2") (pinfunction "2_2") (pintype "passive"))
      (node (ref "C94") (pin "2") (pinfunction "2_2") (pintype "passive"))
      (node (ref "C96") (pin "2") (pinfunction "2_2") (pintype "passive"))
      (node (ref "SW2") (pin "6") (pinfunction "6_6") (pintype "passive"))
      (node (ref "U13") (pin "19") (pinfunction "VCCB_19") (pintype "power_in"))
      (node (ref "U14") (pin "19") (pinfunction "VCCB_19") (pintype "power_in"))
      (node (ref "U15") (pin "19") (pinfunction "VCCB_19") (pintype "power_in"))
      (node (ref "U16") (pin "19") (pinfunction "VCCB_19") (pintype "power_in"))
      (node (ref "U17") (pin "19") (pinfunction "VCCB_19") (pintype "power_in"))
      (node (ref "U18") (pin "19") (pinfunction "VCCB_19") (pintype "power_in"))
      (node (ref "U19") (pin "19") (pinfunction "VCCB_19") (pintype "power_in"))
      (node (ref "U20") (pin "19") (pinfunction "VCCB_19") (pintype "power_in"))
      (node (ref "U21") (pin "19") (pinfunction "VCCB_19") (pintype "power_in"))
      (node (ref "U22") (pin "19") (pinfunction "VCCB_19") (pintype "power_in"))
      (node (ref "U23") (pin "19") (pinfunction "VCCB_19") (pintype "power_in"))
      (node (ref "U24") (pin "19") (pinfunction "VCCB_19") (pintype "power_in"))
      (node (ref "U25") (pin "19") (pinfunction "VCCB_19") (pintype "power_in"))
      (node (ref "U26") (pin "19") (pinfunction "VCCB_19") (pintype "power_in"))
    )
    (net (code "259") (name "1.2V") (class "Default")
      (node (ref "C45") (pin "1") (pinfunction "1_1") (pintype "passive"))
      (node (ref "C47") (pin "2") (pinfunction "2_2") (pintype "passive"))
      (node (ref "C48") (pin "2") (pinfunction "2_2") (pintype "passive"))
      (node (ref "C49") (pin "2") (pinfunction "2_2") (pintype "passive"))
      (node (ref "C50") (pin "2") (pinfunction "2_2") (pintype "passive"))
      (node (ref "C51") (pin "2") (pinfunction "2_2") (pintype "passive"))
      (node (ref "C52") (pin "2") (pinfunction "2_2") (pintype "passive"))
      (node (ref "C61") (pin "37") (pinfunction "37_37") (pintype "passive"))
      (node (ref "C61") (pin "44") (pinfunction "44_44") (pintype "passive"))
      (node (ref "U12") (pin "2") (pinfunction "OUT_2") (pintype "passive"))
    )
    (net (code "260") (name "1.8V") (class "Default")
      (node (ref "C32") (pin "1") (pinfunction "1_1") (pintype "passive"))
      (node (ref "C34") (pin "2") (pinfunction "2_2") (pintype "passive"))
      (node (ref "C39") (pin "2") (pinfunction "2_2") (pintype "passive"))
      (node (ref "C40") (pin "2") (pinfunction "2_2") (pintype "passive"))
      (node (ref "C41") (pin "2") (pinfunction "2_2") (pintype "passive"))
      (node (ref "C42") (pin "2") (pinfunction "2_2") (pintype "passive"))
      (node (ref "C43") (pin "2") (pinfunction "2_2") (pintype "passive"))
      (node (ref "C61") (pin "38") (pinfunction "38_38") (pintype "passive"))
      (node (ref "C61") (pin "43") (pinfunction "43_43") (pintype "passive"))
      (node (ref "U11") (pin "2") (pinfunction "OUT_2") (pintype "passive"))
    )
    (net (code "261") (name "2.5V") (class "Default")
      (node (ref "C23") (pin "1") (pinfunction "1_1") (pintype "passive"))
      (node (ref "C25") (pin "2") (pinfunction "2_2") (pintype "passive"))
      (node (ref "C26") (pin "2") (pinfunction "2_2") (pintype "passive"))
      (node (ref "C27") (pin "2") (pinfunction "2_2") (pintype "passive"))
      (node (ref "C28") (pin "2") (pinfunction "2_2") (pintype "passive"))
      (node (ref "C29") (pin "2") (pinfunction "2_2") (pintype "passive"))
      (node (ref "C30") (pin "2") (pinfunction "2_2") (pintype "passive"))
      (node (ref "C61") (pin "39") (pinfunction "39_39") (pintype "passive"))
      (node (ref "C61") (pin "42") (pinfunction "42_42") (pintype "passive"))
      (node (ref "U6") (pin "2") (pinfunction "OUT_2") (pintype "passive"))
    )
    (net (code "262") (name "3.3V") (class "Default")
      (node (ref "C14") (pin "1") (pinfunction "1_1") (pintype "passive"))
      (node (ref "C16") (pin "2") (pinfunction "2_2") (pintype "passive"))
      (node (ref "C17") (pin "2") (pinfunction "2_2") (pintype "passive"))
      (node (ref "C18") (pin "2") (pinfunction "2_2") (pintype "passive"))
      (node (ref "C19") (pin "2") (pinfunction "2_2") (pintype "passive"))
      (node (ref "C20") (pin "2") (pinfunction "2_2") (pintype "passive"))
      (node (ref "C21") (pin "2") (pinfunction "2_2") (pintype "passive"))
      (node (ref "C53") (pin "1") (pinfunction "1_1") (pintype "passive"))
      (node (ref "C54") (pin "1") (pinfunction "1_1") (pintype "passive"))
      (node (ref "C55") (pin "1") (pinfunction "1_1") (pintype "passive"))
      (node (ref "C56") (pin "1") (pinfunction "1_1") (pintype "passive"))
      (node (ref "C57") (pin "1") (pinfunction "1_1") (pintype "passive"))
      (node (ref "C58") (pin "1") (pinfunction "1_1") (pintype "passive"))
      (node (ref "C59") (pin "1") (pinfunction "1_1") (pintype "passive"))
      (node (ref "C61") (pin "40") (pinfunction "40_40") (pintype "passive"))
      (node (ref "C61") (pin "41") (pinfunction "41_41") (pintype "passive"))
      (node (ref "C76") (pin "1") (pinfunction "1_1") (pintype "passive"))
      (node (ref "C77") (pin "1") (pinfunction "1_1") (pintype "passive"))
      (node (ref "C78") (pin "1") (pinfunction "1_1") (pintype "passive"))
      (node (ref "C79") (pin "1") (pinfunction "1_1") (pintype "passive"))
      (node (ref "C80") (pin "1") (pinfunction "1_1") (pintype "passive"))
      (node (ref "C81") (pin "1") (pinfunction "1_1") (pintype "passive"))
      (node (ref "C82") (pin "1") (pinfunction "1_1") (pintype "passive"))
      (node (ref "C98") (pin "1") (pinfunction "1_1") (pintype "passive"))
      (node (ref "R10") (pin "1") (pinfunction "1_1") (pintype "passive"))
      (node (ref "R11") (pin "1") (pinfunction "1_1") (pintype "passive"))
      (node (ref "R22") (pin "1") (pinfunction "1_1") (pintype "passive"))
      (node (ref "SW2") (pin "5") (pinfunction "5_5") (pintype "passive"))
      (node (ref "U13") (pin "2") (pinfunction "VCCA_2") (pintype "power_in"))
      (node (ref "U14") (pin "2") (pinfunction "VCCA_2") (pintype "power_in"))
      (node (ref "U15") (pin "2") (pinfunction "VCCA_2") (pintype "power_in"))
      (node (ref "U16") (pin "2") (pinfunction "VCCA_2") (pintype "power_in"))
      (node (ref "U17") (pin "2") (pinfunction "VCCA_2") (pintype "power_in"))
      (node (ref "U18") (pin "2") (pinfunction "VCCA_2") (pintype "power_in"))
      (node (ref "U19") (pin "2") (pinfunction "VCCA_2") (pintype "power_in"))
      (node (ref "U20") (pin "2") (pinfunction "VCCA_2") (pintype "power_in"))
      (node (ref "U21") (pin "2") (pinfunction "VCCA_2") (pintype "power_in"))
      (node (ref "U22") (pin "2") (pinfunction "VCCA_2") (pintype "power_in"))
      (node (ref "U23") (pin "2") (pinfunction "VCCA_2") (pintype "power_in"))
      (node (ref "U24") (pin "2") (pinfunction "VCCA_2") (pintype "power_in"))
      (node (ref "U25") (pin "2") (pinfunction "VCCA_2") (pintype "power_in"))
      (node (ref "U26") (pin "2") (pinfunction "VCCA_2") (pintype "power_in"))
      (node (ref "U28") (pin "16") (pinfunction "VCC_16") (pintype "power_in"))
      (node (ref "U28") (pin "4") (pinfunction "V3_4") (pintype "power_in"))
      (node (ref "U5") (pin "2") (pinfunction "OUT_2") (pintype "passive"))
    )
    (net (code "263") (name "5V") (class "Default")
      (node (ref "C1") (pin "2") (pinfunction "2_2") (pintype "passive"))
      (node (ref "C10") (pin "2") (pinfunction "2_2") (pintype "passive"))
      (node (ref "C11") (pin "2") (pinfunction "2_2") (pintype "passive"))
      (node (ref "C12") (pin "2") (pinfunction "2_2") (pintype "passive"))
      (node (ref "C2") (pin "2") (pinfunction "2_2") (pintype "passive"))
      (node (ref "C3") (pin "2") (pinfunction "2_2") (pintype "passive"))
      (node (ref "C35") (pin "2") (pinfunction "2_2") (pintype "passive"))
      (node (ref "C36") (pin "2") (pinfunction "2_2") (pintype "passive"))
      (node (ref "C37") (pin "2") (pinfunction "2_2") (pintype "passive"))
      (node (ref "C38") (pin "2") (pinfunction "2_2") (pintype "passive"))
      (node (ref "C5") (pin "1") (pinfunction "1_1") (pintype "passive"))
      (node (ref "C7") (pin "2") (pinfunction "2_2") (pintype "passive"))
      (node (ref "C8") (pin "2") (pinfunction "2_2") (pintype "passive"))
      (node (ref "C9") (pin "2") (pinfunction "2_2") (pintype "passive"))
      (node (ref "C97") (pin "2") (pinfunction "2_2") (pintype "passive"))
      (node (ref "SW2") (pin "8") (pinfunction "8_8") (pintype "passive"))
      (node (ref "U1") (pin "33") (pinfunction "VCC_33") (pintype "power_in"))
      (node (ref "U10") (pin "33") (pinfunction "VCC_33") (pintype "power_in"))
      (node (ref "U2") (pin "33") (pinfunction "VCC_33") (pintype "power_in"))
      (node (ref "U27") (pin "16") (pinfunction "VDD_16") (pintype "power_in"))
      (node (ref "U3") (pin "33") (pinfunction "VCC_33") (pintype "power_in"))
      (node (ref "U4") (pin "2") (pinfunction "OUT_2") (pintype "passive"))
      (node (ref "U7") (pin "33") (pinfunction "VCC_33") (pintype "power_in"))
      (node (ref "U8") (pin "33") (pinfunction "VCC_33") (pintype "power_in"))
      (node (ref "U9") (pin "33") (pinfunction "VCC_33") (pintype "power_in"))
      (node (ref "X1") (pin "49") (pinfunction "B4_49") (pintype "passive"))
      (node (ref "X1") (pin "55") (pinfunction "B10_55") (pintype "passive"))
      (node (ref "X1") (pin "63") (pinfunction "B18_63") (pintype "passive"))
      (node (ref "X1") (pin "73") (pinfunction "B28_73") (pintype "passive"))
      (node (ref "X1") (pin "81") (pinfunction "B36_81") (pintype "passive"))
      (node (ref "X1") (pin "87") (pinfunction "B42_87") (pintype "passive"))
    )
    (net (code "264") (name "5V-IN") (class "Default")
      (node (ref "C13") (pin "1") (pinfunction "1_1") (pintype "passive"))
      (node (ref "C15") (pin "2") (pinfunction "2_2") (pintype "passive"))
      (node (ref "C22") (pin "1") (pinfunction "1_1") (pintype "passive"))
      (node (ref "C24") (pin "2") (pinfunction "2_2") (pintype "passive"))
      (node (ref "C31") (pin "1") (pinfunction "1_1") (pintype "passive"))
      (node (ref "C33") (pin "2") (pinfunction "2_2") (pintype "passive"))
      (node (ref "C4") (pin "1") (pinfunction "1_1") (pintype "passive"))
      (node (ref "C44") (pin "1") (pinfunction "1_1") (pintype "passive"))
      (node (ref "C46") (pin "2") (pinfunction "2_2") (pintype "passive"))
      (node (ref "C6") (pin "2") (pinfunction "2_2") (pintype "passive"))
      (node (ref "SW1") (pin "4") (pinfunction "4_4") (pintype "passive"))
      (node (ref "U11") (pin "3") (pinfunction "IN_3") (pintype "passive"))
      (node (ref "U12") (pin "3") (pinfunction "IN_3") (pintype "passive"))
      (node (ref "U4") (pin "3") (pinfunction "IN_3") (pintype "passive"))
      (node (ref "U5") (pin "3") (pinfunction "IN_3") (pintype "passive"))
      (node (ref "U6") (pin "3") (pinfunction "IN_3") (pintype "passive"))
    )
    (net (code "265") (name "GND") (class "Default")
      (node (ref "C1") (pin "1") (pinfunction "1_1") (pintype "passive"))
      (node (ref "C10") (pin "1") (pinfunction "1_1") (pintype "passive"))
      (node (ref "C11") (pin "1") (pinfunction "1_1") (pintype "passive"))
      (node (ref "C12") (pin "1") (pinfunction "1_1") (pintype "passive"))
      (node (ref "C13") (pin "2") (pinfunction "2_2") (pintype "passive"))
      (node (ref "C14") (pin "2") (pinfunction "2_2") (pintype "passive"))
      (node (ref "C15") (pin "1") (pinfunction "1_1") (pintype "passive"))
      (node (ref "C16") (pin "1") (pinfunction "1_1") (pintype "passive"))
      (node (ref "C17") (pin "1") (pinfunction "1_1") (pintype "passive"))
      (node (ref "C18") (pin "1") (pinfunction "1_1") (pintype "passive"))
      (node (ref "C19") (pin "1") (pinfunction "1_1") (pintype "passive"))
      (node (ref "C2") (pin "1") (pinfunction "1_1") (pintype "passive"))
      (node (ref "C20") (pin "1") (pinfunction "1_1") (pintype "passive"))
      (node (ref "C21") (pin "1") (pinfunction "1_1") (pintype "passive"))
      (node (ref "C22") (pin "2") (pinfunction "2_2") (pintype "passive"))
      (node (ref "C23") (pin "2") (pinfunction "2_2") (pintype "passive"))
      (node (ref "C24") (pin "1") (pinfunction "1_1") (pintype "passive"))
      (node (ref "C25") (pin "1") (pinfunction "1_1") (pintype "passive"))
      (node (ref "C26") (pin "1") (pinfunction "1_1") (pintype "passive"))
      (node (ref "C27") (pin "1") (pinfunction "1_1") (pintype "passive"))
      (node (ref "C28") (pin "1") (pinfunction "1_1") (pintype "passive"))
      (node (ref "C29") (pin "1") (pinfunction "1_1") (pintype "passive"))
      (node (ref "C3") (pin "1") (pinfunction "1_1") (pintype "passive"))
      (node (ref "C30") (pin "1") (pinfunction "1_1") (pintype "passive"))
      (node (ref "C31") (pin "2") (pinfunction "2_2") (pintype "passive"))
      (node (ref "C32") (pin "2") (pinfunction "2_2") (pintype "passive"))
      (node (ref "C33") (pin "1") (pinfunction "1_1") (pintype "passive"))
      (node (ref "C34") (pin "1") (pinfunction "1_1") (pintype "passive"))
      (node (ref "C35") (pin "1") (pinfunction "1_1") (pintype "passive"))
      (node (ref "C36") (pin "1") (pinfunction "1_1") (pintype "passive"))
      (node (ref "C37") (pin "1") (pinfunction "1_1") (pintype "passive"))
      (node (ref "C38") (pin "1") (pinfunction "1_1") (pintype "passive"))
      (node (ref "C39") (pin "1") (pinfunction "1_1") (pintype "passive"))
      (node (ref "C4") (pin "2") (pinfunction "2_2") (pintype "passive"))
      (node (ref "C40") (pin "1") (pinfunction "1_1") (pintype "passive"))
      (node (ref "C41") (pin "1") (pinfunction "1_1") (pintype "passive"))
      (node (ref "C42") (pin "1") (pinfunction "1_1") (pintype "passive"))
      (node (ref "C43") (pin "1") (pinfunction "1_1") (pintype "passive"))
      (node (ref "C44") (pin "2") (pinfunction "2_2") (pintype "passive"))
      (node (ref "C45") (pin "2") (pinfunction "2_2") (pintype "passive"))
      (node (ref "C46") (pin "1") (pinfunction "1_1") (pintype "passive"))
      (node (ref "C47") (pin "1") (pinfunction "1_1") (pintype "passive"))
      (node (ref "C48") (pin "1") (pinfunction "1_1") (pintype "passive"))
      (node (ref "C49") (pin "1") (pinfunction "1_1") (pintype "passive"))
      (node (ref "C5") (pin "2") (pinfunction "2_2") (pintype "passive"))
      (node (ref "C50") (pin "1") (pinfunction "1_1") (pintype "passive"))
      (node (ref "C51") (pin "1") (pinfunction "1_1") (pintype "passive"))
      (node (ref "C52") (pin "1") (pinfunction "1_1") (pintype "passive"))
      (node (ref "C53") (pin "2") (pinfunction "2_2") (pintype "passive"))
      (node (ref "C54") (pin "2") (pinfunction "2_2") (pintype "passive"))
      (node (ref "C55") (pin "2") (pinfunction "2_2") (pintype "passive"))
      (node (ref "C56") (pin "2") (pinfunction "2_2") (pintype "passive"))
      (node (ref "C57") (pin "2") (pinfunction "2_2") (pintype "passive"))
      (node (ref "C58") (pin "2") (pinfunction "2_2") (pintype "passive"))
      (node (ref "C59") (pin "2") (pinfunction "2_2") (pintype "passive"))
      (node (ref "C6") (pin "1") (pinfunction "1_1") (pintype "passive"))
      (node (ref "C60") (pin "37") (pinfunction "37_37") (pintype "passive"))
      (node (ref "C60") (pin "38") (pinfunction "38_38") (pintype "passive"))
      (node (ref "C60") (pin "39") (pinfunction "39_39") (pintype "passive"))
      (node (ref "C60") (pin "40") (pinfunction "40_40") (pintype "passive"))
      (node (ref "C60") (pin "41") (pinfunction "41_41") (pintype "passive"))
      (node (ref "C60") (pin "42") (pinfunction "42_42") (pintype "passive"))
      (node (ref "C60") (pin "43") (pinfunction "43_43") (pintype "passive"))
      (node (ref "C60") (pin "44") (pinfunction "44_44") (pintype "passive"))
      (node (ref "C61") (pin "1") (pinfunction "1_1") (pintype "passive"))
      (node (ref "C61") (pin "2") (pinfunction "2_2") (pintype "passive"))
      (node (ref "C61") (pin "79") (pinfunction "79_79") (pintype "passive"))
      (node (ref "C61") (pin "80") (pinfunction "80_80") (pintype "passive"))
      (node (ref "C62") (pin "1") (pinfunction "1_1") (pintype "passive"))
      (node (ref "C63") (pin "1") (pinfunction "1_1") (pintype "passive"))
      (node (ref "C64") (pin "1") (pinfunction "1_1") (pintype "passive"))
      (node (ref "C65") (pin "1") (pinfunction "1_1") (pintype "passive"))
      (node (ref "C66") (pin "1") (pinfunction "1_1") (pintype "passive"))
      (node (ref "C67") (pin "1") (pinfunction "1_1") (pintype "passive"))
      (node (ref "C68") (pin "1") (pinfunction "1_1") (pintype "passive"))
      (node (ref "C69") (pin "1") (pinfunction "1_1") (pintype "passive"))
      (node (ref "C7") (pin "1") (pinfunction "1_1") (pintype "passive"))
      (node (ref "C70") (pin "1") (pinfunction "1_1") (pintype "passive"))
      (node (ref "C71") (pin "1") (pinfunction "1_1") (pintype "passive"))
      (node (ref "C72") (pin "1") (pinfunction "1_1") (pintype "passive"))
      (node (ref "C73") (pin "1") (pinfunction "1_1") (pintype "passive"))
      (node (ref "C74") (pin "1") (pinfunction "1_1") (pintype "passive"))
      (node (ref "C75") (pin "1") (pinfunction "1_1") (pintype "passive"))
      (node (ref "C76") (pin "2") (pinfunction "2_2") (pintype "passive"))
      (node (ref "C77") (pin "2") (pinfunction "2_2") (pintype "passive"))
      (node (ref "C78") (pin "2") (pinfunction "2_2") (pintype "passive"))
      (node (ref "C79") (pin "2") (pinfunction "2_2") (pintype "passive"))
      (node (ref "C8") (pin "1") (pinfunction "1_1") (pintype "passive"))
      (node (ref "C80") (pin "2") (pinfunction "2_2") (pintype "passive"))
      (node (ref "C81") (pin "2") (pinfunction "2_2") (pintype "passive"))
      (node (ref "C82") (pin "2") (pinfunction "2_2") (pintype "passive"))
      (node (ref "C83") (pin "1") (pinfunction "1_1") (pintype "passive"))
      (node (ref "C84") (pin "1") (pinfunction "1_1") (pintype "passive"))
      (node (ref "C85") (pin "1") (pinfunction "1_1") (pintype "passive"))
      (node (ref "C86") (pin "1") (pinfunction "1_1") (pintype "passive"))
      (node (ref "C87") (pin "1") (pinfunction "1_1") (pintype "passive"))
      (node (ref "C88") (pin "1") (pinfunction "1_1") (pintype "passive"))
      (node (ref "C89") (pin "1") (pinfunction "1_1") (pintype "passive"))
      (node (ref "C9") (pin "1") (pinfunction "1_1") (pintype "passive"))
      (node (ref "C90") (pin "1") (pinfunction "1_1") (pintype "passive"))
      (node (ref "C91") (pin "1") (pinfunction "1_1") (pintype "passive"))
      (node (ref "C92") (pin "1") (pinfunction "1_1") (pintype "passive"))
      (node (ref "C93") (pin "1") (pinfunction "1_1") (pintype "passive"))
      (node (ref "C94") (pin "1") (pinfunction "1_1") (pintype "passive"))
      (node (ref "C95") (pin "1") (pinfunction "1_1") (pintype "passive"))
      (node (ref "C96") (pin "1") (pinfunction "1_1") (pintype "passive"))
      (node (ref "C97") (pin "1") (pinfunction "1_1") (pintype "passive"))
      (node (ref "C98") (pin "2") (pinfunction "2_2") (pintype "passive"))
      (node (ref "CMOS1") (pin "2") (pinfunction "K_2") (pintype "passive"))
      (node (ref "OFF1") (pin "2") (pinfunction "K_2") (pintype "passive"))
      (node (ref "R1") (pin "2") (pinfunction "2_2") (pintype "passive"))
      (node (ref "R12") (pin "2") (pinfunction "2_2") (pintype "passive"))
      (node (ref "R13") (pin "2") (pinfunction "2_2") (pintype "passive"))
      (node (ref "R14") (pin "2") (pinfunction "2_2") (pintype "passive"))
      (node (ref "R15") (pin "2") (pinfunction "2_2") (pintype "passive"))
      (node (ref "R16") (pin "2") (pinfunction "2_2") (pintype "passive"))
      (node (ref "R17") (pin "2") (pinfunction "2_2") (pintype "passive"))
      (node (ref "R18") (pin "2") (pinfunction "2_2") (pintype "passive"))
      (node (ref "R19") (pin "1") (pinfunction "1_1") (pintype "passive"))
      (node (ref "R2") (pin "2") (pinfunction "2_2") (pintype "passive"))
      (node (ref "R20") (pin "1") (pinfunction "1_1") (pintype "passive"))
      (node (ref "R21") (pin "1") (pinfunction "1_1") (pintype "passive"))
      (node (ref "R23") (pin "1") (pinfunction "1_1") (pintype "passive"))
      (node (ref "R3") (pin "2") (pinfunction "2_2") (pintype "passive"))
      (node (ref "R4") (pin "2") (pinfunction "2_2") (pintype "passive"))
      (node (ref "R5") (pin "2") (pinfunction "2_2") (pintype "passive"))
      (node (ref "R6") (pin "2") (pinfunction "2_2") (pintype "passive"))
      (node (ref "R7") (pin "2") (pinfunction "2_2") (pintype "passive"))
      (node (ref "R8") (pin "2") (pinfunction "2_2") (pintype "passive"))
      (node (ref "R9") (pin "2") (pinfunction "2_2") (pintype "passive"))
      (node (ref "SW1") (pin "1") (pinfunction "1_1") (pintype "passive"))
      (node (ref "SW2") (pin "7") (pinfunction "7_7") (pintype "passive"))
      (node (ref "TTL1") (pin "2") (pinfunction "K_2") (pintype "passive"))
      (node (ref "U1") (pin "34") (pinfunction "GND_34") (pintype "power_in"))
      (node (ref "U1") (pin "39") (pinfunction "*LB_39") (pintype "passive"))
      (node (ref "U1") (pin "40") (pinfunction "*UB_40") (pintype "passive"))
      (node (ref "U10") (pin "34") (pinfunction "GND_34") (pintype "power_in"))
      (node (ref "U10") (pin "39") (pinfunction "*LB_39") (pintype "passive"))
      (node (ref "U10") (pin "40") (pinfunction "*UB_40") (pintype "passive"))
      (node (ref "U11") (pin "1") (pinfunction "GND_1") (pintype "passive"))
      (node (ref "U12") (pin "1") (pinfunction "GND_1") (pintype "passive"))
      (node (ref "U13") (pin "11") (pinfunction "GND_11") (pintype "power_in"))
      (node (ref "U14") (pin "11") (pinfunction "GND_11") (pintype "power_in"))
      (node (ref "U15") (pin "11") (pinfunction "GND_11") (pintype "power_in"))
      (node (ref "U16") (pin "11") (pinfunction "GND_11") (pintype "power_in"))
      (node (ref "U17") (pin "11") (pinfunction "GND_11") (pintype "power_in"))
      (node (ref "U18") (pin "11") (pinfunction "GND_11") (pintype "power_in"))
      (node (ref "U19") (pin "11") (pinfunction "GND_11") (pintype "power_in"))
      (node (ref "U2") (pin "34") (pinfunction "GND_34") (pintype "power_in"))
      (node (ref "U2") (pin "39") (pinfunction "*LB_39") (pintype "passive"))
      (node (ref "U2") (pin "40") (pinfunction "*UB_40") (pintype "passive"))
      (node (ref "U20") (pin "11") (pinfunction "GND_11") (pintype "power_in"))
      (node (ref "U21") (pin "11") (pinfunction "GND_11") (pintype "power_in"))
      (node (ref "U22") (pin "11") (pinfunction "GND_11") (pintype "power_in"))
      (node (ref "U23") (pin "11") (pinfunction "GND_11") (pintype "power_in"))
      (node (ref "U24") (pin "11") (pinfunction "GND_11") (pintype "power_in"))
      (node (ref "U25") (pin "11") (pinfunction "GND_11") (pintype "power_in"))
      (node (ref "U26") (pin "11") (pinfunction "GND_11") (pintype "power_in"))
      (node (ref "U27") (pin "8") (pinfunction "VSS_8") (pintype "power_in"))
      (node (ref "U28") (pin "1") (pinfunction "GND_1") (pintype "power_in"))
      (node (ref "U29") (pin "4") (pinfunction "GND_4") (pintype "passive"))
      (node (ref "U3") (pin "34") (pinfunction "GND_34") (pintype "power_in"))
      (node (ref "U3") (pin "39") (pinfunction "*LB_39") (pintype "passive"))
      (node (ref "U3") (pin "40") (pinfunction "*UB_40") (pintype "passive"))
      (node (ref "U4") (pin "1") (pinfunction "GND_1") (pintype "passive"))
      (node (ref "U5") (pin "1") (pinfunction "GND_1") (pintype "passive"))
      (node (ref "U6") (pin "1") (pinfunction "GND_1") (pintype "passive"))
      (node (ref "U7") (pin "34") (pinfunction "GND_34") (pintype "power_in"))
      (node (ref "U7") (pin "39") (pinfunction "*LB_39") (pintype "passive"))
      (node (ref "U7") (pin "40") (pinfunction "*UB_40") (pintype "passive"))
      (node (ref "U8") (pin "34") (pinfunction "GND_34") (pintype "power_in"))
      (node (ref "U8") (pin "39") (pinfunction "*LB_39") (pintype "passive"))
      (node (ref "U8") (pin "40") (pinfunction "*UB_40") (pintype "passive"))
      (node (ref "U9") (pin "34") (pinfunction "GND_34") (pintype "power_in"))
      (node (ref "U9") (pin "39") (pinfunction "*LB_39") (pintype "passive"))
      (node (ref "U9") (pin "40") (pinfunction "*UB_40") (pintype "passive"))
      (node (ref "X1") (pin "46") (pinfunction "B1_46") (pintype "passive"))
      (node (ref "X1") (pin "58") (pinfunction "B13_58") (pintype "passive"))
      (node (ref "X1") (pin "66") (pinfunction "B21_66") (pintype "passive"))
      (node (ref "X1") (pin "70") (pinfunction "B25_70") (pintype "passive"))
      (node (ref "X1") (pin "78") (pinfunction "B33_78") (pintype "passive"))
      (node (ref "X1") (pin "90") (pinfunction "B45_90") (pintype "passive"))
    )
    (net (code "266") (name "Net-(CMOS1-A)") (class "Default")
      (node (ref "CMOS1") (pin "1") (pinfunction "A_1") (pintype "passive"))
      (node (ref "SW2") (pin "1") (pinfunction "1_1") (pintype "passive"))
    )
    (net (code "267") (name "Net-(JDC1-S)") (class "Default")
      (node (ref "JDC1") (pin "2") (pinfunction "TN_2") (pintype "passive"))
      (node (ref "JDC1") (pin "3") (pinfunction "S_3") (pintype "power_in"))
      (node (ref "SW1") (pin "3") (pinfunction "3_3") (pintype "passive"))
    )
    (net (code "268") (name "Net-(JDC1-T)") (class "Default")
      (node (ref "JDC1") (pin "1") (pinfunction "T_1") (pintype "passive"))
      (node (ref "SW1") (pin "6") (pinfunction "6_6") (pintype "passive"))
    )
    (net (code "269") (name "Net-(OFF1-A)") (class "Default")
      (node (ref "OFF1") (pin "1") (pinfunction "A_1") (pintype "passive"))
      (node (ref "SW2") (pin "3") (pinfunction "3_3") (pintype "passive"))
    )
    (net (code "270") (name "Net-(R22-Pad2)") (class "Default")
      (node (ref "R22") (pin "2") (pinfunction "2_2") (pintype "passive"))
      (node (ref "SW2") (pin "2") (pinfunction "2_2") (pintype "passive"))
    )
    (net (code "271") (name "Net-(TTL1-A)") (class "Default")
      (node (ref "SW2") (pin "4") (pinfunction "4_4") (pintype "passive"))
      (node (ref "TTL1") (pin "1") (pinfunction "A_1") (pintype "passive"))
    )
    (net (code "272") (name "Net-(U3-I{slash}O15)") (class "Default")
      (node (ref "R1") (pin "1") (pinfunction "1_1") (pintype "passive"))
      (node (ref "U3") (pin "38") (pinfunction "I/O15_38") (pintype "bidirectional"))
    )
    (net (code "273") (name "Net-(U10-I{slash}O10)") (class "Default")
      (node (ref "R2") (pin "1") (pinfunction "1_1") (pintype "passive"))
      (node (ref "U10") (pin "31") (pinfunction "I/O10_31") (pintype "bidirectional"))
      (node (ref "U10") (pin "32") (pinfunction "I/O11_32") (pintype "bidirectional"))
      (node (ref "U10") (pin "35") (pinfunction "I/O12_35") (pintype "bidirectional"))
      (node (ref "U10") (pin "36") (pinfunction "I/O13_36") (pintype "bidirectional"))
      (node (ref "U10") (pin "37") (pinfunction "I/O14_37") (pintype "bidirectional"))
      (node (ref "U10") (pin "38") (pinfunction "I/O15_38") (pintype "bidirectional"))
    )
    (net (code "274") (name "unconnected-(C60-Pad1)") (class "Default")
      (node (ref "C60") (pin "1") (pinfunction "1_1") (pintype "passive"))
    )
    (net (code "275") (name "unconnected-(C60-Pad2)") (class "Default")
      (node (ref "C60") (pin "2") (pinfunction "2_2") (pintype "passive"))
    )
    (net (code "276") (name "unconnected-(C60-Pad79)") (class "Default")
      (node (ref "C60") (pin "79") (pinfunction "79_79") (pintype "passive"))
    )
    (net (code "277") (name "unconnected-(C60-Pad80)") (class "Default")
      (node (ref "C60") (pin "80") (pinfunction "80_80") (pintype "passive"))
    )
    (net (code "278") (name "unconnected-(SW1-Pad2)") (class "Default")
      (node (ref "SW1") (pin "2") (pinfunction "2_2") (pintype "passive"))
    )
    (net (code "279") (name "unconnected-(SW1-Pad5)") (class "Default")
      (node (ref "SW1") (pin "5") (pinfunction "5_5") (pintype "passive"))
    )
    (net (code "280") (name "unconnected-(U1-GND-Pad12)") (class "Default")
      (node (ref "U1") (pin "12") (pinfunction "GND_12") (pintype "power_in"))
    )
    (net (code "281") (name "unconnected-(U1-NC-Pad22)") (class "Default")
      (node (ref "U1") (pin "22") (pinfunction "NC_22") (pintype "passive"))
    )
    (net (code "282") (name "unconnected-(U1-NC-Pad23)") (class "Default")
      (node (ref "U1") (pin "23") (pinfunction "NC_23") (pintype "passive"))
    )
    (net (code "283") (name "unconnected-(U1-NC-Pad28)") (class "Default")
      (node (ref "U1") (pin "28") (pinfunction "NC_28") (pintype "passive"))
    )
    (net (code "284") (name "unconnected-(U1-VCC-Pad11)") (class "Default")
      (node (ref "U1") (pin "11") (pinfunction "VCC_11") (pintype "power_in"))
    )
    (net (code "285") (name "unconnected-(U2-GND-Pad12)") (class "Default")
      (node (ref "U2") (pin "12") (pinfunction "GND_12") (pintype "power_in"))
    )
    (net (code "286") (name "unconnected-(U2-NC-Pad22)") (class "Default")
      (node (ref "U2") (pin "22") (pinfunction "NC_22") (pintype "passive"))
    )
    (net (code "287") (name "unconnected-(U2-NC-Pad23)") (class "Default")
      (node (ref "U2") (pin "23") (pinfunction "NC_23") (pintype "passive"))
    )
    (net (code "288") (name "unconnected-(U2-NC-Pad28)") (class "Default")
      (node (ref "U2") (pin "28") (pinfunction "NC_28") (pintype "passive"))
    )
    (net (code "289") (name "unconnected-(U2-VCC-Pad11)") (class "Default")
      (node (ref "U2") (pin "11") (pinfunction "VCC_11") (pintype "power_in"))
    )
    (net (code "290") (name "unconnected-(U3-GND-Pad12)") (class "Default")
      (node (ref "U3") (pin "12") (pinfunction "GND_12") (pintype "power_in"))
    )
    (net (code "291") (name "unconnected-(U3-NC-Pad22)") (class "Default")
      (node (ref "U3") (pin "22") (pinfunction "NC_22") (pintype "passive"))
    )
    (net (code "292") (name "unconnected-(U3-NC-Pad23)") (class "Default")
      (node (ref "U3") (pin "23") (pinfunction "NC_23") (pintype "passive"))
    )
    (net (code "293") (name "unconnected-(U3-NC-Pad28)") (class "Default")
      (node (ref "U3") (pin "28") (pinfunction "NC_28") (pintype "passive"))
    )
    (net (code "294") (name "unconnected-(U3-VCC-Pad11)") (class "Default")
      (node (ref "U3") (pin "11") (pinfunction "VCC_11") (pintype "power_in"))
    )
    (net (code "295") (name "unconnected-(U7-GND-Pad12)") (class "Default")
      (node (ref "U7") (pin "12") (pinfunction "GND_12") (pintype "power_in"))
    )
    (net (code "296") (name "unconnected-(U7-NC-Pad22)") (class "Default")
      (node (ref "U7") (pin "22") (pinfunction "NC_22") (pintype "passive"))
    )
    (net (code "297") (name "unconnected-(U7-NC-Pad23)") (class "Default")
      (node (ref "U7") (pin "23") (pinfunction "NC_23") (pintype "passive"))
    )
    (net (code "298") (name "unconnected-(U7-NC-Pad28)") (class "Default")
      (node (ref "U7") (pin "28") (pinfunction "NC_28") (pintype "passive"))
    )
    (net (code "299") (name "unconnected-(U7-VCC-Pad11)") (class "Default")
      (node (ref "U7") (pin "11") (pinfunction "VCC_11") (pintype "power_in"))
    )
    (net (code "300") (name "unconnected-(U8-GND-Pad12)") (class "Default")
      (node (ref "U8") (pin "12") (pinfunction "GND_12") (pintype "power_in"))
    )
    (net (code "301") (name "unconnected-(U8-NC-Pad22)") (class "Default")
      (node (ref "U8") (pin "22") (pinfunction "NC_22") (pintype "passive"))
    )
    (net (code "302") (name "unconnected-(U8-NC-Pad23)") (class "Default")
      (node (ref "U8") (pin "23") (pinfunction "NC_23") (pintype "passive"))
    )
    (net (code "303") (name "unconnected-(U8-NC-Pad28)") (class "Default")
      (node (ref "U8") (pin "28") (pinfunction "NC_28") (pintype "passive"))
    )
    (net (code "304") (name "unconnected-(U8-VCC-Pad11)") (class "Default")
      (node (ref "U8") (pin "11") (pinfunction "VCC_11") (pintype "power_in"))
    )
    (net (code "305") (name "unconnected-(U9-GND-Pad12)") (class "Default")
      (node (ref "U9") (pin "12") (pinfunction "GND_12") (pintype "power_in"))
    )
    (net (code "306") (name "unconnected-(U9-NC-Pad22)") (class "Default")
      (node (ref "U9") (pin "22") (pinfunction "NC_22") (pintype "passive"))
    )
    (net (code "307") (name "unconnected-(U9-NC-Pad23)") (class "Default")
      (node (ref "U9") (pin "23") (pinfunction "NC_23") (pintype "passive"))
    )
    (net (code "308") (name "unconnected-(U9-NC-Pad28)") (class "Default")
      (node (ref "U9") (pin "28") (pinfunction "NC_28") (pintype "passive"))
    )
    (net (code "309") (name "unconnected-(U9-VCC-Pad11)") (class "Default")
      (node (ref "U9") (pin "11") (pinfunction "VCC_11") (pintype "power_in"))
    )
    (net (code "310") (name "unconnected-(U10-GND-Pad12)") (class "Default")
      (node (ref "U10") (pin "12") (pinfunction "GND_12") (pintype "power_in"))
    )
    (net (code "311") (name "unconnected-(U10-NC-Pad22)") (class "Default")
      (node (ref "U10") (pin "22") (pinfunction "NC_22") (pintype "passive"))
    )
    (net (code "312") (name "unconnected-(U10-NC-Pad23)") (class "Default")
      (node (ref "U10") (pin "23") (pinfunction "NC_23") (pintype "passive"))
    )
    (net (code "313") (name "unconnected-(U10-NC-Pad28)") (class "Default")
      (node (ref "U10") (pin "28") (pinfunction "NC_28") (pintype "passive"))
    )
    (net (code "314") (name "unconnected-(U10-VCC-Pad11)") (class "Default")
      (node (ref "U10") (pin "11") (pinfunction "VCC_11") (pintype "power_in"))
    )
    (net (code "315") (name "unconnected-(U22-A8-Pad9)") (class "Default")
      (node (ref "U22") (pin "9") (pinfunction "A8_9") (pintype "bidirectional"))
    )
    (net (code "316") (name "unconnected-(U22-B8-Pad12)") (class "Default")
      (node (ref "U22") (pin "12") (pinfunction "B8_12") (pintype "bidirectional"))
    )
    (net (code "317") (name "unconnected-(U26-A5-Pad6)") (class "Default")
      (node (ref "U26") (pin "6") (pinfunction "A5_6") (pintype "bidirectional"))
    )
    (net (code "318") (name "unconnected-(U26-A6-Pad7)") (class "Default")
      (node (ref "U26") (pin "7") (pinfunction "A6_7") (pintype "bidirectional"))
    )
    (net (code "319") (name "unconnected-(U26-A7-Pad8)") (class "Default")
      (node (ref "U26") (pin "8") (pinfunction "A7_8") (pintype "bidirectional"))
    )
    (net (code "320") (name "unconnected-(U26-A8-Pad9)") (class "Default")
      (node (ref "U26") (pin "9") (pinfunction "A8_9") (pintype "bidirectional"))
    )
    (net (code "321") (name "unconnected-(U26-B5-Pad15)") (class "Default")
      (node (ref "U26") (pin "15") (pinfunction "B5_15") (pintype "bidirectional"))
    )
    (net (code "322") (name "unconnected-(U26-B6-Pad14)") (class "Default")
      (node (ref "U26") (pin "14") (pinfunction "B6_14") (pintype "bidirectional"))
    )
    (net (code "323") (name "unconnected-(U26-B7-Pad13)") (class "Default")
      (node (ref "U26") (pin "13") (pinfunction "B7_13") (pintype "bidirectional"))
    )
    (net (code "324") (name "unconnected-(U26-B8-Pad12)") (class "Default")
      (node (ref "U26") (pin "12") (pinfunction "B8_12") (pintype "bidirectional"))
    )
    (net (code "325") (name "unconnected-(U28-NC.-Pad7)") (class "Default")
      (node (ref "U28") (pin "7") (pinfunction "NC._7") (pintype "passive+no_connect"))
    )
    (net (code "326") (name "unconnected-(U28-R232-Pad15)") (class "Default")
      (node (ref "U28") (pin "15") (pinfunction "R232_15") (pintype "input+no_connect"))
    )
    (net (code "327") (name "unconnected-(U28-~{CTS}-Pad9)") (class "Default")
      (node (ref "U28") (pin "9") (pinfunction "~{CTS}_9") (pintype "input+no_connect"))
    )
    (net (code "328") (name "unconnected-(U28-~{DCD}-Pad12)") (class "Default")
      (node (ref "U28") (pin "12") (pinfunction "~{DCD}_12") (pintype "input+no_connect"))
    )
    (net (code "329") (name "unconnected-(U28-~{DSR}-Pad10)") (class "Default")
      (node (ref "U28") (pin "10") (pinfunction "~{DSR}_10") (pintype "input+no_connect"))
    )
    (net (code "330") (name "unconnected-(U28-~{DTR}-Pad13)") (class "Default")
      (node (ref "U28") (pin "13") (pinfunction "~{DTR}_13") (pintype "output+no_connect"))
    )
    (net (code "331") (name "unconnected-(U28-~{OUT}-Pad8)") (class "Default")
      (node (ref "U28") (pin "8") (pinfunction "~{OUT}_8") (pintype "output+no_connect"))
    )
    (net (code "332") (name "unconnected-(U28-~{RI}-Pad11)") (class "Default")
      (node (ref "U28") (pin "11") (pinfunction "~{RI}_11") (pintype "input+no_connect"))
    )
    (net (code "333") (name "unconnected-(U28-~{RTS}-Pad14)") (class "Default")
      (node (ref "U28") (pin "14") (pinfunction "~{RTS}_14") (pintype "output+no_connect"))
    )
    (net (code "334") (name "unconnected-(U29-GND-Pad5)") (class "Default")
      (node (ref "U29") (pin "5") (pinfunction "GND_5") (pintype "passive+no_connect"))
    )
    (net (code "335") (name "unconnected-(U29-GND-Pad6)") (class "Default")
      (node (ref "U29") (pin "6") (pinfunction "GND_6") (pintype "passive+no_connect"))
    )
    (net (code "336") (name "unconnected-(U29-VBus-Pad1)") (class "Default")
      (node (ref "U29") (pin "1") (pinfunction "VBus_1") (pintype "passive+no_connect"))
    )
    (net (code "337") (name "unconnected-(X1A-A44-Pad44)") (class "Default")
      (node (ref "X1") (pin "44") (pinfunction "A44_44") (pintype "passive+no_connect"))
    )
    (net (code "338") (name "unconnected-(X1A-A45-Pad45)") (class "Default")
      (node (ref "X1") (pin "45") (pinfunction "A45_45") (pintype "passive+no_connect"))
    )
    (net (code "339") (name "unconnected-(X1B-B24-Pad69)") (class "Default")
      (node (ref "X1") (pin "69") (pinfunction "B24_69") (pintype "passive+no_connect"))
    )
    (net (code "340") (name "unconnected-(X1B-B29-Pad74)") (class "Default")
      (node (ref "X1") (pin "74") (pinfunction "B29_74") (pintype "passive+no_connect"))
    )
    (net (code "341") (name "unconnected-(X1B-B30-Pad75)") (class "Default")
      (node (ref "X1") (pin "75") (pinfunction "B30_75") (pintype "passive+no_connect"))
    )
    (net (code "342") (name "unconnected-(X1B-B35-Pad80)") (class "Default")
      (node (ref "X1") (pin "80") (pinfunction "B35_80") (pintype "passive+no_connect"))
    )
    (net (code "343") (name "unconnected-(X1B-B40-Pad85)") (class "Default")
      (node (ref "X1") (pin "85") (pinfunction "B40_85") (pintype "passive+no_connect"))
    )
    (net (code "344") (name "unconnected-(X1B-B41-Pad86)") (class "Default")
      (node (ref "X1") (pin "86") (pinfunction "B41_86") (pintype "passive+no_connect"))
    )
    (net (code "345") (name "unconnected-(X1C-C15-Pad105)") (class "Default")
      (node (ref "X1") (pin "105") (pinfunction "C15_105") (pintype "passive+no_connect"))
    )
    (net (code "346") (name "unconnected-(X1C-C20-Pad110)") (class "Default")
      (node (ref "X1") (pin "110") (pinfunction "C20_110") (pintype "passive+no_connect"))
    )
    (net (code "347") (name "unconnected-(X1C-C23-Pad113)") (class "Default")
      (node (ref "X1") (pin "113") (pinfunction "C23_113") (pintype "passive+no_connect"))
    )
    (net (code "348") (name "unconnected-(X1C-C24-Pad114)") (class "Default")
      (node (ref "X1") (pin "114") (pinfunction "C24_114") (pintype "passive+no_connect"))
    )
    (net (code "349") (name "unconnected-(X1C-C25-Pad115)") (class "Default")
      (node (ref "X1") (pin "115") (pinfunction "C25_115") (pintype "passive+no_connect"))
    )
    (net (code "350") (name "unconnected-(X1C-C26-Pad116)") (class "Default")
      (node (ref "X1") (pin "116") (pinfunction "C26_116") (pintype "passive+no_connect"))
    )
    (net (code "351") (name "unconnected-(X1C-C41-Pad131)") (class "Default")
      (node (ref "X1") (pin "131") (pinfunction "C41_131") (pintype "passive+no_connect"))
    )
    (net (code "352") (name "unconnected-(X1C-C42-Pad132)") (class "Default")
      (node (ref "X1") (pin "132") (pinfunction "C42_132") (pintype "passive+no_connect"))
    )
    (net (code "353") (name "unconnected-(X1C-C43-Pad133)") (class "Default")
      (node (ref "X1") (pin "133") (pinfunction "C43_133") (pintype "passive+no_connect"))
    )
    (net (code "354") (name "unconnected-(X1C-C44-Pad134)") (class "Default")
      (node (ref "X1") (pin "134") (pinfunction "C44_134") (pintype "passive+no_connect"))
    )
  )
)
